# GS_01_Pow.net
KiCad netlist of a schematic drawn in Altium Designer
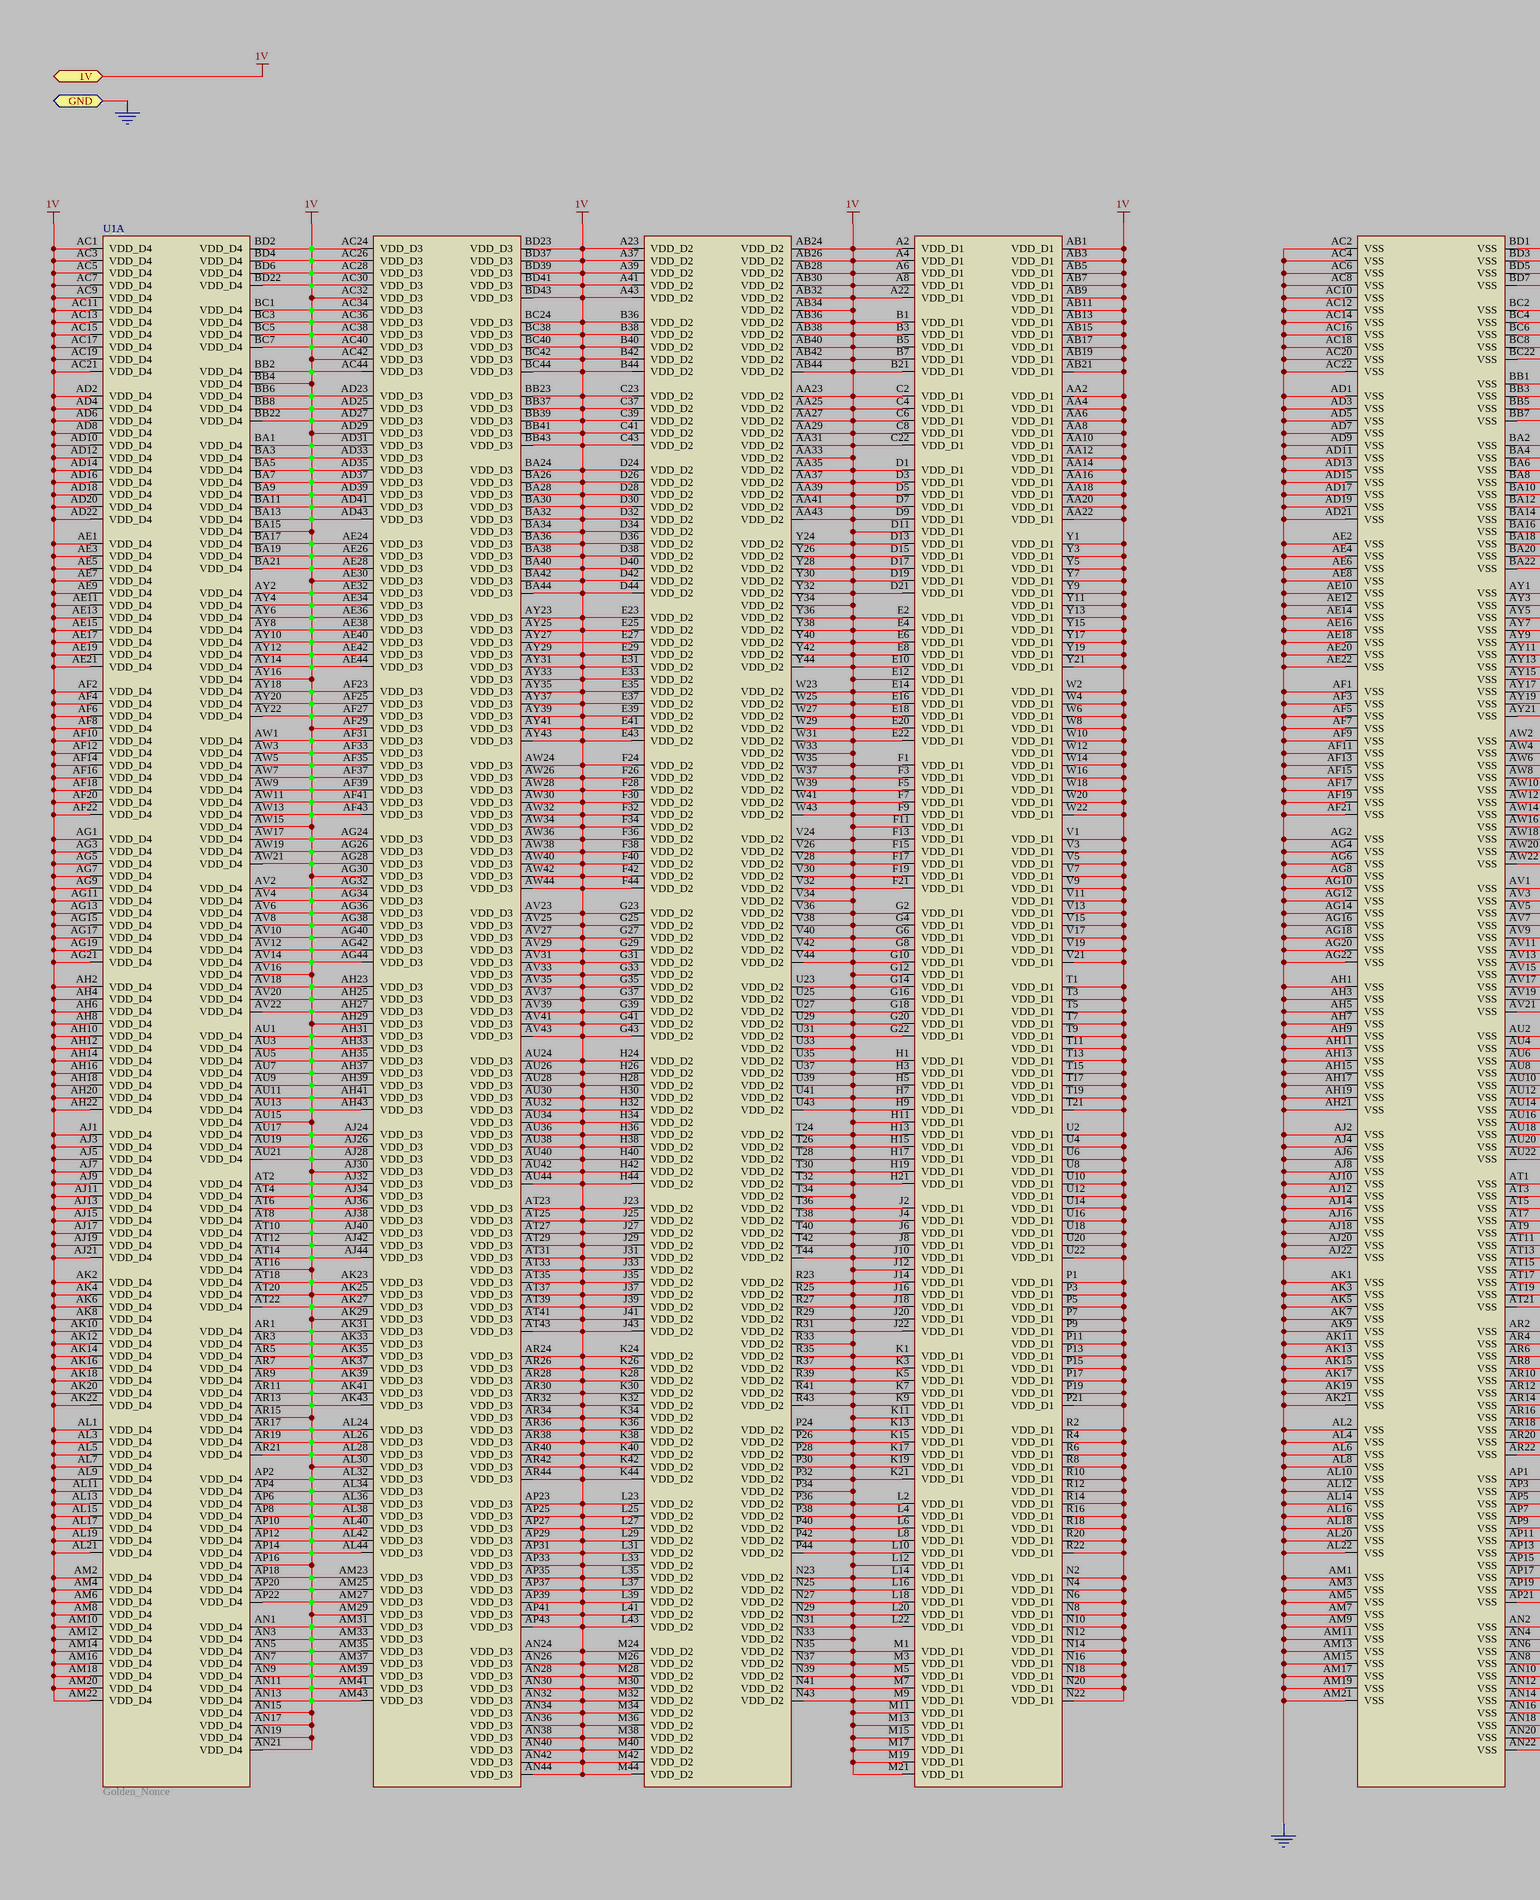
[diagram p0: GS_01_Pow.SchDoc, left]
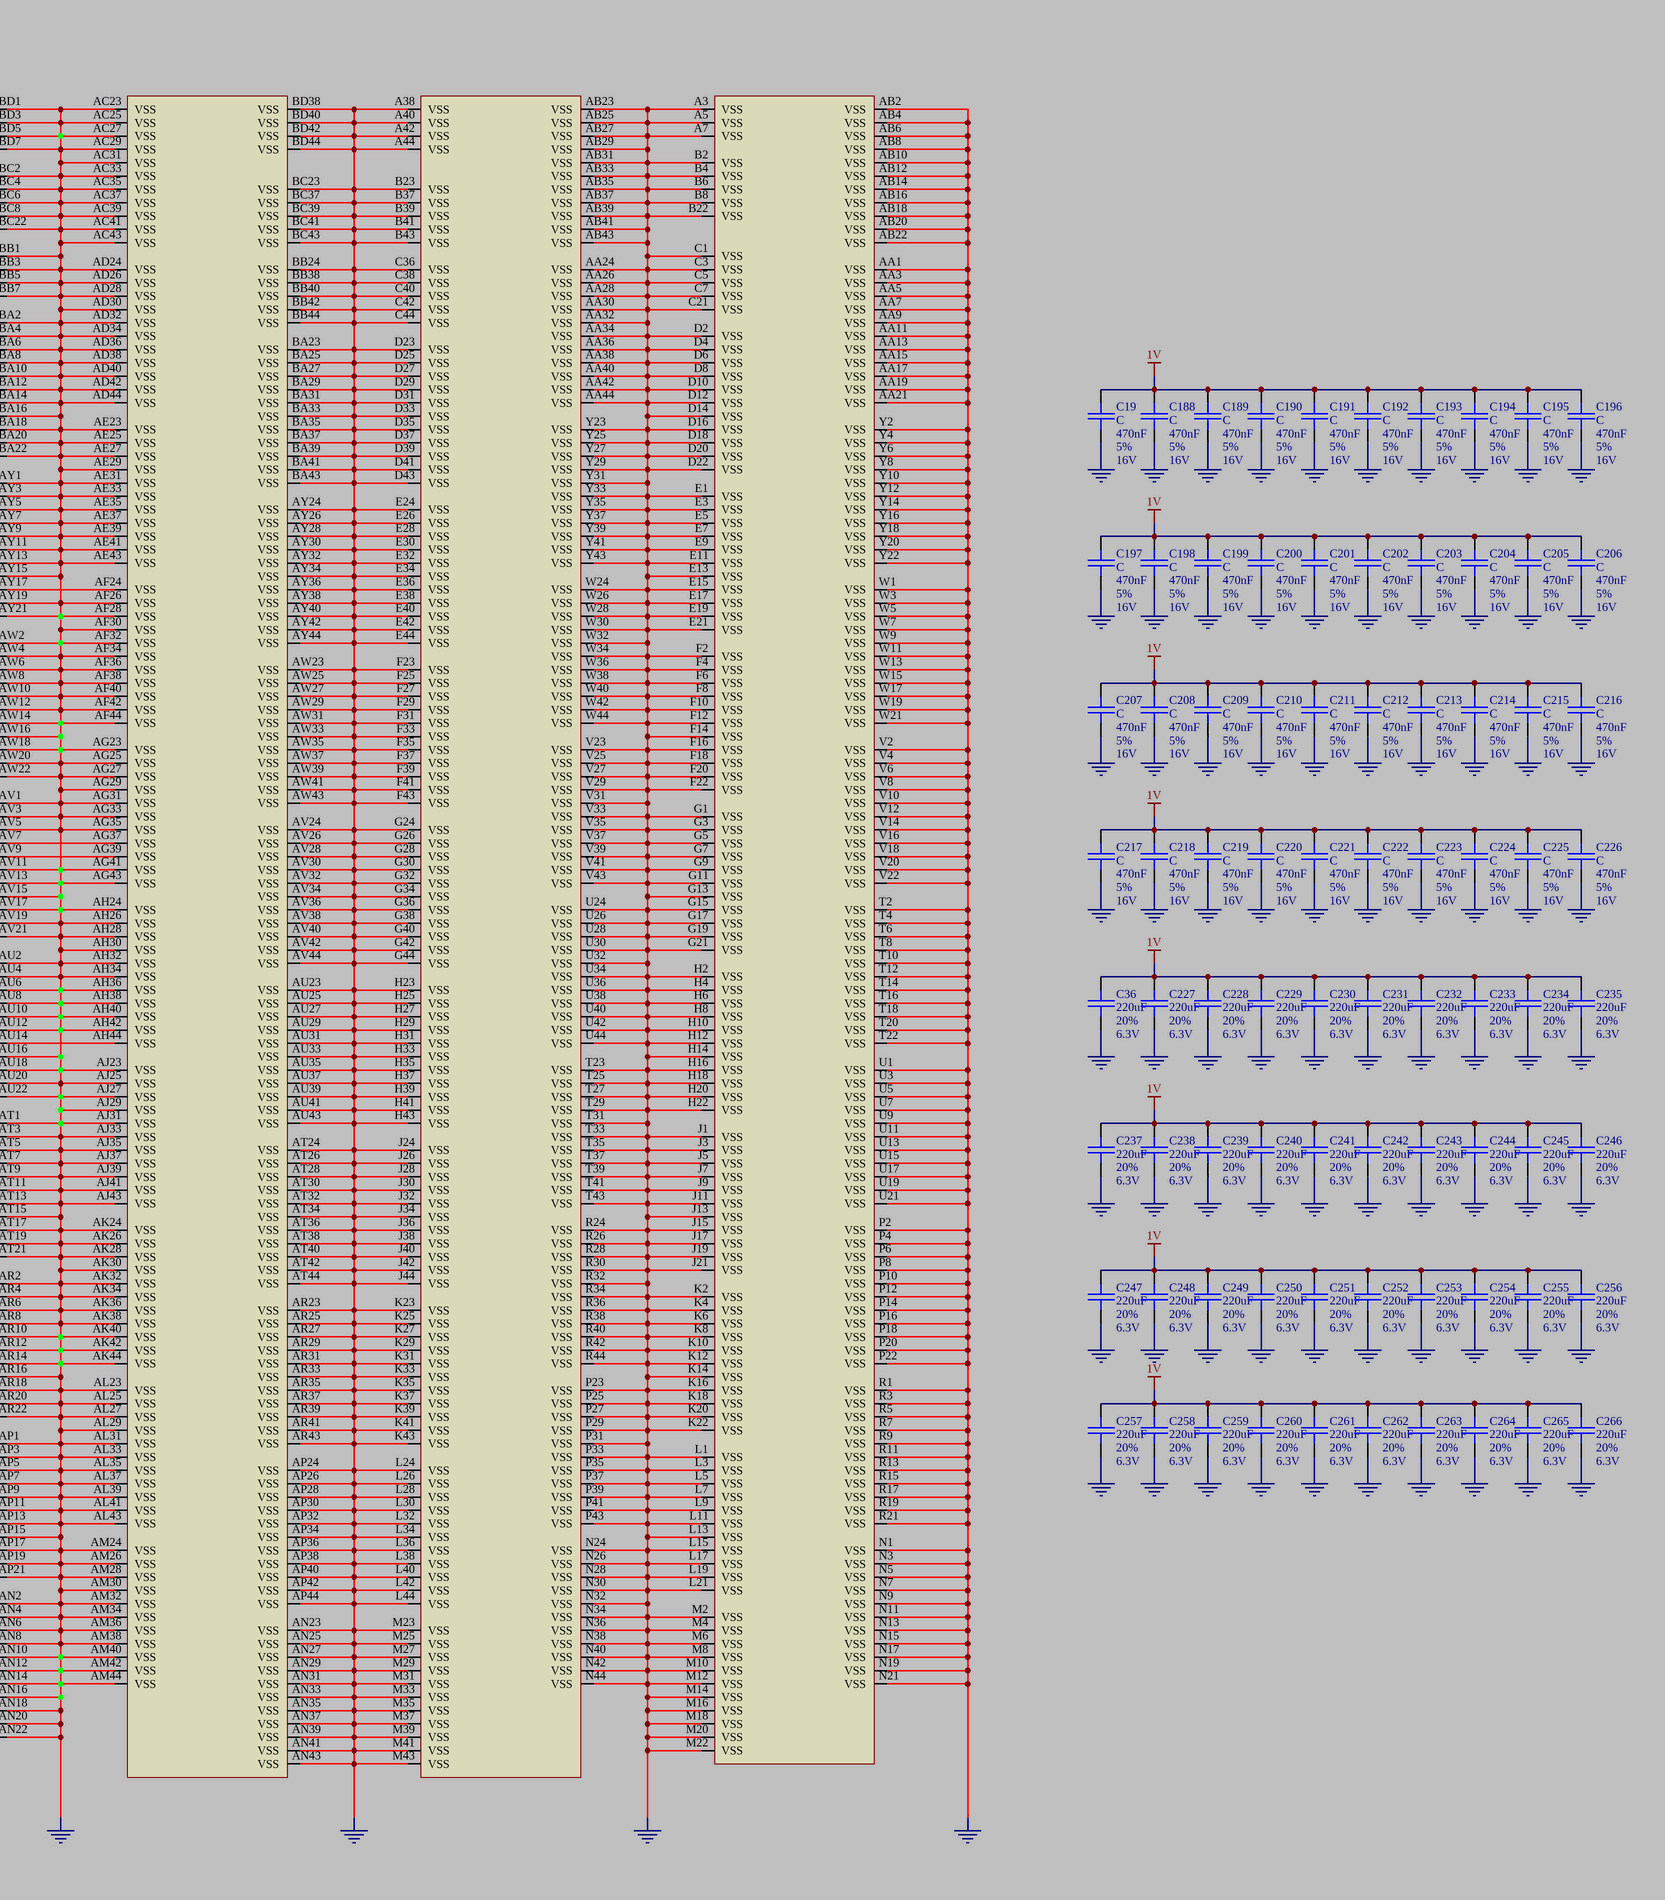
[diagram p1: GS_01_Pow.SchDoc, right]

(export (version "E")
  (design (tool "Eeschema 10.0.6"))
  (components
    (comp (ref "C19")
      (value "C")
      (footprint "SMD_0603_CAPC1608X95N")
      (fields
        (field (name "DB_PART_NUMBER") "CAP000028169")
        (field (name "DB_VALUE") "470nF")
        (field (name "DB_TOLERANCE") "5%")
        (field (name "DB_VOLTAGE") "16V")
        (field (name "DB_MANUFACTURER_PART") "KEMET    C0603C474J4RAC")
      )
      (libsource (lib "Database_Libs1") (part "C"))
    )
    (comp (ref "C36")
      (value "C")
      (footprint "SMD_1210_CAPC3225X279N")
      (fields
        (field (name "DB_PART_NUMBER") "CAP000047355")
        (field (name "DB_VALUE") "220uF")
        (field (name "DB_TOLERANCE") "20%")
        (field (name "DB_VOLTAGE") "6.3V")
        (field (name "DB_MANUFACTURER_PART") "SAMSUNG    CL32A227MQVNNNE")
        (field (name "DB_APPROVED_BY") "VSN")
      )
      (libsource (lib "Database_Libs1") (part "C"))
    )
    (comp (ref "C188")
      (value "C")
      (footprint "SMD_0603_CAPC1608X95N")
      (fields
        (field (name "DB_PART_NUMBER") "CAP000028169")
        (field (name "DB_VALUE") "470nF")
        (field (name "DB_TOLERANCE") "5%")
        (field (name "DB_VOLTAGE") "16V")
        (field (name "DB_MANUFACTURER_PART") "KEMET    C0603C474J4RAC")
      )
      (libsource (lib "Database_Libs1") (part "C"))
    )
    (comp (ref "C189")
      (value "C")
      (footprint "SMD_0603_CAPC1608X95N")
      (fields
        (field (name "DB_PART_NUMBER") "CAP000028169")
        (field (name "DB_VALUE") "470nF")
        (field (name "DB_TOLERANCE") "5%")
        (field (name "DB_VOLTAGE") "16V")
        (field (name "DB_MANUFACTURER_PART") "KEMET    C0603C474J4RAC")
      )
      (libsource (lib "Database_Libs1") (part "C"))
    )
    (comp (ref "C190")
      (value "C")
      (footprint "SMD_0603_CAPC1608X95N")
      (fields
        (field (name "DB_PART_NUMBER") "CAP000028169")
        (field (name "DB_VALUE") "470nF")
        (field (name "DB_TOLERANCE") "5%")
        (field (name "DB_VOLTAGE") "16V")
        (field (name "DB_MANUFACTURER_PART") "KEMET    C0603C474J4RAC")
      )
      (libsource (lib "Database_Libs1") (part "C"))
    )
    (comp (ref "C191")
      (value "C")
      (footprint "SMD_0603_CAPC1608X95N")
      (fields
        (field (name "DB_PART_NUMBER") "CAP000028169")
        (field (name "DB_VALUE") "470nF")
        (field (name "DB_TOLERANCE") "5%")
        (field (name "DB_VOLTAGE") "16V")
        (field (name "DB_MANUFACTURER_PART") "KEMET    C0603C474J4RAC")
      )
      (libsource (lib "Database_Libs1") (part "C"))
    )
    (comp (ref "C192")
      (value "C")
      (footprint "SMD_0603_CAPC1608X95N")
      (fields
        (field (name "DB_PART_NUMBER") "CAP000028169")
        (field (name "DB_VALUE") "470nF")
        (field (name "DB_TOLERANCE") "5%")
        (field (name "DB_VOLTAGE") "16V")
        (field (name "DB_MANUFACTURER_PART") "KEMET    C0603C474J4RAC")
      )
      (libsource (lib "Database_Libs1") (part "C"))
    )
    (comp (ref "C193")
      (value "C")
      (footprint "SMD_0603_CAPC1608X95N")
      (fields
        (field (name "DB_PART_NUMBER") "CAP000028169")
        (field (name "DB_VALUE") "470nF")
        (field (name "DB_TOLERANCE") "5%")
        (field (name "DB_VOLTAGE") "16V")
        (field (name "DB_MANUFACTURER_PART") "KEMET    C0603C474J4RAC")
      )
      (libsource (lib "Database_Libs1") (part "C"))
    )
    (comp (ref "C194")
      (value "C")
      (footprint "SMD_0603_CAPC1608X95N")
      (fields
        (field (name "DB_PART_NUMBER") "CAP000028169")
        (field (name "DB_VALUE") "470nF")
        (field (name "DB_TOLERANCE") "5%")
        (field (name "DB_VOLTAGE") "16V")
        (field (name "DB_MANUFACTURER_PART") "KEMET    C0603C474J4RAC")
      )
      (libsource (lib "Database_Libs1") (part "C"))
    )
    (comp (ref "C195")
      (value "C")
      (footprint "SMD_0603_CAPC1608X95N")
      (fields
        (field (name "DB_PART_NUMBER") "CAP000028169")
        (field (name "DB_VALUE") "470nF")
        (field (name "DB_TOLERANCE") "5%")
        (field (name "DB_VOLTAGE") "16V")
        (field (name "DB_MANUFACTURER_PART") "KEMET    C0603C474J4RAC")
      )
      (libsource (lib "Database_Libs1") (part "C"))
    )
    (comp (ref "C196")
      (value "C")
      (footprint "SMD_0603_CAPC1608X95N")
      (fields
        (field (name "DB_PART_NUMBER") "CAP000028169")
        (field (name "DB_VALUE") "470nF")
        (field (name "DB_TOLERANCE") "5%")
        (field (name "DB_VOLTAGE") "16V")
        (field (name "DB_MANUFACTURER_PART") "KEMET    C0603C474J4RAC")
      )
      (libsource (lib "Database_Libs1") (part "C"))
    )
    (comp (ref "C197")
      (value "C")
      (footprint "SMD_0603_CAPC1608X95N")
      (fields
        (field (name "DB_PART_NUMBER") "CAP000028169")
        (field (name "DB_VALUE") "470nF")
        (field (name "DB_TOLERANCE") "5%")
        (field (name "DB_VOLTAGE") "16V")
        (field (name "DB_MANUFACTURER_PART") "KEMET    C0603C474J4RAC")
      )
      (libsource (lib "Database_Libs1") (part "C"))
    )
    (comp (ref "C198")
      (value "C")
      (footprint "SMD_0603_CAPC1608X95N")
      (fields
        (field (name "DB_PART_NUMBER") "CAP000028169")
        (field (name "DB_VALUE") "470nF")
        (field (name "DB_TOLERANCE") "5%")
        (field (name "DB_VOLTAGE") "16V")
        (field (name "DB_MANUFACTURER_PART") "KEMET    C0603C474J4RAC")
      )
      (libsource (lib "Database_Libs1") (part "C"))
    )
    (comp (ref "C199")
      (value "C")
      (footprint "SMD_0603_CAPC1608X95N")
      (fields
        (field (name "DB_PART_NUMBER") "CAP000028169")
        (field (name "DB_VALUE") "470nF")
        (field (name "DB_TOLERANCE") "5%")
        (field (name "DB_VOLTAGE") "16V")
        (field (name "DB_MANUFACTURER_PART") "KEMET    C0603C474J4RAC")
      )
      (libsource (lib "Database_Libs1") (part "C"))
    )
    (comp (ref "C200")
      (value "C")
      (footprint "SMD_0603_CAPC1608X95N")
      (fields
        (field (name "DB_PART_NUMBER") "CAP000028169")
        (field (name "DB_VALUE") "470nF")
        (field (name "DB_TOLERANCE") "5%")
        (field (name "DB_VOLTAGE") "16V")
        (field (name "DB_MANUFACTURER_PART") "KEMET    C0603C474J4RAC")
      )
      (libsource (lib "Database_Libs1") (part "C"))
    )
    (comp (ref "C201")
      (value "C")
      (footprint "SMD_0603_CAPC1608X95N")
      (fields
        (field (name "DB_PART_NUMBER") "CAP000028169")
        (field (name "DB_VALUE") "470nF")
        (field (name "DB_TOLERANCE") "5%")
        (field (name "DB_VOLTAGE") "16V")
        (field (name "DB_MANUFACTURER_PART") "KEMET    C0603C474J4RAC")
      )
      (libsource (lib "Database_Libs1") (part "C"))
    )
    (comp (ref "C202")
      (value "C")
      (footprint "SMD_0603_CAPC1608X95N")
      (fields
        (field (name "DB_PART_NUMBER") "CAP000028169")
        (field (name "DB_VALUE") "470nF")
        (field (name "DB_TOLERANCE") "5%")
        (field (name "DB_VOLTAGE") "16V")
        (field (name "DB_MANUFACTURER_PART") "KEMET    C0603C474J4RAC")
      )
      (libsource (lib "Database_Libs1") (part "C"))
    )
    (comp (ref "C203")
      (value "C")
      (footprint "SMD_0603_CAPC1608X95N")
      (fields
        (field (name "DB_PART_NUMBER") "CAP000028169")
        (field (name "DB_VALUE") "470nF")
        (field (name "DB_TOLERANCE") "5%")
        (field (name "DB_VOLTAGE") "16V")
        (field (name "DB_MANUFACTURER_PART") "KEMET    C0603C474J4RAC")
      )
      (libsource (lib "Database_Libs1") (part "C"))
    )
    (comp (ref "C204")
      (value "C")
      (footprint "SMD_0603_CAPC1608X95N")
      (fields
        (field (name "DB_PART_NUMBER") "CAP000028169")
        (field (name "DB_VALUE") "470nF")
        (field (name "DB_TOLERANCE") "5%")
        (field (name "DB_VOLTAGE") "16V")
        (field (name "DB_MANUFACTURER_PART") "KEMET    C0603C474J4RAC")
      )
      (libsource (lib "Database_Libs1") (part "C"))
    )
    (comp (ref "C205")
      (value "C")
      (footprint "SMD_0603_CAPC1608X95N")
      (fields
        (field (name "DB_PART_NUMBER") "CAP000028169")
        (field (name "DB_VALUE") "470nF")
        (field (name "DB_TOLERANCE") "5%")
        (field (name "DB_VOLTAGE") "16V")
        (field (name "DB_MANUFACTURER_PART") "KEMET    C0603C474J4RAC")
      )
      (libsource (lib "Database_Libs1") (part "C"))
    )
    (comp (ref "C206")
      (value "C")
      (footprint "SMD_0603_CAPC1608X95N")
      (fields
        (field (name "DB_PART_NUMBER") "CAP000028169")
        (field (name "DB_VALUE") "470nF")
        (field (name "DB_TOLERANCE") "5%")
        (field (name "DB_VOLTAGE") "16V")
        (field (name "DB_MANUFACTURER_PART") "KEMET    C0603C474J4RAC")
      )
      (libsource (lib "Database_Libs1") (part "C"))
    )
    (comp (ref "C207")
      (value "C")
      (footprint "SMD_0603_CAPC1608X95N")
      (fields
        (field (name "DB_PART_NUMBER") "CAP000028169")
        (field (name "DB_VALUE") "470nF")
        (field (name "DB_TOLERANCE") "5%")
        (field (name "DB_VOLTAGE") "16V")
        (field (name "DB_MANUFACTURER_PART") "KEMET    C0603C474J4RAC")
      )
      (libsource (lib "Database_Libs1") (part "C"))
    )
    (comp (ref "C208")
      (value "C")
      (footprint "SMD_0603_CAPC1608X95N")
      (fields
        (field (name "DB_PART_NUMBER") "CAP000028169")
        (field (name "DB_VALUE") "470nF")
        (field (name "DB_TOLERANCE") "5%")
        (field (name "DB_VOLTAGE") "16V")
        (field (name "DB_MANUFACTURER_PART") "KEMET    C0603C474J4RAC")
      )
      (libsource (lib "Database_Libs1") (part "C"))
    )
    (comp (ref "C209")
      (value "C")
      (footprint "SMD_0603_CAPC1608X95N")
      (fields
        (field (name "DB_PART_NUMBER") "CAP000028169")
        (field (name "DB_VALUE") "470nF")
        (field (name "DB_TOLERANCE") "5%")
        (field (name "DB_VOLTAGE") "16V")
        (field (name "DB_MANUFACTURER_PART") "KEMET    C0603C474J4RAC")
      )
      (libsource (lib "Database_Libs1") (part "C"))
    )
    (comp (ref "C210")
      (value "C")
      (footprint "SMD_0603_CAPC1608X95N")
      (fields
        (field (name "DB_PART_NUMBER") "CAP000028169")
        (field (name "DB_VALUE") "470nF")
        (field (name "DB_TOLERANCE") "5%")
        (field (name "DB_VOLTAGE") "16V")
        (field (name "DB_MANUFACTURER_PART") "KEMET    C0603C474J4RAC")
      )
      (libsource (lib "Database_Libs1") (part "C"))
    )
    (comp (ref "C211")
      (value "C")
      (footprint "SMD_0603_CAPC1608X95N")
      (fields
        (field (name "DB_PART_NUMBER") "CAP000028169")
        (field (name "DB_VALUE") "470nF")
        (field (name "DB_TOLERANCE") "5%")
        (field (name "DB_VOLTAGE") "16V")
        (field (name "DB_MANUFACTURER_PART") "KEMET    C0603C474J4RAC")
      )
      (libsource (lib "Database_Libs1") (part "C"))
    )
    (comp (ref "C212")
      (value "C")
      (footprint "SMD_0603_CAPC1608X95N")
      (fields
        (field (name "DB_PART_NUMBER") "CAP000028169")
        (field (name "DB_VALUE") "470nF")
        (field (name "DB_TOLERANCE") "5%")
        (field (name "DB_VOLTAGE") "16V")
        (field (name "DB_MANUFACTURER_PART") "KEMET    C0603C474J4RAC")
      )
      (libsource (lib "Database_Libs1") (part "C"))
    )
    (comp (ref "C213")
      (value "C")
      (footprint "SMD_0603_CAPC1608X95N")
      (fields
        (field (name "DB_PART_NUMBER") "CAP000028169")
        (field (name "DB_VALUE") "470nF")
        (field (name "DB_TOLERANCE") "5%")
        (field (name "DB_VOLTAGE") "16V")
        (field (name "DB_MANUFACTURER_PART") "KEMET    C0603C474J4RAC")
      )
      (libsource (lib "Database_Libs1") (part "C"))
    )
    (comp (ref "C214")
      (value "C")
      (footprint "SMD_0603_CAPC1608X95N")
      (fields
        (field (name "DB_PART_NUMBER") "CAP000028169")
        (field (name "DB_VALUE") "470nF")
        (field (name "DB_TOLERANCE") "5%")
        (field (name "DB_VOLTAGE") "16V")
        (field (name "DB_MANUFACTURER_PART") "KEMET    C0603C474J4RAC")
      )
      (libsource (lib "Database_Libs1") (part "C"))
    )
    (comp (ref "C215")
      (value "C")
      (footprint "SMD_0603_CAPC1608X95N")
      (fields
        (field (name "DB_PART_NUMBER") "CAP000028169")
        (field (name "DB_VALUE") "470nF")
        (field (name "DB_TOLERANCE") "5%")
        (field (name "DB_VOLTAGE") "16V")
        (field (name "DB_MANUFACTURER_PART") "KEMET    C0603C474J4RAC")
      )
      (libsource (lib "Database_Libs1") (part "C"))
    )
    (comp (ref "C216")
      (value "C")
      (footprint "SMD_0603_CAPC1608X95N")
      (fields
        (field (name "DB_PART_NUMBER") "CAP000028169")
        (field (name "DB_VALUE") "470nF")
        (field (name "DB_TOLERANCE") "5%")
        (field (name "DB_VOLTAGE") "16V")
        (field (name "DB_MANUFACTURER_PART") "KEMET    C0603C474J4RAC")
      )
      (libsource (lib "Database_Libs1") (part "C"))
    )
    (comp (ref "C217")
      (value "C")
      (footprint "SMD_0603_CAPC1608X95N")
      (fields
        (field (name "DB_PART_NUMBER") "CAP000028169")
        (field (name "DB_VALUE") "470nF")
        (field (name "DB_TOLERANCE") "5%")
        (field (name "DB_VOLTAGE") "16V")
        (field (name "DB_MANUFACTURER_PART") "KEMET    C0603C474J4RAC")
      )
      (libsource (lib "Database_Libs1") (part "C"))
    )
    (comp (ref "C218")
      (value "C")
      (footprint "SMD_0603_CAPC1608X95N")
      (fields
        (field (name "DB_PART_NUMBER") "CAP000028169")
        (field (name "DB_VALUE") "470nF")
        (field (name "DB_TOLERANCE") "5%")
        (field (name "DB_VOLTAGE") "16V")
        (field (name "DB_MANUFACTURER_PART") "KEMET    C0603C474J4RAC")
      )
      (libsource (lib "Database_Libs1") (part "C"))
    )
    (comp (ref "C219")
      (value "C")
      (footprint "SMD_0603_CAPC1608X95N")
      (fields
        (field (name "DB_PART_NUMBER") "CAP000028169")
        (field (name "DB_VALUE") "470nF")
        (field (name "DB_TOLERANCE") "5%")
        (field (name "DB_VOLTAGE") "16V")
        (field (name "DB_MANUFACTURER_PART") "KEMET    C0603C474J4RAC")
      )
      (libsource (lib "Database_Libs1") (part "C"))
    )
    (comp (ref "C220")
      (value "C")
      (footprint "SMD_0603_CAPC1608X95N")
      (fields
        (field (name "DB_PART_NUMBER") "CAP000028169")
        (field (name "DB_VALUE") "470nF")
        (field (name "DB_TOLERANCE") "5%")
        (field (name "DB_VOLTAGE") "16V")
        (field (name "DB_MANUFACTURER_PART") "KEMET    C0603C474J4RAC")
      )
      (libsource (lib "Database_Libs1") (part "C"))
    )
    (comp (ref "C221")
      (value "C")
      (footprint "SMD_0603_CAPC1608X95N")
      (fields
        (field (name "DB_PART_NUMBER") "CAP000028169")
        (field (name "DB_VALUE") "470nF")
        (field (name "DB_TOLERANCE") "5%")
        (field (name "DB_VOLTAGE") "16V")
        (field (name "DB_MANUFACTURER_PART") "KEMET    C0603C474J4RAC")
      )
      (libsource (lib "Database_Libs1") (part "C"))
    )
    (comp (ref "C222")
      (value "C")
      (footprint "SMD_0603_CAPC1608X95N")
      (fields
        (field (name "DB_PART_NUMBER") "CAP000028169")
        (field (name "DB_VALUE") "470nF")
        (field (name "DB_TOLERANCE") "5%")
        (field (name "DB_VOLTAGE") "16V")
        (field (name "DB_MANUFACTURER_PART") "KEMET    C0603C474J4RAC")
      )
      (libsource (lib "Database_Libs1") (part "C"))
    )
    (comp (ref "C223")
      (value "C")
      (footprint "SMD_0603_CAPC1608X95N")
      (fields
        (field (name "DB_PART_NUMBER") "CAP000028169")
        (field (name "DB_VALUE") "470nF")
        (field (name "DB_TOLERANCE") "5%")
        (field (name "DB_VOLTAGE") "16V")
        (field (name "DB_MANUFACTURER_PART") "KEMET    C0603C474J4RAC")
      )
      (libsource (lib "Database_Libs1") (part "C"))
    )
    (comp (ref "C224")
      (value "C")
      (footprint "SMD_0603_CAPC1608X95N")
      (fields
        (field (name "DB_PART_NUMBER") "CAP000028169")
        (field (name "DB_VALUE") "470nF")
        (field (name "DB_TOLERANCE") "5%")
        (field (name "DB_VOLTAGE") "16V")
        (field (name "DB_MANUFACTURER_PART") "KEMET    C0603C474J4RAC")
      )
      (libsource (lib "Database_Libs1") (part "C"))
    )
    (comp (ref "C225")
      (value "C")
      (footprint "SMD_0603_CAPC1608X95N")
      (fields
        (field (name "DB_PART_NUMBER") "CAP000028169")
        (field (name "DB_VALUE") "470nF")
        (field (name "DB_TOLERANCE") "5%")
        (field (name "DB_VOLTAGE") "16V")
        (field (name "DB_MANUFACTURER_PART") "KEMET    C0603C474J4RAC")
      )
      (libsource (lib "Database_Libs1") (part "C"))
    )
    (comp (ref "C226")
      (value "C")
      (footprint "SMD_0603_CAPC1608X95N")
      (fields
        (field (name "DB_PART_NUMBER") "CAP000028169")
        (field (name "DB_VALUE") "470nF")
        (field (name "DB_TOLERANCE") "5%")
        (field (name "DB_VOLTAGE") "16V")
        (field (name "DB_MANUFACTURER_PART") "KEMET    C0603C474J4RAC")
      )
      (libsource (lib "Database_Libs1") (part "C"))
    )
    (comp (ref "C227")
      (value "C")
      (footprint "SMD_1210_CAPC3225X279N")
      (fields
        (field (name "DB_PART_NUMBER") "CAP000047355")
        (field (name "DB_VALUE") "220uF")
        (field (name "DB_TOLERANCE") "20%")
        (field (name "DB_VOLTAGE") "6.3V")
        (field (name "DB_MANUFACTURER_PART") "SAMSUNG    CL32A227MQVNNNE")
        (field (name "DB_APPROVED_BY") "VSN")
      )
      (libsource (lib "Database_Libs1") (part "C"))
    )
    (comp (ref "C228")
      (value "C")
      (footprint "SMD_1210_CAPC3225X279N")
      (fields
        (field (name "DB_PART_NUMBER") "CAP000047355")
        (field (name "DB_VALUE") "220uF")
        (field (name "DB_TOLERANCE") "20%")
        (field (name "DB_VOLTAGE") "6.3V")
        (field (name "DB_MANUFACTURER_PART") "SAMSUNG    CL32A227MQVNNNE")
        (field (name "DB_APPROVED_BY") "VSN")
      )
      (libsource (lib "Database_Libs1") (part "C"))
    )
    (comp (ref "C229")
      (value "C")
      (footprint "SMD_1210_CAPC3225X279N")
      (fields
        (field (name "DB_PART_NUMBER") "CAP000047355")
        (field (name "DB_VALUE") "220uF")
        (field (name "DB_TOLERANCE") "20%")
        (field (name "DB_VOLTAGE") "6.3V")
        (field (name "DB_MANUFACTURER_PART") "SAMSUNG    CL32A227MQVNNNE")
        (field (name "DB_APPROVED_BY") "VSN")
      )
      (libsource (lib "Database_Libs1") (part "C"))
    )
    (comp (ref "C230")
      (value "C")
      (footprint "SMD_1210_CAPC3225X279N")
      (fields
        (field (name "DB_PART_NUMBER") "CAP000047355")
        (field (name "DB_VALUE") "220uF")
        (field (name "DB_TOLERANCE") "20%")
        (field (name "DB_VOLTAGE") "6.3V")
        (field (name "DB_MANUFACTURER_PART") "SAMSUNG    CL32A227MQVNNNE")
        (field (name "DB_APPROVED_BY") "VSN")
      )
      (libsource (lib "Database_Libs1") (part "C"))
    )
    (comp (ref "C231")
      (value "C")
      (footprint "SMD_1210_CAPC3225X279N")
      (fields
        (field (name "DB_PART_NUMBER") "CAP000047355")
        (field (name "DB_VALUE") "220uF")
        (field (name "DB_TOLERANCE") "20%")
        (field (name "DB_VOLTAGE") "6.3V")
        (field (name "DB_MANUFACTURER_PART") "SAMSUNG    CL32A227MQVNNNE")
        (field (name "DB_APPROVED_BY") "VSN")
      )
      (libsource (lib "Database_Libs1") (part "C"))
    )
    (comp (ref "C232")
      (value "C")
      (footprint "SMD_1210_CAPC3225X279N")
      (fields
        (field (name "DB_PART_NUMBER") "CAP000047355")
        (field (name "DB_VALUE") "220uF")
        (field (name "DB_TOLERANCE") "20%")
        (field (name "DB_VOLTAGE") "6.3V")
        (field (name "DB_MANUFACTURER_PART") "SAMSUNG    CL32A227MQVNNNE")
        (field (name "DB_APPROVED_BY") "VSN")
      )
      (libsource (lib "Database_Libs1") (part "C"))
    )
    (comp (ref "C233")
      (value "C")
      (footprint "SMD_1210_CAPC3225X279N")
      (fields
        (field (name "DB_PART_NUMBER") "CAP000047355")
        (field (name "DB_VALUE") "220uF")
        (field (name "DB_TOLERANCE") "20%")
        (field (name "DB_VOLTAGE") "6.3V")
        (field (name "DB_MANUFACTURER_PART") "SAMSUNG    CL32A227MQVNNNE")
        (field (name "DB_APPROVED_BY") "VSN")
      )
      (libsource (lib "Database_Libs1") (part "C"))
    )
    (comp (ref "C234")
      (value "C")
      (footprint "SMD_1210_CAPC3225X279N")
      (fields
        (field (name "DB_PART_NUMBER") "CAP000047355")
        (field (name "DB_VALUE") "220uF")
        (field (name "DB_TOLERANCE") "20%")
        (field (name "DB_VOLTAGE") "6.3V")
        (field (name "DB_MANUFACTURER_PART") "SAMSUNG    CL32A227MQVNNNE")
        (field (name "DB_APPROVED_BY") "VSN")
      )
      (libsource (lib "Database_Libs1") (part "C"))
    )
    (comp (ref "C235")
      (value "C")
      (footprint "SMD_1210_CAPC3225X279N")
      (fields
        (field (name "DB_PART_NUMBER") "CAP000047355")
        (field (name "DB_VALUE") "220uF")
        (field (name "DB_TOLERANCE") "20%")
        (field (name "DB_VOLTAGE") "6.3V")
        (field (name "DB_MANUFACTURER_PART") "SAMSUNG    CL32A227MQVNNNE")
        (field (name "DB_APPROVED_BY") "VSN")
      )
      (libsource (lib "Database_Libs1") (part "C"))
    )
    (comp (ref "C237")
      (value "C")
      (footprint "SMD_1210_CAPC3225X279N")
      (fields
        (field (name "DB_PART_NUMBER") "CAP000047355")
        (field (name "DB_VALUE") "220uF")
        (field (name "DB_TOLERANCE") "20%")
        (field (name "DB_VOLTAGE") "6.3V")
        (field (name "DB_MANUFACTURER_PART") "SAMSUNG    CL32A227MQVNNNE")
        (field (name "DB_APPROVED_BY") "VSN")
      )
      (libsource (lib "Database_Libs1") (part "C"))
    )
    (comp (ref "C238")
      (value "C")
      (footprint "SMD_1210_CAPC3225X279N")
      (fields
        (field (name "DB_PART_NUMBER") "CAP000047355")
        (field (name "DB_VALUE") "220uF")
        (field (name "DB_TOLERANCE") "20%")
        (field (name "DB_VOLTAGE") "6.3V")
        (field (name "DB_MANUFACTURER_PART") "SAMSUNG    CL32A227MQVNNNE")
        (field (name "DB_APPROVED_BY") "VSN")
      )
      (libsource (lib "Database_Libs1") (part "C"))
    )
    (comp (ref "C239")
      (value "C")
      (footprint "SMD_1210_CAPC3225X279N")
      (fields
        (field (name "DB_PART_NUMBER") "CAP000047355")
        (field (name "DB_VALUE") "220uF")
        (field (name "DB_TOLERANCE") "20%")
        (field (name "DB_VOLTAGE") "6.3V")
        (field (name "DB_MANUFACTURER_PART") "SAMSUNG    CL32A227MQVNNNE")
        (field (name "DB_APPROVED_BY") "VSN")
      )
      (libsource (lib "Database_Libs1") (part "C"))
    )
    (comp (ref "C240")
      (value "C")
      (footprint "SMD_1210_CAPC3225X279N")
      (fields
        (field (name "DB_PART_NUMBER") "CAP000047355")
        (field (name "DB_VALUE") "220uF")
        (field (name "DB_TOLERANCE") "20%")
        (field (name "DB_VOLTAGE") "6.3V")
        (field (name "DB_MANUFACTURER_PART") "SAMSUNG    CL32A227MQVNNNE")
        (field (name "DB_APPROVED_BY") "VSN")
      )
      (libsource (lib "Database_Libs1") (part "C"))
    )
    (comp (ref "C241")
      (value "C")
      (footprint "SMD_1210_CAPC3225X279N")
      (fields
        (field (name "DB_PART_NUMBER") "CAP000047355")
        (field (name "DB_VALUE") "220uF")
        (field (name "DB_TOLERANCE") "20%")
        (field (name "DB_VOLTAGE") "6.3V")
        (field (name "DB_MANUFACTURER_PART") "SAMSUNG    CL32A227MQVNNNE")
        (field (name "DB_APPROVED_BY") "VSN")
      )
      (libsource (lib "Database_Libs1") (part "C"))
    )
    (comp (ref "C242")
      (value "C")
      (footprint "SMD_1210_CAPC3225X279N")
      (fields
        (field (name "DB_PART_NUMBER") "CAP000047355")
        (field (name "DB_VALUE") "220uF")
        (field (name "DB_TOLERANCE") "20%")
        (field (name "DB_VOLTAGE") "6.3V")
        (field (name "DB_MANUFACTURER_PART") "SAMSUNG    CL32A227MQVNNNE")
        (field (name "DB_APPROVED_BY") "VSN")
      )
      (libsource (lib "Database_Libs1") (part "C"))
    )
    (comp (ref "C243")
      (value "C")
      (footprint "SMD_1210_CAPC3225X279N")
      (fields
        (field (name "DB_PART_NUMBER") "CAP000047355")
        (field (name "DB_VALUE") "220uF")
        (field (name "DB_TOLERANCE") "20%")
        (field (name "DB_VOLTAGE") "6.3V")
        (field (name "DB_MANUFACTURER_PART") "SAMSUNG    CL32A227MQVNNNE")
        (field (name "DB_APPROVED_BY") "VSN")
      )
      (libsource (lib "Database_Libs1") (part "C"))
    )
    (comp (ref "C244")
      (value "C")
      (footprint "SMD_1210_CAPC3225X279N")
      (fields
        (field (name "DB_PART_NUMBER") "CAP000047355")
        (field (name "DB_VALUE") "220uF")
        (field (name "DB_TOLERANCE") "20%")
        (field (name "DB_VOLTAGE") "6.3V")
        (field (name "DB_MANUFACTURER_PART") "SAMSUNG    CL32A227MQVNNNE")
        (field (name "DB_APPROVED_BY") "VSN")
      )
      (libsource (lib "Database_Libs1") (part "C"))
    )
    (comp (ref "C245")
      (value "C")
      (footprint "SMD_1210_CAPC3225X279N")
      (fields
        (field (name "DB_PART_NUMBER") "CAP000047355")
        (field (name "DB_VALUE") "220uF")
        (field (name "DB_TOLERANCE") "20%")
        (field (name "DB_VOLTAGE") "6.3V")
        (field (name "DB_MANUFACTURER_PART") "SAMSUNG    CL32A227MQVNNNE")
        (field (name "DB_APPROVED_BY") "VSN")
      )
      (libsource (lib "Database_Libs1") (part "C"))
    )
    (comp (ref "C246")
      (value "C")
      (footprint "SMD_1210_CAPC3225X279N")
      (fields
        (field (name "DB_PART_NUMBER") "CAP000047355")
        (field (name "DB_VALUE") "220uF")
        (field (name "DB_TOLERANCE") "20%")
        (field (name "DB_VOLTAGE") "6.3V")
        (field (name "DB_MANUFACTURER_PART") "SAMSUNG    CL32A227MQVNNNE")
        (field (name "DB_APPROVED_BY") "VSN")
      )
      (libsource (lib "Database_Libs1") (part "C"))
    )
    (comp (ref "C247")
      (value "C")
      (footprint "SMD_1210_CAPC3225X279N")
      (fields
        (field (name "DB_PART_NUMBER") "CAP000047355")
        (field (name "DB_VALUE") "220uF")
        (field (name "DB_TOLERANCE") "20%")
        (field (name "DB_VOLTAGE") "6.3V")
        (field (name "DB_MANUFACTURER_PART") "SAMSUNG    CL32A227MQVNNNE")
        (field (name "DB_APPROVED_BY") "VSN")
      )
      (libsource (lib "Database_Libs1") (part "C"))
    )
    (comp (ref "C248")
      (value "C")
      (footprint "SMD_1210_CAPC3225X279N")
      (fields
        (field (name "DB_PART_NUMBER") "CAP000047355")
        (field (name "DB_VALUE") "220uF")
        (field (name "DB_TOLERANCE") "20%")
        (field (name "DB_VOLTAGE") "6.3V")
        (field (name "DB_MANUFACTURER_PART") "SAMSUNG    CL32A227MQVNNNE")
        (field (name "DB_APPROVED_BY") "VSN")
      )
      (libsource (lib "Database_Libs1") (part "C"))
    )
    (comp (ref "C249")
      (value "C")
      (footprint "SMD_1210_CAPC3225X279N")
      (fields
        (field (name "DB_PART_NUMBER") "CAP000047355")
        (field (name "DB_VALUE") "220uF")
        (field (name "DB_TOLERANCE") "20%")
        (field (name "DB_VOLTAGE") "6.3V")
        (field (name "DB_MANUFACTURER_PART") "SAMSUNG    CL32A227MQVNNNE")
        (field (name "DB_APPROVED_BY") "VSN")
      )
      (libsource (lib "Database_Libs1") (part "C"))
    )
    (comp (ref "C250")
      (value "C")
      (footprint "SMD_1210_CAPC3225X279N")
      (fields
        (field (name "DB_PART_NUMBER") "CAP000047355")
        (field (name "DB_VALUE") "220uF")
        (field (name "DB_TOLERANCE") "20%")
        (field (name "DB_VOLTAGE") "6.3V")
        (field (name "DB_MANUFACTURER_PART") "SAMSUNG    CL32A227MQVNNNE")
        (field (name "DB_APPROVED_BY") "VSN")
      )
      (libsource (lib "Database_Libs1") (part "C"))
    )
    (comp (ref "C251")
      (value "C")
      (footprint "SMD_1210_CAPC3225X279N")
      (fields
        (field (name "DB_PART_NUMBER") "CAP000047355")
        (field (name "DB_VALUE") "220uF")
        (field (name "DB_TOLERANCE") "20%")
        (field (name "DB_VOLTAGE") "6.3V")
        (field (name "DB_MANUFACTURER_PART") "SAMSUNG    CL32A227MQVNNNE")
        (field (name "DB_APPROVED_BY") "VSN")
      )
      (libsource (lib "Database_Libs1") (part "C"))
    )
    (comp (ref "C252")
      (value "C")
      (footprint "SMD_1210_CAPC3225X279N")
      (fields
        (field (name "DB_PART_NUMBER") "CAP000047355")
        (field (name "DB_VALUE") "220uF")
        (field (name "DB_TOLERANCE") "20%")
        (field (name "DB_VOLTAGE") "6.3V")
        (field (name "DB_MANUFACTURER_PART") "SAMSUNG    CL32A227MQVNNNE")
        (field (name "DB_APPROVED_BY") "VSN")
      )
      (libsource (lib "Database_Libs1") (part "C"))
    )
    (comp (ref "C253")
      (value "C")
      (footprint "SMD_1210_CAPC3225X279N")
      (fields
        (field (name "DB_PART_NUMBER") "CAP000047355")
        (field (name "DB_VALUE") "220uF")
        (field (name "DB_TOLERANCE") "20%")
        (field (name "DB_VOLTAGE") "6.3V")
        (field (name "DB_MANUFACTURER_PART") "SAMSUNG    CL32A227MQVNNNE")
        (field (name "DB_APPROVED_BY") "VSN")
      )
      (libsource (lib "Database_Libs1") (part "C"))
    )
    (comp (ref "C254")
      (value "C")
      (footprint "SMD_1210_CAPC3225X279N")
      (fields
        (field (name "DB_PART_NUMBER") "CAP000047355")
        (field (name "DB_VALUE") "220uF")
        (field (name "DB_TOLERANCE") "20%")
        (field (name "DB_VOLTAGE") "6.3V")
        (field (name "DB_MANUFACTURER_PART") "SAMSUNG    CL32A227MQVNNNE")
        (field (name "DB_APPROVED_BY") "VSN")
      )
      (libsource (lib "Database_Libs1") (part "C"))
    )
    (comp (ref "C255")
      (value "C")
      (footprint "SMD_1210_CAPC3225X279N")
      (fields
        (field (name "DB_PART_NUMBER") "CAP000047355")
        (field (name "DB_VALUE") "220uF")
        (field (name "DB_TOLERANCE") "20%")
        (field (name "DB_VOLTAGE") "6.3V")
        (field (name "DB_MANUFACTURER_PART") "SAMSUNG    CL32A227MQVNNNE")
        (field (name "DB_APPROVED_BY") "VSN")
      )
      (libsource (lib "Database_Libs1") (part "C"))
    )
    (comp (ref "C256")
      (value "C")
      (footprint "SMD_1210_CAPC3225X279N")
      (fields
        (field (name "DB_PART_NUMBER") "CAP000047355")
        (field (name "DB_VALUE") "220uF")
        (field (name "DB_TOLERANCE") "20%")
        (field (name "DB_VOLTAGE") "6.3V")
        (field (name "DB_MANUFACTURER_PART") "SAMSUNG    CL32A227MQVNNNE")
        (field (name "DB_APPROVED_BY") "VSN")
      )
      (libsource (lib "Database_Libs1") (part "C"))
    )
    (comp (ref "C257")
      (value "C")
      (footprint "SMD_1210_CAPC3225X279N")
      (fields
        (field (name "DB_PART_NUMBER") "CAP000047355")
        (field (name "DB_VALUE") "220uF")
        (field (name "DB_TOLERANCE") "20%")
        (field (name "DB_VOLTAGE") "6.3V")
        (field (name "DB_MANUFACTURER_PART") "SAMSUNG    CL32A227MQVNNNE")
        (field (name "DB_APPROVED_BY") "VSN")
      )
      (libsource (lib "Database_Libs1") (part "C"))
    )
    (comp (ref "C258")
      (value "C")
      (footprint "SMD_1210_CAPC3225X279N")
      (fields
        (field (name "DB_PART_NUMBER") "CAP000047355")
        (field (name "DB_VALUE") "220uF")
        (field (name "DB_TOLERANCE") "20%")
        (field (name "DB_VOLTAGE") "6.3V")
        (field (name "DB_MANUFACTURER_PART") "SAMSUNG    CL32A227MQVNNNE")
        (field (name "DB_APPROVED_BY") "VSN")
      )
      (libsource (lib "Database_Libs1") (part "C"))
    )
    (comp (ref "C259")
      (value "C")
      (footprint "SMD_1210_CAPC3225X279N")
      (fields
        (field (name "DB_PART_NUMBER") "CAP000047355")
        (field (name "DB_VALUE") "220uF")
        (field (name "DB_TOLERANCE") "20%")
        (field (name "DB_VOLTAGE") "6.3V")
        (field (name "DB_MANUFACTURER_PART") "SAMSUNG    CL32A227MQVNNNE")
        (field (name "DB_APPROVED_BY") "VSN")
      )
      (libsource (lib "Database_Libs1") (part "C"))
    )
    (comp (ref "C260")
      (value "C")
      (footprint "SMD_1210_CAPC3225X279N")
      (fields
        (field (name "DB_PART_NUMBER") "CAP000047355")
        (field (name "DB_VALUE") "220uF")
        (field (name "DB_TOLERANCE") "20%")
        (field (name "DB_VOLTAGE") "6.3V")
        (field (name "DB_MANUFACTURER_PART") "SAMSUNG    CL32A227MQVNNNE")
        (field (name "DB_APPROVED_BY") "VSN")
      )
      (libsource (lib "Database_Libs1") (part "C"))
    )
    (comp (ref "C261")
      (value "C")
      (footprint "SMD_1210_CAPC3225X279N")
      (fields
        (field (name "DB_PART_NUMBER") "CAP000047355")
        (field (name "DB_VALUE") "220uF")
        (field (name "DB_TOLERANCE") "20%")
        (field (name "DB_VOLTAGE") "6.3V")
        (field (name "DB_MANUFACTURER_PART") "SAMSUNG    CL32A227MQVNNNE")
        (field (name "DB_APPROVED_BY") "VSN")
      )
      (libsource (lib "Database_Libs1") (part "C"))
    )
    (comp (ref "C262")
      (value "C")
      (footprint "SMD_1210_CAPC3225X279N")
      (fields
        (field (name "DB_PART_NUMBER") "CAP000047355")
        (field (name "DB_VALUE") "220uF")
        (field (name "DB_TOLERANCE") "20%")
        (field (name "DB_VOLTAGE") "6.3V")
        (field (name "DB_MANUFACTURER_PART") "SAMSUNG    CL32A227MQVNNNE")
        (field (name "DB_APPROVED_BY") "VSN")
      )
      (libsource (lib "Database_Libs1") (part "C"))
    )
    (comp (ref "C263")
      (value "C")
      (footprint "SMD_1210_CAPC3225X279N")
      (fields
        (field (name "DB_PART_NUMBER") "CAP000047355")
        (field (name "DB_VALUE") "220uF")
        (field (name "DB_TOLERANCE") "20%")
        (field (name "DB_VOLTAGE") "6.3V")
        (field (name "DB_MANUFACTURER_PART") "SAMSUNG    CL32A227MQVNNNE")
        (field (name "DB_APPROVED_BY") "VSN")
      )
      (libsource (lib "Database_Libs1") (part "C"))
    )
    (comp (ref "C264")
      (value "C")
      (footprint "SMD_1210_CAPC3225X279N")
      (fields
        (field (name "DB_PART_NUMBER") "CAP000047355")
        (field (name "DB_VALUE") "220uF")
        (field (name "DB_TOLERANCE") "20%")
        (field (name "DB_VOLTAGE") "6.3V")
        (field (name "DB_MANUFACTURER_PART") "SAMSUNG    CL32A227MQVNNNE")
        (field (name "DB_APPROVED_BY") "VSN")
      )
      (libsource (lib "Database_Libs1") (part "C"))
    )
    (comp (ref "C265")
      (value "C")
      (footprint "SMD_1210_CAPC3225X279N")
      (fields
        (field (name "DB_PART_NUMBER") "CAP000047355")
        (field (name "DB_VALUE") "220uF")
        (field (name "DB_TOLERANCE") "20%")
        (field (name "DB_VOLTAGE") "6.3V")
        (field (name "DB_MANUFACTURER_PART") "SAMSUNG    CL32A227MQVNNNE")
        (field (name "DB_APPROVED_BY") "VSN")
      )
      (libsource (lib "Database_Libs1") (part "C"))
    )
    (comp (ref "C266")
      (value "C")
      (footprint "SMD_1210_CAPC3225X279N")
      (fields
        (field (name "DB_PART_NUMBER") "CAP000047355")
        (field (name "DB_VALUE") "220uF")
        (field (name "DB_TOLERANCE") "20%")
        (field (name "DB_VOLTAGE") "6.3V")
        (field (name "DB_MANUFACTURER_PART") "SAMSUNG    CL32A227MQVNNNE")
        (field (name "DB_APPROVED_BY") "VSN")
      )
      (libsource (lib "Database_Libs1") (part "C"))
    )
    (comp (ref "U1") (value "Golden_Nonce") (libsource (lib "Schlib1") (part "Golden_Nonce")))
  )
  (nets
    (net (code "1") (name "1V") (class "Default")
      (node (ref "C188") (pin "2") (pinfunction "2_2") (pintype "passive"))
      (node (ref "C189") (pin "2") (pinfunction "2_2") (pintype "passive"))
      (node (ref "C19") (pin "2") (pinfunction "2_2") (pintype "passive"))
      (node (ref "C190") (pin "2") (pinfunction "2_2") (pintype "passive"))
      (node (ref "C191") (pin "2") (pinfunction "2_2") (pintype "passive"))
      (node (ref "C192") (pin "2") (pinfunction "2_2") (pintype "passive"))
      (node (ref "C193") (pin "2") (pinfunction "2_2") (pintype "passive"))
      (node (ref "C194") (pin "2") (pinfunction "2_2") (pintype "passive"))
      (node (ref "C195") (pin "2") (pinfunction "2_2") (pintype "passive"))
      (node (ref "C196") (pin "2") (pinfunction "2_2") (pintype "passive"))
      (node (ref "C197") (pin "2") (pinfunction "2_2") (pintype "passive"))
      (node (ref "C198") (pin "2") (pinfunction "2_2") (pintype "passive"))
      (node (ref "C199") (pin "2") (pinfunction "2_2") (pintype "passive"))
      (node (ref "C200") (pin "2") (pinfunction "2_2") (pintype "passive"))
      (node (ref "C201") (pin "2") (pinfunction "2_2") (pintype "passive"))
      (node (ref "C202") (pin "2") (pinfunction "2_2") (pintype "passive"))
      (node (ref "C203") (pin "2") (pinfunction "2_2") (pintype "passive"))
      (node (ref "C204") (pin "2") (pinfunction "2_2") (pintype "passive"))
      (node (ref "C205") (pin "2") (pinfunction "2_2") (pintype "passive"))
      (node (ref "C206") (pin "2") (pinfunction "2_2") (pintype "passive"))
      (node (ref "C207") (pin "2") (pinfunction "2_2") (pintype "passive"))
      (node (ref "C208") (pin "2") (pinfunction "2_2") (pintype "passive"))
      (node (ref "C209") (pin "2") (pinfunction "2_2") (pintype "passive"))
      (node (ref "C210") (pin "2") (pinfunction "2_2") (pintype "passive"))
      (node (ref "C211") (pin "2") (pinfunction "2_2") (pintype "passive"))
      (node (ref "C212") (pin "2") (pinfunction "2_2") (pintype "passive"))
      (node (ref "C213") (pin "2") (pinfunction "2_2") (pintype "passive"))
      (node (ref "C214") (pin "2") (pinfunction "2_2") (pintype "passive"))
      (node (ref "C215") (pin "2") (pinfunction "2_2") (pintype "passive"))
      (node (ref "C216") (pin "2") (pinfunction "2_2") (pintype "passive"))
      (node (ref "C217") (pin "2") (pinfunction "2_2") (pintype "passive"))
      (node (ref "C218") (pin "2") (pinfunction "2_2") (pintype "passive"))
      (node (ref "C219") (pin "2") (pinfunction "2_2") (pintype "passive"))
      (node (ref "C220") (pin "2") (pinfunction "2_2") (pintype "passive"))
      (node (ref "C221") (pin "2") (pinfunction "2_2") (pintype "passive"))
      (node (ref "C222") (pin "2") (pinfunction "2_2") (pintype "passive"))
      (node (ref "C223") (pin "2") (pinfunction "2_2") (pintype "passive"))
      (node (ref "C224") (pin "2") (pinfunction "2_2") (pintype "passive"))
      (node (ref "C225") (pin "2") (pinfunction "2_2") (pintype "passive"))
      (node (ref "C226") (pin "2") (pinfunction "2_2") (pintype "passive"))
      (node (ref "C227") (pin "2") (pinfunction "2_2") (pintype "passive"))
      (node (ref "C228") (pin "2") (pinfunction "2_2") (pintype "passive"))
      (node (ref "C229") (pin "2") (pinfunction "2_2") (pintype "passive"))
      (node (ref "C230") (pin "2") (pinfunction "2_2") (pintype "passive"))
      (node (ref "C231") (pin "2") (pinfunction "2_2") (pintype "passive"))
      (node (ref "C232") (pin "2") (pinfunction "2_2") (pintype "passive"))
      (node (ref "C233") (pin "2") (pinfunction "2_2") (pintype "passive"))
      (node (ref "C234") (pin "2") (pinfunction "2_2") (pintype "passive"))
      (node (ref "C235") (pin "2") (pinfunction "2_2") (pintype "passive"))
      (node (ref "C237") (pin "2") (pinfunction "2_2") (pintype "passive"))
      (node (ref "C238") (pin "2") (pinfunction "2_2") (pintype "passive"))
      (node (ref "C239") (pin "2") (pinfunction "2_2") (pintype "passive"))
      (node (ref "C240") (pin "2") (pinfunction "2_2") (pintype "passive"))
      (node (ref "C241") (pin "2") (pinfunction "2_2") (pintype "passive"))
      (node (ref "C242") (pin "2") (pinfunction "2_2") (pintype "passive"))
      (node (ref "C243") (pin "2") (pinfunction "2_2") (pintype "passive"))
      (node (ref "C244") (pin "2") (pinfunction "2_2") (pintype "passive"))
      (node (ref "C245") (pin "2") (pinfunction "2_2") (pintype "passive"))
      (node (ref "C246") (pin "2") (pinfunction "2_2") (pintype "passive"))
      (node (ref "C247") (pin "2") (pinfunction "2_2") (pintype "passive"))
      (node (ref "C248") (pin "2") (pinfunction "2_2") (pintype "passive"))
      (node (ref "C249") (pin "2") (pinfunction "2_2") (pintype "passive"))
      (node (ref "C250") (pin "2") (pinfunction "2_2") (pintype "passive"))
      (node (ref "C251") (pin "2") (pinfunction "2_2") (pintype "passive"))
      (node (ref "C252") (pin "2") (pinfunction "2_2") (pintype "passive"))
      (node (ref "C253") (pin "2") (pinfunction "2_2") (pintype "passive"))
      (node (ref "C254") (pin "2") (pinfunction "2_2") (pintype "passive"))
      (node (ref "C255") (pin "2") (pinfunction "2_2") (pintype "passive"))
      (node (ref "C256") (pin "2") (pinfunction "2_2") (pintype "passive"))
      (node (ref "C257") (pin "2") (pinfunction "2_2") (pintype "passive"))
      (node (ref "C258") (pin "2") (pinfunction "2_2") (pintype "passive"))
      (node (ref "C259") (pin "2") (pinfunction "2_2") (pintype "passive"))
      (node (ref "C260") (pin "2") (pinfunction "2_2") (pintype "passive"))
      (node (ref "C261") (pin "2") (pinfunction "2_2") (pintype "passive"))
      (node (ref "C262") (pin "2") (pinfunction "2_2") (pintype "passive"))
      (node (ref "C263") (pin "2") (pinfunction "2_2") (pintype "passive"))
      (node (ref "C264") (pin "2") (pinfunction "2_2") (pintype "passive"))
      (node (ref "C265") (pin "2") (pinfunction "2_2") (pintype "passive"))
      (node (ref "C266") (pin "2") (pinfunction "2_2") (pintype "passive"))
      (node (ref "C36") (pin "2") (pinfunction "2_2") (pintype "passive"))
      (node (ref "U1") (pin "A2") (pinfunction "VDD_D1_A2") (pintype "passive"))
      (node (ref "U1") (pin "A22") (pinfunction "VDD_D1_A22") (pintype "passive"))
      (node (ref "U1") (pin "A23") (pinfunction "VDD_D2_A23") (pintype "passive"))
      (node (ref "U1") (pin "A37") (pinfunction "VDD_D2_A37") (pintype "passive"))
      (node (ref "U1") (pin "A39") (pinfunction "VDD_D2_A39") (pintype "passive"))
      (node (ref "U1") (pin "A4") (pinfunction "VDD_D1_A4") (pintype "passive"))
      (node (ref "U1") (pin "A41") (pinfunction "VDD_D2_A41") (pintype "passive"))
      (node (ref "U1") (pin "A43") (pinfunction "VDD_D2_A43") (pintype "passive"))
      (node (ref "U1") (pin "A6") (pinfunction "VDD_D1_A6") (pintype "passive"))
      (node (ref "U1") (pin "A8") (pinfunction "VDD_D1_A8") (pintype "passive"))
      (node (ref "U1") (pin "AA10") (pinfunction "VDD_D1_AA10") (pintype "passive"))
      (node (ref "U1") (pin "AA12") (pinfunction "VDD_D1_AA12") (pintype "passive"))
      (node (ref "U1") (pin "AA14") (pinfunction "VDD_D1_AA14") (pintype "passive"))
      (node (ref "U1") (pin "AA16") (pinfunction "VDD_D1_AA16") (pintype "passive"))
      (node (ref "U1") (pin "AA18") (pinfunction "VDD_D1_AA18") (pintype "passive"))
      (node (ref "U1") (pin "AA2") (pinfunction "VDD_D1_AA2") (pintype "passive"))
      (node (ref "U1") (pin "AA20") (pinfunction "VDD_D1_AA20") (pintype "passive"))
      (node (ref "U1") (pin "AA22") (pinfunction "VDD_D1_AA22") (pintype "passive"))
      (node (ref "U1") (pin "AA23") (pinfunction "VDD_D2_AA23") (pintype "passive"))
      (node (ref "U1") (pin "AA25") (pinfunction "VDD_D2_AA25") (pintype "passive"))
      (node (ref "U1") (pin "AA27") (pinfunction "VDD_D2_AA27") (pintype "passive"))
      (node (ref "U1") (pin "AA29") (pinfunction "VDD_D2_AA29") (pintype "passive"))
      (node (ref "U1") (pin "AA31") (pinfunction "VDD_D2_AA31") (pintype "passive"))
      (node (ref "U1") (pin "AA33") (pinfunction "VDD_D2_AA33") (pintype "passive"))
      (node (ref "U1") (pin "AA35") (pinfunction "VDD_D2_AA35") (pintype "passive"))
      (node (ref "U1") (pin "AA37") (pinfunction "VDD_D2_AA37") (pintype "passive"))
      (node (ref "U1") (pin "AA39") (pinfunction "VDD_D2_AA39") (pintype "passive"))
      (node (ref "U1") (pin "AA4") (pinfunction "VDD_D1_AA4") (pintype "passive"))
      (node (ref "U1") (pin "AA41") (pinfunction "VDD_D2_AA41") (pintype "passive"))
      (node (ref "U1") (pin "AA43") (pinfunction "VDD_D2_AA43") (pintype "passive"))
      (node (ref "U1") (pin "AA6") (pinfunction "VDD_D1_AA6") (pintype "passive"))
      (node (ref "U1") (pin "AA8") (pinfunction "VDD_D1_AA8") (pintype "passive"))
      (node (ref "U1") (pin "AB1") (pinfunction "VDD_D1_AB1") (pintype "passive"))
      (node (ref "U1") (pin "AB11") (pinfunction "VDD_D1_AB11") (pintype "passive"))
      (node (ref "U1") (pin "AB13") (pinfunction "VDD_D1_AB13") (pintype "passive"))
      (node (ref "U1") (pin "AB15") (pinfunction "VDD_D1_AB15") (pintype "passive"))
      (node (ref "U1") (pin "AB17") (pinfunction "VDD_D1_AB17") (pintype "passive"))
      (node (ref "U1") (pin "AB19") (pinfunction "VDD_D1_AB19") (pintype "passive"))
      (node (ref "U1") (pin "AB21") (pinfunction "VDD_D1_AB21") (pintype "passive"))
      (node (ref "U1") (pin "AB24") (pinfunction "VDD_D2_AB24") (pintype "passive"))
      (node (ref "U1") (pin "AB26") (pinfunction "VDD_D2_AB26") (pintype "passive"))
      (node (ref "U1") (pin "AB28") (pinfunction "VDD_D2_AB28") (pintype "passive"))
      (node (ref "U1") (pin "AB3") (pinfunction "VDD_D1_AB3") (pintype "passive"))
      (node (ref "U1") (pin "AB30") (pinfunction "VDD_D2_AB30") (pintype "passive"))
      (node (ref "U1") (pin "AB32") (pinfunction "VDD_D2_AB32") (pintype "passive"))
      (node (ref "U1") (pin "AB34") (pinfunction "VDD_D2_AB34") (pintype "passive"))
      (node (ref "U1") (pin "AB36") (pinfunction "VDD_D2_AB36") (pintype "passive"))
      (node (ref "U1") (pin "AB38") (pinfunction "VDD_D2_AB38") (pintype "passive"))
      (node (ref "U1") (pin "AB40") (pinfunction "VDD_D2_AB40") (pintype "passive"))
      (node (ref "U1") (pin "AB42") (pinfunction "VDD_D2_AB42") (pintype "passive"))
      (node (ref "U1") (pin "AB44") (pinfunction "VDD_D2_AB44") (pintype "passive"))
      (node (ref "U1") (pin "AB5") (pinfunction "VDD_D1_AB5") (pintype "passive"))
      (node (ref "U1") (pin "AB7") (pinfunction "VDD_D1_AB7") (pintype "passive"))
      (node (ref "U1") (pin "AB9") (pinfunction "VDD_D1_AB9") (pintype "passive"))
      (node (ref "U1") (pin "AC1") (pinfunction "VDD_D4_AC1") (pintype "passive"))
      (node (ref "U1") (pin "AC11") (pinfunction "VDD_D4_AC11") (pintype "passive"))
      (node (ref "U1") (pin "AC13") (pinfunction "VDD_D4_AC13") (pintype "passive"))
      (node (ref "U1") (pin "AC15") (pinfunction "VDD_D4_AC15") (pintype "passive"))
      (node (ref "U1") (pin "AC17") (pinfunction "VDD_D4_AC17") (pintype "passive"))
      (node (ref "U1") (pin "AC19") (pinfunction "VDD_D4_AC19") (pintype "passive"))
      (node (ref "U1") (pin "AC21") (pinfunction "VDD_D4_AC21") (pintype "passive"))
      (node (ref "U1") (pin "AC24") (pinfunction "VDD_D3_AC24") (pintype "passive"))
      (node (ref "U1") (pin "AC26") (pinfunction "VDD_D3_AC26") (pintype "passive"))
      (node (ref "U1") (pin "AC28") (pinfunction "VDD_D3_AC28") (pintype "passive"))
      (node (ref "U1") (pin "AC3") (pinfunction "VDD_D4_AC3") (pintype "passive"))
      (node (ref "U1") (pin "AC30") (pinfunction "VDD_D3_AC30") (pintype "passive"))
      (node (ref "U1") (pin "AC32") (pinfunction "VDD_D3_AC32") (pintype "passive"))
      (node (ref "U1") (pin "AC34") (pinfunction "VDD_D3_AC34") (pintype "passive"))
      (node (ref "U1") (pin "AC36") (pinfunction "VDD_D3_AC36") (pintype "passive"))
      (node (ref "U1") (pin "AC38") (pinfunction "VDD_D3_AC38") (pintype "passive"))
      (node (ref "U1") (pin "AC40") (pinfunction "VDD_D3_AC40") (pintype "passive"))
      (node (ref "U1") (pin "AC42") (pinfunction "VDD_D3_AC42") (pintype "passive"))
      (node (ref "U1") (pin "AC44") (pinfunction "VDD_D3_AC44") (pintype "passive"))
      (node (ref "U1") (pin "AC5") (pinfunction "VDD_D4_AC5") (pintype "passive"))
      (node (ref "U1") (pin "AC7") (pinfunction "VDD_D4_AC7") (pintype "passive"))
      (node (ref "U1") (pin "AC9") (pinfunction "VDD_D4_AC9") (pintype "passive"))
      (node (ref "U1") (pin "AD10") (pinfunction "VDD_D4_AD10") (pintype "passive"))
      (node (ref "U1") (pin "AD12") (pinfunction "VDD_D4_AD12") (pintype "passive"))
      (node (ref "U1") (pin "AD14") (pinfunction "VDD_D4_AD14") (pintype "passive"))
      (node (ref "U1") (pin "AD16") (pinfunction "VDD_D4_AD16") (pintype "passive"))
      (node (ref "U1") (pin "AD18") (pinfunction "VDD_D4_AD18") (pintype "passive"))
      (node (ref "U1") (pin "AD2") (pinfunction "VDD_D4_AD2") (pintype "passive"))
      (node (ref "U1") (pin "AD20") (pinfunction "VDD_D4_AD20") (pintype "passive"))
      (node (ref "U1") (pin "AD22") (pinfunction "VDD_D4_AD22") (pintype "passive"))
      (node (ref "U1") (pin "AD23") (pinfunction "VDD_D3_AD23") (pintype "passive"))
      (node (ref "U1") (pin "AD25") (pinfunction "VDD_D3_AD25") (pintype "passive"))
      (node (ref "U1") (pin "AD27") (pinfunction "VDD_D3_AD27") (pintype "passive"))
      (node (ref "U1") (pin "AD29") (pinfunction "VDD_D3_AD29") (pintype "passive"))
      (node (ref "U1") (pin "AD31") (pinfunction "VDD_D3_AD31") (pintype "passive"))
      (node (ref "U1") (pin "AD33") (pinfunction "VDD_D3_AD33") (pintype "passive"))
      (node (ref "U1") (pin "AD35") (pinfunction "VDD_D3_AD35") (pintype "passive"))
      (node (ref "U1") (pin "AD37") (pinfunction "VDD_D3_AD37") (pintype "passive"))
      (node (ref "U1") (pin "AD39") (pinfunction "VDD_D3_AD39") (pintype "passive"))
      (node (ref "U1") (pin "AD4") (pinfunction "VDD_D4_AD4") (pintype "passive"))
      (node (ref "U1") (pin "AD41") (pinfunction "VDD_D3_AD41") (pintype "passive"))
      (node (ref "U1") (pin "AD43") (pinfunction "VDD_D3_AD43") (pintype "passive"))
      (node (ref "U1") (pin "AD6") (pinfunction "VDD_D4_AD6") (pintype "passive"))
      (node (ref "U1") (pin "AD8") (pinfunction "VDD_D4_AD8") (pintype "passive"))
      (node (ref "U1") (pin "AE1") (pinfunction "VDD_D4_AE1") (pintype "passive"))
      (node (ref "U1") (pin "AE11") (pinfunction "VDD_D4_AE11") (pintype "passive"))
      (node (ref "U1") (pin "AE13") (pinfunction "VDD_D4_AE13") (pintype "passive"))
      (node (ref "U1") (pin "AE15") (pinfunction "VDD_D4_AE15") (pintype "passive"))
      (node (ref "U1") (pin "AE17") (pinfunction "VDD_D4_AE17") (pintype "passive"))
      (node (ref "U1") (pin "AE19") (pinfunction "VDD_D4_AE19") (pintype "passive"))
      (node (ref "U1") (pin "AE21") (pinfunction "VDD_D4_AE21") (pintype "passive"))
      (node (ref "U1") (pin "AE24") (pinfunction "VDD_D3_AE24") (pintype "passive"))
      (node (ref "U1") (pin "AE26") (pinfunction "VDD_D3_AE26") (pintype "passive"))
      (node (ref "U1") (pin "AE28") (pinfunction "VDD_D3_AE28") (pintype "passive"))
      (node (ref "U1") (pin "AE3") (pinfunction "VDD_D4_AE3") (pintype "passive"))
      (node (ref "U1") (pin "AE30") (pinfunction "VDD_D3_AE30") (pintype "passive"))
      (node (ref "U1") (pin "AE32") (pinfunction "VDD_D3_AE32") (pintype "passive"))
      (node (ref "U1") (pin "AE34") (pinfunction "VDD_D3_AE34") (pintype "passive"))
      (node (ref "U1") (pin "AE36") (pinfunction "VDD_D3_AE36") (pintype "passive"))
      (node (ref "U1") (pin "AE38") (pinfunction "VDD_D3_AE38") (pintype "passive"))
      (node (ref "U1") (pin "AE40") (pinfunction "VDD_D3_AE40") (pintype "passive"))
      (node (ref "U1") (pin "AE42") (pinfunction "VDD_D3_AE42") (pintype "passive"))
      (node (ref "U1") (pin "AE44") (pinfunction "VDD_D3_AE44") (pintype "passive"))
      (node (ref "U1") (pin "AE5") (pinfunction "VDD_D4_AE5") (pintype "passive"))
      (node (ref "U1") (pin "AE7") (pinfunction "VDD_D4_AE7") (pintype "passive"))
      (node (ref "U1") (pin "AE9") (pinfunction "VDD_D4_AE9") (pintype "passive"))
      (node (ref "U1") (pin "AF10") (pinfunction "VDD_D4_AF10") (pintype "passive"))
      (node (ref "U1") (pin "AF12") (pinfunction "VDD_D4_AF12") (pintype "passive"))
      (node (ref "U1") (pin "AF14") (pinfunction "VDD_D4_AF14") (pintype "passive"))
      (node (ref "U1") (pin "AF16") (pinfunction "VDD_D4_AF16") (pintype "passive"))
      (node (ref "U1") (pin "AF18") (pinfunction "VDD_D4_AF18") (pintype "passive"))
      (node (ref "U1") (pin "AF2") (pinfunction "VDD_D4_AF2") (pintype "passive"))
      (node (ref "U1") (pin "AF20") (pinfunction "VDD_D4_AF20") (pintype "passive"))
      (node (ref "U1") (pin "AF22") (pinfunction "VDD_D4_AF22") (pintype "passive"))
      (node (ref "U1") (pin "AF23") (pinfunction "VDD_D3_AF23") (pintype "passive"))
      (node (ref "U1") (pin "AF25") (pinfunction "VDD_D3_AF25") (pintype "passive"))
      (node (ref "U1") (pin "AF27") (pinfunction "VDD_D3_AF27") (pintype "passive"))
      (node (ref "U1") (pin "AF29") (pinfunction "VDD_D3_AF29") (pintype "passive"))
      (node (ref "U1") (pin "AF31") (pinfunction "VDD_D3_AF31") (pintype "passive"))
      (node (ref "U1") (pin "AF33") (pinfunction "VDD_D3_AF33") (pintype "passive"))
      (node (ref "U1") (pin "AF35") (pinfunction "VDD_D3_AF35") (pintype "passive"))
      (node (ref "U1") (pin "AF37") (pinfunction "VDD_D3_AF37") (pintype "passive"))
      (node (ref "U1") (pin "AF39") (pinfunction "VDD_D3_AF39") (pintype "passive"))
      (node (ref "U1") (pin "AF4") (pinfunction "VDD_D4_AF4") (pintype "passive"))
      (node (ref "U1") (pin "AF41") (pinfunction "VDD_D3_AF41") (pintype "passive"))
      (node (ref "U1") (pin "AF43") (pinfunction "VDD_D3_AF43") (pintype "passive"))
      (node (ref "U1") (pin "AF6") (pinfunction "VDD_D4_AF6") (pintype "passive"))
      (node (ref "U1") (pin "AF8") (pinfunction "VDD_D4_AF8") (pintype "passive"))
      (node (ref "U1") (pin "AG1") (pinfunction "VDD_D4_AG1") (pintype "passive"))
      (node (ref "U1") (pin "AG11") (pinfunction "VDD_D4_AG11") (pintype "passive"))
      (node (ref "U1") (pin "AG13") (pinfunction "VDD_D4_AG13") (pintype "passive"))
      (node (ref "U1") (pin "AG15") (pinfunction "VDD_D4_AG15") (pintype "passive"))
      (node (ref "U1") (pin "AG17") (pinfunction "VDD_D4_AG17") (pintype "passive"))
      (node (ref "U1") (pin "AG19") (pinfunction "VDD_D4_AG19") (pintype "passive"))
      (node (ref "U1") (pin "AG21") (pinfunction "VDD_D4_AG21") (pintype "passive"))
      (node (ref "U1") (pin "AG24") (pinfunction "VDD_D3_AG24") (pintype "passive"))
      (node (ref "U1") (pin "AG26") (pinfunction "VDD_D3_AG26") (pintype "passive"))
      (node (ref "U1") (pin "AG28") (pinfunction "VDD_D3_AG28") (pintype "passive"))
      (node (ref "U1") (pin "AG3") (pinfunction "VDD_D4_AG3") (pintype "passive"))
      (node (ref "U1") (pin "AG30") (pinfunction "VDD_D3_AG30") (pintype "passive"))
      (node (ref "U1") (pin "AG32") (pinfunction "VDD_D3_AG32") (pintype "passive"))
      (node (ref "U1") (pin "AG34") (pinfunction "VDD_D3_AG34") (pintype "passive"))
      (node (ref "U1") (pin "AG36") (pinfunction "VDD_D3_AG36") (pintype "passive"))
      (node (ref "U1") (pin "AG38") (pinfunction "VDD_D3_AG38") (pintype "passive"))
      (node (ref "U1") (pin "AG40") (pinfunction "VDD_D3_AG40") (pintype "passive"))
      (node (ref "U1") (pin "AG42") (pinfunction "VDD_D3_AG42") (pintype "passive"))
      (node (ref "U1") (pin "AG44") (pinfunction "VDD_D3_AG44") (pintype "passive"))
      (node (ref "U1") (pin "AG5") (pinfunction "VDD_D4_AG5") (pintype "passive"))
      (node (ref "U1") (pin "AG7") (pinfunction "VDD_D4_AG7") (pintype "passive"))
      (node (ref "U1") (pin "AG9") (pinfunction "VDD_D4_AG9") (pintype "passive"))
      (node (ref "U1") (pin "AH10") (pinfunction "VDD_D4_AH10") (pintype "passive"))
      (node (ref "U1") (pin "AH12") (pinfunction "VDD_D4_AH12") (pintype "passive"))
      (node (ref "U1") (pin "AH14") (pinfunction "VDD_D4_AH14") (pintype "passive"))
      (node (ref "U1") (pin "AH16") (pinfunction "VDD_D4_AH16") (pintype "passive"))
      (node (ref "U1") (pin "AH18") (pinfunction "VDD_D4_AH18") (pintype "passive"))
      (node (ref "U1") (pin "AH2") (pinfunction "VDD_D4_AH2") (pintype "passive"))
      (node (ref "U1") (pin "AH20") (pinfunction "VDD_D4_AH20") (pintype "passive"))
      (node (ref "U1") (pin "AH22") (pinfunction "VDD_D4_AH22") (pintype "passive"))
      (node (ref "U1") (pin "AH23") (pinfunction "VDD_D3_AH23") (pintype "passive"))
      (node (ref "U1") (pin "AH25") (pinfunction "VDD_D3_AH25") (pintype "passive"))
      (node (ref "U1") (pin "AH27") (pinfunction "VDD_D3_AH27") (pintype "passive"))
      (node (ref "U1") (pin "AH29") (pinfunction "VDD_D3_AH29") (pintype "passive"))
      (node (ref "U1") (pin "AH31") (pinfunction "VDD_D3_AH31") (pintype "passive"))
      (node (ref "U1") (pin "AH33") (pinfunction "VDD_D3_AH33") (pintype "passive"))
      (node (ref "U1") (pin "AH35") (pinfunction "VDD_D3_AH35") (pintype "passive"))
      (node (ref "U1") (pin "AH37") (pinfunction "VDD_D3_AH37") (pintype "passive"))
      (node (ref "U1") (pin "AH39") (pinfunction "VDD_D3_AH39") (pintype "passive"))
      (node (ref "U1") (pin "AH4") (pinfunction "VDD_D4_AH4") (pintype "passive"))
      (node (ref "U1") (pin "AH41") (pinfunction "VDD_D3_AH41") (pintype "passive"))
      (node (ref "U1") (pin "AH43") (pinfunction "VDD_D3_AH43") (pintype "passive"))
      (node (ref "U1") (pin "AH6") (pinfunction "VDD_D4_AH6") (pintype "passive"))
      (node (ref "U1") (pin "AH8") (pinfunction "VDD_D4_AH8") (pintype "passive"))
      (node (ref "U1") (pin "AJ1") (pinfunction "VDD_D4_AJ1") (pintype "passive"))
      (node (ref "U1") (pin "AJ11") (pinfunction "VDD_D4_AJ11") (pintype "passive"))
      (node (ref "U1") (pin "AJ13") (pinfunction "VDD_D4_AJ13") (pintype "passive"))
      (node (ref "U1") (pin "AJ15") (pinfunction "VDD_D4_AJ15") (pintype "passive"))
      (node (ref "U1") (pin "AJ17") (pinfunction "VDD_D4_AJ17") (pintype "passive"))
      (node (ref "U1") (pin "AJ19") (pinfunction "VDD_D4_AJ19") (pintype "passive"))
      (node (ref "U1") (pin "AJ21") (pinfunction "VDD_D4_AJ21") (pintype "passive"))
      (node (ref "U1") (pin "AJ24") (pinfunction "VDD_D3_AJ24") (pintype "passive"))
      (node (ref "U1") (pin "AJ26") (pinfunction "VDD_D3_AJ26") (pintype "passive"))
      (node (ref "U1") (pin "AJ28") (pinfunction "VDD_D3_AJ28") (pintype "passive"))
      (node (ref "U1") (pin "AJ3") (pinfunction "VDD_D4_AJ3") (pintype "passive"))
      (node (ref "U1") (pin "AJ30") (pinfunction "VDD_D3_AJ30") (pintype "passive"))
      (node (ref "U1") (pin "AJ32") (pinfunction "VDD_D3_AJ32") (pintype "passive"))
      (node (ref "U1") (pin "AJ34") (pinfunction "VDD_D3_AJ34") (pintype "passive"))
      (node (ref "U1") (pin "AJ36") (pinfunction "VDD_D3_AJ36") (pintype "passive"))
      (node (ref "U1") (pin "AJ38") (pinfunction "VDD_D3_AJ38") (pintype "passive"))
      (node (ref "U1") (pin "AJ40") (pinfunction "VDD_D3_AJ40") (pintype "passive"))
      (node (ref "U1") (pin "AJ42") (pinfunction "VDD_D3_AJ42") (pintype "passive"))
      (node (ref "U1") (pin "AJ44") (pinfunction "VDD_D3_AJ44") (pintype "passive"))
      (node (ref "U1") (pin "AJ5") (pinfunction "VDD_D4_AJ5") (pintype "passive"))
      (node (ref "U1") (pin "AJ7") (pinfunction "VDD_D4_AJ7") (pintype "passive"))
      (node (ref "U1") (pin "AJ9") (pinfunction "VDD_D4_AJ9") (pintype "passive"))
      (node (ref "U1") (pin "AK10") (pinfunction "VDD_D4_AK10") (pintype "passive"))
      (node (ref "U1") (pin "AK12") (pinfunction "VDD_D4_AK12") (pintype "passive"))
      (node (ref "U1") (pin "AK14") (pinfunction "VDD_D4_AK14") (pintype "passive"))
      (node (ref "U1") (pin "AK16") (pinfunction "VDD_D4_AK16") (pintype "passive"))
      (node (ref "U1") (pin "AK18") (pinfunction "VDD_D4_AK18") (pintype "passive"))
      (node (ref "U1") (pin "AK2") (pinfunction "VDD_D4_AK2") (pintype "passive"))
      (node (ref "U1") (pin "AK20") (pinfunction "VDD_D4_AK20") (pintype "passive"))
      (node (ref "U1") (pin "AK22") (pinfunction "VDD_D4_AK22") (pintype "passive"))
      (node (ref "U1") (pin "AK23") (pinfunction "VDD_D3_AK23") (pintype "passive"))
      (node (ref "U1") (pin "AK25") (pinfunction "VDD_D3_AK25") (pintype "passive"))
      (node (ref "U1") (pin "AK27") (pinfunction "VDD_D3_AK27") (pintype "passive"))
      (node (ref "U1") (pin "AK29") (pinfunction "VDD_D3_AK29") (pintype "passive"))
      (node (ref "U1") (pin "AK31") (pinfunction "VDD_D3_AK31") (pintype "passive"))
      (node (ref "U1") (pin "AK33") (pinfunction "VDD_D3_AK33") (pintype "passive"))
      (node (ref "U1") (pin "AK35") (pinfunction "VDD_D3_AK35") (pintype "passive"))
      (node (ref "U1") (pin "AK37") (pinfunction "VDD_D3_AK37") (pintype "passive"))
      (node (ref "U1") (pin "AK39") (pinfunction "VDD_D3_AK39") (pintype "passive"))
      (node (ref "U1") (pin "AK4") (pinfunction "VDD_D4_AK4") (pintype "passive"))
      (node (ref "U1") (pin "AK41") (pinfunction "VDD_D3_AK41") (pintype "passive"))
      (node (ref "U1") (pin "AK43") (pinfunction "VDD_D3_AK43") (pintype "passive"))
      (node (ref "U1") (pin "AK6") (pinfunction "VDD_D4_AK6") (pintype "passive"))
      (node (ref "U1") (pin "AK8") (pinfunction "VDD_D4_AK8") (pintype "passive"))
      (node (ref "U1") (pin "AL1") (pinfunction "VDD_D4_AL1") (pintype "passive"))
      (node (ref "U1") (pin "AL11") (pinfunction "VDD_D4_AL11") (pintype "passive"))
      (node (ref "U1") (pin "AL13") (pinfunction "VDD_D4_AL13") (pintype "passive"))
      (node (ref "U1") (pin "AL15") (pinfunction "VDD_D4_AL15") (pintype "passive"))
      (node (ref "U1") (pin "AL17") (pinfunction "VDD_D4_AL17") (pintype "passive"))
      (node (ref "U1") (pin "AL19") (pinfunction "VDD_D4_AL19") (pintype "passive"))
      (node (ref "U1") (pin "AL21") (pinfunction "VDD_D4_AL21") (pintype "passive"))
      (node (ref "U1") (pin "AL24") (pinfunction "VDD_D3_AL24") (pintype "passive"))
      (node (ref "U1") (pin "AL26") (pinfunction "VDD_D3_AL26") (pintype "passive"))
      (node (ref "U1") (pin "AL28") (pinfunction "VDD_D3_AL28") (pintype "passive"))
      (node (ref "U1") (pin "AL3") (pinfunction "VDD_D4_AL3") (pintype "passive"))
      (node (ref "U1") (pin "AL30") (pinfunction "VDD_D3_AL30") (pintype "passive"))
      (node (ref "U1") (pin "AL32") (pinfunction "VDD_D3_AL32") (pintype "passive"))
      (node (ref "U1") (pin "AL34") (pinfunction "VDD_D3_AL34") (pintype "passive"))
      (node (ref "U1") (pin "AL36") (pinfunction "VDD_D3_AL36") (pintype "passive"))
      (node (ref "U1") (pin "AL38") (pinfunction "VDD_D3_AL38") (pintype "passive"))
      (node (ref "U1") (pin "AL40") (pinfunction "VDD_D3_AL40") (pintype "passive"))
      (node (ref "U1") (pin "AL42") (pinfunction "VDD_D3_AL42") (pintype "passive"))
      (node (ref "U1") (pin "AL44") (pinfunction "VDD_D3_AL44") (pintype "passive"))
      (node (ref "U1") (pin "AL5") (pinfunction "VDD_D4_AL5") (pintype "passive"))
      (node (ref "U1") (pin "AL7") (pinfunction "VDD_D4_AL7") (pintype "passive"))
      (node (ref "U1") (pin "AL9") (pinfunction "VDD_D4_AL9") (pintype "passive"))
      (node (ref "U1") (pin "AM10") (pinfunction "VDD_D4_AM10") (pintype "passive"))
      (node (ref "U1") (pin "AM12") (pinfunction "VDD_D4_AM12") (pintype "passive"))
      (node (ref "U1") (pin "AM14") (pinfunction "VDD_D4_AM14") (pintype "passive"))
      (node (ref "U1") (pin "AM16") (pinfunction "VDD_D4_AM16") (pintype "passive"))
      (node (ref "U1") (pin "AM18") (pinfunction "VDD_D4_AM18") (pintype "passive"))
      (node (ref "U1") (pin "AM2") (pinfunction "VDD_D4_AM2") (pintype "passive"))
      (node (ref "U1") (pin "AM20") (pinfunction "VDD_D4_AM20") (pintype "passive"))
      (node (ref "U1") (pin "AM22") (pinfunction "VDD_D4_AM22") (pintype "passive"))
      (node (ref "U1") (pin "AM23") (pinfunction "VDD_D3_AM23") (pintype "passive"))
      (node (ref "U1") (pin "AM25") (pinfunction "VDD_D3_AM25") (pintype "passive"))
      (node (ref "U1") (pin "AM27") (pinfunction "VDD_D3_AM27") (pintype "passive"))
      (node (ref "U1") (pin "AM29") (pinfunction "VDD_D3_AM29") (pintype "passive"))
      (node (ref "U1") (pin "AM31") (pinfunction "VDD_D3_AM31") (pintype "passive"))
      (node (ref "U1") (pin "AM33") (pinfunction "VDD_D3_AM33") (pintype "passive"))
      (node (ref "U1") (pin "AM35") (pinfunction "VDD_D3_AM35") (pintype "passive"))
      (node (ref "U1") (pin "AM37") (pinfunction "VDD_D3_AM37") (pintype "passive"))
      (node (ref "U1") (pin "AM39") (pinfunction "VDD_D3_AM39") (pintype "passive"))
      (node (ref "U1") (pin "AM4") (pinfunction "VDD_D4_AM4") (pintype "passive"))
      (node (ref "U1") (pin "AM41") (pinfunction "VDD_D3_AM41") (pintype "passive"))
      (node (ref "U1") (pin "AM43") (pinfunction "VDD_D3_AM43") (pintype "passive"))
      (node (ref "U1") (pin "AM6") (pinfunction "VDD_D4_AM6") (pintype "passive"))
      (node (ref "U1") (pin "AM8") (pinfunction "VDD_D4_AM8") (pintype "passive"))
      (node (ref "U1") (pin "AN1") (pinfunction "VDD_D4_AN1") (pintype "passive"))
      (node (ref "U1") (pin "AN11") (pinfunction "VDD_D4_AN11") (pintype "passive"))
      (node (ref "U1") (pin "AN13") (pinfunction "VDD_D4_AN13") (pintype "passive"))
      (node (ref "U1") (pin "AN15") (pinfunction "VDD_D4_AN15") (pintype "passive"))
      (node (ref "U1") (pin "AN17") (pinfunction "VDD_D4_AN17") (pintype "passive"))
      (node (ref "U1") (pin "AN19") (pinfunction "VDD_D4_AN19") (pintype "passive"))
      (node (ref "U1") (pin "AN21") (pinfunction "VDD_D4_AN21") (pintype "passive"))
      (node (ref "U1") (pin "AN24") (pinfunction "VDD_D3_AN24") (pintype "passive"))
      (node (ref "U1") (pin "AN26") (pinfunction "VDD_D3_AN26") (pintype "passive"))
      (node (ref "U1") (pin "AN28") (pinfunction "VDD_D3_AN28") (pintype "passive"))
      (node (ref "U1") (pin "AN3") (pinfunction "VDD_D4_AN3") (pintype "passive"))
      (node (ref "U1") (pin "AN30") (pinfunction "VDD_D3_AN30") (pintype "passive"))
      (node (ref "U1") (pin "AN32") (pinfunction "VDD_D3_AN32") (pintype "passive"))
      (node (ref "U1") (pin "AN34") (pinfunction "VDD_D3_AN34") (pintype "passive"))
      (node (ref "U1") (pin "AN36") (pinfunction "VDD_D3_AN36") (pintype "passive"))
      (node (ref "U1") (pin "AN38") (pinfunction "VDD_D3_AN38") (pintype "passive"))
      (node (ref "U1") (pin "AN40") (pinfunction "VDD_D3_AN40") (pintype "passive"))
      (node (ref "U1") (pin "AN42") (pinfunction "VDD_D3_AN42") (pintype "passive"))
      (node (ref "U1") (pin "AN44") (pinfunction "VDD_D3_AN44") (pintype "passive"))
      (node (ref "U1") (pin "AN5") (pinfunction "VDD_D4_AN5") (pintype "passive"))
      (node (ref "U1") (pin "AN7") (pinfunction "VDD_D4_AN7") (pintype "passive"))
      (node (ref "U1") (pin "AN9") (pinfunction "VDD_D4_AN9") (pintype "passive"))
      (node (ref "U1") (pin "AP10") (pinfunction "VDD_D4_AP10") (pintype "passive"))
      (node (ref "U1") (pin "AP12") (pinfunction "VDD_D4_AP12") (pintype "passive"))
      (node (ref "U1") (pin "AP14") (pinfunction "VDD_D4_AP14") (pintype "passive"))
      (node (ref "U1") (pin "AP16") (pinfunction "VDD_D4_AP16") (pintype "passive"))
      (node (ref "U1") (pin "AP18") (pinfunction "VDD_D4_AP18") (pintype "passive"))
      (node (ref "U1") (pin "AP2") (pinfunction "VDD_D4_AP2") (pintype "passive"))
      (node (ref "U1") (pin "AP20") (pinfunction "VDD_D4_AP20") (pintype "passive"))
      (node (ref "U1") (pin "AP22") (pinfunction "VDD_D4_AP22") (pintype "passive"))
      (node (ref "U1") (pin "AP23") (pinfunction "VDD_D3_AP23") (pintype "passive"))
      (node (ref "U1") (pin "AP25") (pinfunction "VDD_D3_AP25") (pintype "passive"))
      (node (ref "U1") (pin "AP27") (pinfunction "VDD_D3_AP27") (pintype "passive"))
      (node (ref "U1") (pin "AP29") (pinfunction "VDD_D3_AP29") (pintype "passive"))
      (node (ref "U1") (pin "AP31") (pinfunction "VDD_D3_AP31") (pintype "passive"))
      (node (ref "U1") (pin "AP33") (pinfunction "VDD_D3_AP33") (pintype "passive"))
      (node (ref "U1") (pin "AP35") (pinfunction "VDD_D3_AP35") (pintype "passive"))
      (node (ref "U1") (pin "AP37") (pinfunction "VDD_D3_AP37") (pintype "passive"))
      (node (ref "U1") (pin "AP39") (pinfunction "VDD_D3_AP39") (pintype "passive"))
      (node (ref "U1") (pin "AP4") (pinfunction "VDD_D4_AP4") (pintype "passive"))
      (node (ref "U1") (pin "AP41") (pinfunction "VDD_D3_AP41") (pintype "passive"))
      (node (ref "U1") (pin "AP43") (pinfunction "VDD_D3_AP43") (pintype "passive"))
      (node (ref "U1") (pin "AP6") (pinfunction "VDD_D4_AP6") (pintype "passive"))
      (node (ref "U1") (pin "AP8") (pinfunction "VDD_D4_AP8") (pintype "passive"))
      (node (ref "U1") (pin "AR1") (pinfunction "VDD_D4_AR1") (pintype "passive"))
      (node (ref "U1") (pin "AR11") (pinfunction "VDD_D4_AR11") (pintype "passive"))
      (node (ref "U1") (pin "AR13") (pinfunction "VDD_D4_AR13") (pintype "passive"))
      (node (ref "U1") (pin "AR15") (pinfunction "VDD_D4_AR15") (pintype "passive"))
      (node (ref "U1") (pin "AR17") (pinfunction "VDD_D4_AR17") (pintype "passive"))
      (node (ref "U1") (pin "AR19") (pinfunction "VDD_D4_AR19") (pintype "passive"))
      (node (ref "U1") (pin "AR21") (pinfunction "VDD_D4_AR21") (pintype "passive"))
      (node (ref "U1") (pin "AR24") (pinfunction "VDD_D3_AR24") (pintype "passive"))
      (node (ref "U1") (pin "AR26") (pinfunction "VDD_D3_AR26") (pintype "passive"))
      (node (ref "U1") (pin "AR28") (pinfunction "VDD_D3_AR28") (pintype "passive"))
      (node (ref "U1") (pin "AR3") (pinfunction "VDD_D4_AR3") (pintype "passive"))
      (node (ref "U1") (pin "AR30") (pinfunction "VDD_D3_AR30") (pintype "passive"))
      (node (ref "U1") (pin "AR32") (pinfunction "VDD_D3_AR32") (pintype "passive"))
      (node (ref "U1") (pin "AR34") (pinfunction "VDD_D3_AR34") (pintype "passive"))
      (node (ref "U1") (pin "AR36") (pinfunction "VDD_D3_AR36") (pintype "passive"))
      (node (ref "U1") (pin "AR38") (pinfunction "VDD_D3_AR38") (pintype "passive"))
      (node (ref "U1") (pin "AR40") (pinfunction "VDD_D3_AR40") (pintype "passive"))
      (node (ref "U1") (pin "AR42") (pinfunction "VDD_D3_AR42") (pintype "passive"))
      (node (ref "U1") (pin "AR44") (pinfunction "VDD_D3_AR44") (pintype "passive"))
      (node (ref "U1") (pin "AR5") (pinfunction "VDD_D4_AR5") (pintype "passive"))
      (node (ref "U1") (pin "AR7") (pinfunction "VDD_D4_AR7") (pintype "passive"))
      (node (ref "U1") (pin "AR9") (pinfunction "VDD_D4_AR9") (pintype "passive"))
      (node (ref "U1") (pin "AT10") (pinfunction "VDD_D4_AT10") (pintype "passive"))
      (node (ref "U1") (pin "AT12") (pinfunction "VDD_D4_AT12") (pintype "passive"))
      (node (ref "U1") (pin "AT14") (pinfunction "VDD_D4_AT14") (pintype "passive"))
      (node (ref "U1") (pin "AT16") (pinfunction "VDD_D4_AT16") (pintype "passive"))
      (node (ref "U1") (pin "AT18") (pinfunction "VDD_D4_AT18") (pintype "passive"))
      (node (ref "U1") (pin "AT2") (pinfunction "VDD_D4_AT2") (pintype "passive"))
      (node (ref "U1") (pin "AT20") (pinfunction "VDD_D4_AT20") (pintype "passive"))
      (node (ref "U1") (pin "AT22") (pinfunction "VDD_D4_AT22") (pintype "passive"))
      (node (ref "U1") (pin "AT23") (pinfunction "VDD_D3_AT23") (pintype "passive"))
      (node (ref "U1") (pin "AT25") (pinfunction "VDD_D3_AT25") (pintype "passive"))
      (node (ref "U1") (pin "AT27") (pinfunction "VDD_D3_AT27") (pintype "passive"))
      (node (ref "U1") (pin "AT29") (pinfunction "VDD_D3_AT29") (pintype "passive"))
      (node (ref "U1") (pin "AT31") (pinfunction "VDD_D3_AT31") (pintype "passive"))
      (node (ref "U1") (pin "AT33") (pinfunction "VDD_D3_AT33") (pintype "passive"))
      (node (ref "U1") (pin "AT35") (pinfunction "VDD_D3_AT35") (pintype "passive"))
      (node (ref "U1") (pin "AT37") (pinfunction "VDD_D3_AT37") (pintype "passive"))
      (node (ref "U1") (pin "AT39") (pinfunction "VDD_D3_AT39") (pintype "passive"))
      (node (ref "U1") (pin "AT4") (pinfunction "VDD_D4_AT4") (pintype "passive"))
      (node (ref "U1") (pin "AT41") (pinfunction "VDD_D3_AT41") (pintype "passive"))
      (node (ref "U1") (pin "AT43") (pinfunction "VDD_D3_AT43") (pintype "passive"))
      (node (ref "U1") (pin "AT6") (pinfunction "VDD_D4_AT6") (pintype "passive"))
      (node (ref "U1") (pin "AT8") (pinfunction "VDD_D4_AT8") (pintype "passive"))
      (node (ref "U1") (pin "AU1") (pinfunction "VDD_D4_AU1") (pintype "passive"))
      (node (ref "U1") (pin "AU11") (pinfunction "VDD_D4_AU11") (pintype "passive"))
      (node (ref "U1") (pin "AU13") (pinfunction "VDD_D4_AU13") (pintype "passive"))
      (node (ref "U1") (pin "AU15") (pinfunction "VDD_D4_AU15") (pintype "passive"))
      (node (ref "U1") (pin "AU17") (pinfunction "VDD_D4_AU17") (pintype "passive"))
      (node (ref "U1") (pin "AU19") (pinfunction "VDD_D4_AU19") (pintype "passive"))
      (node (ref "U1") (pin "AU21") (pinfunction "VDD_D4_AU21") (pintype "passive"))
      (node (ref "U1") (pin "AU24") (pinfunction "VDD_D3_AU24") (pintype "passive"))
      (node (ref "U1") (pin "AU26") (pinfunction "VDD_D3_AU26") (pintype "passive"))
      (node (ref "U1") (pin "AU28") (pinfunction "VDD_D3_AU28") (pintype "passive"))
      (node (ref "U1") (pin "AU3") (pinfunction "VDD_D4_AU3") (pintype "passive"))
      (node (ref "U1") (pin "AU30") (pinfunction "VDD_D3_AU30") (pintype "passive"))
      (node (ref "U1") (pin "AU32") (pinfunction "VDD_D3_AU32") (pintype "passive"))
      (node (ref "U1") (pin "AU34") (pinfunction "VDD_D3_AU34") (pintype "passive"))
      (node (ref "U1") (pin "AU36") (pinfunction "VDD_D3_AU36") (pintype "passive"))
      (node (ref "U1") (pin "AU38") (pinfunction "VDD_D3_AU38") (pintype "passive"))
      (node (ref "U1") (pin "AU40") (pinfunction "VDD_D3_AU40") (pintype "passive"))
      (node (ref "U1") (pin "AU42") (pinfunction "VDD_D3_AU42") (pintype "passive"))
      (node (ref "U1") (pin "AU44") (pinfunction "VDD_D3_AU44") (pintype "passive"))
      (node (ref "U1") (pin "AU5") (pinfunction "VDD_D4_AU5") (pintype "passive"))
      (node (ref "U1") (pin "AU7") (pinfunction "VDD_D4_AU7") (pintype "passive"))
      (node (ref "U1") (pin "AU9") (pinfunction "VDD_D4_AU9") (pintype "passive"))
      (node (ref "U1") (pin "AV10") (pinfunction "VDD_D4_AV10") (pintype "passive"))
      (node (ref "U1") (pin "AV12") (pinfunction "VDD_D4_AV12") (pintype "passive"))
      (node (ref "U1") (pin "AV14") (pinfunction "VDD_D4_AV14") (pintype "passive"))
      (node (ref "U1") (pin "AV16") (pinfunction "VDD_D4_AV16") (pintype "passive"))
      (node (ref "U1") (pin "AV18") (pinfunction "VDD_D4_AV18") (pintype "passive"))
      (node (ref "U1") (pin "AV2") (pinfunction "VDD_D4_AV2") (pintype "passive"))
      (node (ref "U1") (pin "AV20") (pinfunction "VDD_D4_AV20") (pintype "passive"))
      (node (ref "U1") (pin "AV22") (pinfunction "VDD_D4_AV22") (pintype "passive"))
      (node (ref "U1") (pin "AV23") (pinfunction "VDD_D3_AV23") (pintype "passive"))
      (node (ref "U1") (pin "AV25") (pinfunction "VDD_D3_AV25") (pintype "passive"))
      (node (ref "U1") (pin "AV27") (pinfunction "VDD_D3_AV27") (pintype "passive"))
      (node (ref "U1") (pin "AV29") (pinfunction "VDD_D3_AV29") (pintype "passive"))
      (node (ref "U1") (pin "AV31") (pinfunction "VDD_D3_AV31") (pintype "passive"))
      (node (ref "U1") (pin "AV33") (pinfunction "VDD_D3_AV33") (pintype "passive"))
      (node (ref "U1") (pin "AV35") (pinfunction "VDD_D3_AV35") (pintype "passive"))
      (node (ref "U1") (pin "AV37") (pinfunction "VDD_D3_AV37") (pintype "passive"))
      (node (ref "U1") (pin "AV39") (pinfunction "VDD_D3_AV39") (pintype "passive"))
      (node (ref "U1") (pin "AV4") (pinfunction "VDD_D4_AV4") (pintype "passive"))
      (node (ref "U1") (pin "AV41") (pinfunction "VDD_D3_AV41") (pintype "passive"))
      (node (ref "U1") (pin "AV43") (pinfunction "VDD_D3_AV43") (pintype "passive"))
      (node (ref "U1") (pin "AV6") (pinfunction "VDD_D4_AV6") (pintype "passive"))
      (node (ref "U1") (pin "AV8") (pinfunction "VDD_D4_AV8") (pintype "passive"))
      (node (ref "U1") (pin "AW1") (pinfunction "VDD_D4_AW1") (pintype "passive"))
      (node (ref "U1") (pin "AW11") (pinfunction "VDD_D4_AW11") (pintype "passive"))
      (node (ref "U1") (pin "AW13") (pinfunction "VDD_D4_AW13") (pintype "passive"))
      (node (ref "U1") (pin "AW15") (pinfunction "VDD_D4_AW15") (pintype "passive"))
      (node (ref "U1") (pin "AW17") (pinfunction "VDD_D4_AW17") (pintype "passive"))
      (node (ref "U1") (pin "AW19") (pinfunction "VDD_D4_AW19") (pintype "passive"))
      (node (ref "U1") (pin "AW21") (pinfunction "VDD_D4_AW21") (pintype "passive"))
      (node (ref "U1") (pin "AW24") (pinfunction "VDD_D3_AW24") (pintype "passive"))
      (node (ref "U1") (pin "AW26") (pinfunction "VDD_D3_AW26") (pintype "passive"))
      (node (ref "U1") (pin "AW28") (pinfunction "VDD_D3_AW28") (pintype "passive"))
      (node (ref "U1") (pin "AW3") (pinfunction "VDD_D4_AW3") (pintype "passive"))
      (node (ref "U1") (pin "AW30") (pinfunction "VDD_D3_AW30") (pintype "passive"))
      (node (ref "U1") (pin "AW32") (pinfunction "VDD_D3_AW32") (pintype "passive"))
      (node (ref "U1") (pin "AW34") (pinfunction "VDD_D3_AW34") (pintype "passive"))
      (node (ref "U1") (pin "AW36") (pinfunction "VDD_D3_AW36") (pintype "passive"))
      (node (ref "U1") (pin "AW38") (pinfunction "VDD_D3_AW38") (pintype "passive"))
      (node (ref "U1") (pin "AW40") (pinfunction "VDD_D3_AW40") (pintype "passive"))
      (node (ref "U1") (pin "AW42") (pinfunction "VDD_D3_AW42") (pintype "passive"))
      (node (ref "U1") (pin "AW44") (pinfunction "VDD_D3_AW44") (pintype "passive"))
      (node (ref "U1") (pin "AW5") (pinfunction "VDD_D4_AW5") (pintype "passive"))
      (node (ref "U1") (pin "AW7") (pinfunction "VDD_D4_AW7") (pintype "passive"))
      (node (ref "U1") (pin "AW9") (pinfunction "VDD_D4_AW9") (pintype "passive"))
      (node (ref "U1") (pin "AY10") (pinfunction "VDD_D4_AY10") (pintype "passive"))
      (node (ref "U1") (pin "AY12") (pinfunction "VDD_D4_AY12") (pintype "passive"))
      (node (ref "U1") (pin "AY14") (pinfunction "VDD_D4_AY14") (pintype "passive"))
      (node (ref "U1") (pin "AY16") (pinfunction "VDD_D4_AY16") (pintype "passive"))
      (node (ref "U1") (pin "AY18") (pinfunction "VDD_D4_AY18") (pintype "passive"))
      (node (ref "U1") (pin "AY2") (pinfunction "VDD_D4_AY2") (pintype "passive"))
      (node (ref "U1") (pin "AY20") (pinfunction "VDD_D4_AY20") (pintype "passive"))
      (node (ref "U1") (pin "AY22") (pinfunction "VDD_D4_AY22") (pintype "passive"))
      (node (ref "U1") (pin "AY23") (pinfunction "VDD_D3_AY23") (pintype "passive"))
      (node (ref "U1") (pin "AY25") (pinfunction "VDD_D3_AY25") (pintype "passive"))
      (node (ref "U1") (pin "AY29") (pinfunction "VDD_D3_AY29") (pintype "passive"))
      (node (ref "U1") (pin "AY31") (pinfunction "VDD_D3_AY31") (pintype "passive"))
      (node (ref "U1") (pin "AY33") (pinfunction "VDD_D3_AY33") (pintype "passive"))
      (node (ref "U1") (pin "AY35") (pinfunction "VDD_D3_AY35") (pintype "passive"))
      (node (ref "U1") (pin "AY37") (pinfunction "VDD_D3_AY37") (pintype "passive"))
      (node (ref "U1") (pin "AY39") (pinfunction "VDD_D3_AY39") (pintype "passive"))
      (node (ref "U1") (pin "AY4") (pinfunction "VDD_D4_AY4") (pintype "passive"))
      (node (ref "U1") (pin "AY41") (pinfunction "VDD_D3_AY41") (pintype "passive"))
      (node (ref "U1") (pin "AY43") (pinfunction "VDD_D3_AY43") (pintype "passive"))
      (node (ref "U1") (pin "AY6") (pinfunction "VDD_D4_AY6") (pintype "passive"))
      (node (ref "U1") (pin "AY8") (pinfunction "VDD_D4_AY8") (pintype "passive"))
      (node (ref "U1") (pin "B1") (pinfunction "VDD_D1_B1") (pintype "passive"))
      (node (ref "U1") (pin "B21") (pinfunction "VDD_D1_B21") (pintype "passive"))
      (node (ref "U1") (pin "B3") (pinfunction "VDD_D1_B3") (pintype "passive"))
      (node (ref "U1") (pin "B36") (pinfunction "VDD_D2_B36") (pintype "passive"))
      (node (ref "U1") (pin "B38") (pinfunction "VDD_D2_B38") (pintype "passive"))
      (node (ref "U1") (pin "B40") (pinfunction "VDD_D2_B40") (pintype "passive"))
      (node (ref "U1") (pin "B42") (pinfunction "VDD_D2_B42") (pintype "passive"))
      (node (ref "U1") (pin "B44") (pinfunction "VDD_D2_B44") (pintype "passive"))
      (node (ref "U1") (pin "B5") (pinfunction "VDD_D1_B5") (pintype "passive"))
      (node (ref "U1") (pin "B7") (pinfunction "VDD_D1_B7") (pintype "passive"))
      (node (ref "U1") (pin "BA1") (pinfunction "VDD_D4_BA1") (pintype "passive"))
      (node (ref "U1") (pin "BA11") (pinfunction "VDD_D4_BA11") (pintype "passive"))
      (node (ref "U1") (pin "BA13") (pinfunction "VDD_D4_BA13") (pintype "passive"))
      (node (ref "U1") (pin "BA15") (pinfunction "VDD_D4_BA15") (pintype "passive"))
      (node (ref "U1") (pin "BA17") (pinfunction "VDD_D4_BA17") (pintype "passive"))
      (node (ref "U1") (pin "BA19") (pinfunction "VDD_D4_BA19") (pintype "passive"))
      (node (ref "U1") (pin "BA21") (pinfunction "VDD_D4_BA21") (pintype "passive"))
      (node (ref "U1") (pin "BA24") (pinfunction "VDD_D3_BA24") (pintype "passive"))
      (node (ref "U1") (pin "BA26") (pinfunction "VDD_D3_BA26") (pintype "passive"))
      (node (ref "U1") (pin "BA28") (pinfunction "VDD_D3_BA28") (pintype "passive"))
      (node (ref "U1") (pin "BA3") (pinfunction "VDD_D4_BA3") (pintype "passive"))
      (node (ref "U1") (pin "BA30") (pinfunction "VDD_D3_BA30") (pintype "passive"))
      (node (ref "U1") (pin "BA32") (pinfunction "VDD_D3_BA32") (pintype "passive"))
      (node (ref "U1") (pin "BA34") (pinfunction "VDD_D3_BA34") (pintype "passive"))
      (node (ref "U1") (pin "BA36") (pinfunction "VDD_D3_BA36") (pintype "passive"))
      (node (ref "U1") (pin "BA38") (pinfunction "VDD_D3_BA38") (pintype "passive"))
      (node (ref "U1") (pin "BA40") (pinfunction "VDD_D3_BA40") (pintype "passive"))
      (node (ref "U1") (pin "BA42") (pinfunction "VDD_D3_BA42") (pintype "passive"))
      (node (ref "U1") (pin "BA44") (pinfunction "VDD_D3_BA44") (pintype "passive"))
      (node (ref "U1") (pin "BA5") (pinfunction "VDD_D4_BA5") (pintype "passive"))
      (node (ref "U1") (pin "BA7") (pinfunction "VDD_D4_BA7") (pintype "passive"))
      (node (ref "U1") (pin "BA9") (pinfunction "VDD_D4_BA9") (pintype "passive"))
      (node (ref "U1") (pin "BB2") (pinfunction "VDD_D4_BB2") (pintype "passive"))
      (node (ref "U1") (pin "BB22") (pinfunction "VDD_D4_BB22") (pintype "passive"))
      (node (ref "U1") (pin "BB23") (pinfunction "VDD_D3_BB23") (pintype "passive"))
      (node (ref "U1") (pin "BB37") (pinfunction "VDD_D3_BB37") (pintype "passive"))
      (node (ref "U1") (pin "BB39") (pinfunction "VDD_D3_BB39") (pintype "passive"))
      (node (ref "U1") (pin "BB4") (pinfunction "VDD_D4_BB4") (pintype "passive"))
      (node (ref "U1") (pin "BB41") (pinfunction "VDD_D3_BB41") (pintype "passive"))
      (node (ref "U1") (pin "BB43") (pinfunction "VDD_D3_BB43") (pintype "passive"))
      (node (ref "U1") (pin "BB6") (pinfunction "VDD_D4_BB6") (pintype "passive"))
      (node (ref "U1") (pin "BB8") (pinfunction "VDD_D4_BB8") (pintype "passive"))
      (node (ref "U1") (pin "BC1") (pinfunction "VDD_D4_BC1") (pintype "passive"))
      (node (ref "U1") (pin "BC24") (pinfunction "VDD_D3_BC24") (pintype "passive"))
      (node (ref "U1") (pin "BC3") (pinfunction "VDD_D4_BC3") (pintype "passive"))
      (node (ref "U1") (pin "BC38") (pinfunction "VDD_D3_BC38") (pintype "passive"))
      (node (ref "U1") (pin "BC40") (pinfunction "VDD_D3_BC40") (pintype "passive"))
      (node (ref "U1") (pin "BC42") (pinfunction "VDD_D3_BC42") (pintype "passive"))
      (node (ref "U1") (pin "BC44") (pinfunction "VDD_D3_BC44") (pintype "passive"))
      (node (ref "U1") (pin "BC5") (pinfunction "VDD_D4_BC5") (pintype "passive"))
      (node (ref "U1") (pin "BC7") (pinfunction "VDD_D4_BC7") (pintype "passive"))
      (node (ref "U1") (pin "BD2") (pinfunction "VDD_D4_BD2") (pintype "passive"))
      (node (ref "U1") (pin "BD22") (pinfunction "VDD_D4_BD22") (pintype "passive"))
      (node (ref "U1") (pin "BD23") (pinfunction "VDD_D3_BD23") (pintype "passive"))
      (node (ref "U1") (pin "BD37") (pinfunction "VDD_D3_BD37") (pintype "passive"))
      (node (ref "U1") (pin "BD39") (pinfunction "VDD_D3_BD39") (pintype "passive"))
      (node (ref "U1") (pin "BD4") (pinfunction "VDD_D4_BD4") (pintype "passive"))
      (node (ref "U1") (pin "BD41") (pinfunction "VDD_D3_BD41") (pintype "passive"))
      (node (ref "U1") (pin "BD43") (pinfunction "VDD_D3_BD43") (pintype "passive"))
      (node (ref "U1") (pin "BD6") (pinfunction "VDD_D4_BD6") (pintype "passive"))
      (node (ref "U1") (pin "C2") (pinfunction "VDD_D1_C2") (pintype "passive"))
      (node (ref "U1") (pin "C22") (pinfunction "VDD_D1_C22") (pintype "passive"))
      (node (ref "U1") (pin "C23") (pinfunction "VDD_D2_C23") (pintype "passive"))
      (node (ref "U1") (pin "C37") (pinfunction "VDD_D2_C37") (pintype "passive"))
      (node (ref "U1") (pin "C39") (pinfunction "VDD_D2_C39") (pintype "passive"))
      (node (ref "U1") (pin "C4") (pinfunction "VDD_D1_C4") (pintype "passive"))
      (node (ref "U1") (pin "C41") (pinfunction "VDD_D2_C41") (pintype "passive"))
      (node (ref "U1") (pin "C43") (pinfunction "VDD_D2_C43") (pintype "passive"))
      (node (ref "U1") (pin "C6") (pinfunction "VDD_D1_C6") (pintype "passive"))
      (node (ref "U1") (pin "C8") (pinfunction "VDD_D1_C8") (pintype "passive"))
      (node (ref "U1") (pin "D1") (pinfunction "VDD_D1_D1") (pintype "passive"))
      (node (ref "U1") (pin "D11") (pinfunction "VDD_D1_D11") (pintype "passive"))
      (node (ref "U1") (pin "D13") (pinfunction "VDD_D1_D13") (pintype "passive"))
      (node (ref "U1") (pin "D15") (pinfunction "VDD_D1_D15") (pintype "passive"))
      (node (ref "U1") (pin "D17") (pinfunction "VDD_D1_D17") (pintype "passive"))
      (node (ref "U1") (pin "D19") (pinfunction "VDD_D1_D19") (pintype "passive"))
      (node (ref "U1") (pin "D21") (pinfunction "VDD_D1_D21") (pintype "passive"))
      (node (ref "U1") (pin "D24") (pinfunction "VDD_D2_D24") (pintype "passive"))
      (node (ref "U1") (pin "D26") (pinfunction "VDD_D2_D26") (pintype "passive"))
      (node (ref "U1") (pin "D28") (pinfunction "VDD_D2_D28") (pintype "passive"))
      (node (ref "U1") (pin "D3") (pinfunction "VDD_D1_D3") (pintype "passive"))
      (node (ref "U1") (pin "D30") (pinfunction "VDD_D2_D30") (pintype "passive"))
      (node (ref "U1") (pin "D32") (pinfunction "VDD_D2_D32") (pintype "passive"))
      (node (ref "U1") (pin "D34") (pinfunction "VDD_D2_D34") (pintype "passive"))
      (node (ref "U1") (pin "D36") (pinfunction "VDD_D2_D36") (pintype "passive"))
      (node (ref "U1") (pin "D38") (pinfunction "VDD_D2_D38") (pintype "passive"))
      (node (ref "U1") (pin "D40") (pinfunction "VDD_D2_D40") (pintype "passive"))
      (node (ref "U1") (pin "D42") (pinfunction "VDD_D2_D42") (pintype "passive"))
      (node (ref "U1") (pin "D44") (pinfunction "VDD_D2_D44") (pintype "passive"))
      (node (ref "U1") (pin "D5") (pinfunction "VDD_D1_D5") (pintype "passive"))
      (node (ref "U1") (pin "D7") (pinfunction "VDD_D1_D7") (pintype "passive"))
      (node (ref "U1") (pin "D9") (pinfunction "VDD_D1_D9") (pintype "passive"))
      (node (ref "U1") (pin "E10") (pinfunction "VDD_D1_E10") (pintype "passive"))
      (node (ref "U1") (pin "E12") (pinfunction "VDD_D1_E12") (pintype "passive"))
      (node (ref "U1") (pin "E14") (pinfunction "VDD_D1_E14") (pintype "passive"))
      (node (ref "U1") (pin "E16") (pinfunction "VDD_D1_E16") (pintype "passive"))
      (node (ref "U1") (pin "E18") (pinfunction "VDD_D1_E18") (pintype "passive"))
      (node (ref "U1") (pin "E2") (pinfunction "VDD_D1_E2") (pintype "passive"))
      (node (ref "U1") (pin "E20") (pinfunction "VDD_D1_E20") (pintype "passive"))
      (node (ref "U1") (pin "E22") (pinfunction "VDD_D1_E22") (pintype "passive"))
      (node (ref "U1") (pin "E23") (pinfunction "VDD_D2_E23") (pintype "passive"))
      (node (ref "U1") (pin "E25") (pinfunction "VDD_D2_E25") (pintype "passive"))
      (node (ref "U1") (pin "E29") (pinfunction "VDD_D2_E29") (pintype "passive"))
      (node (ref "U1") (pin "E31") (pinfunction "VDD_D2_E31") (pintype "passive"))
      (node (ref "U1") (pin "E33") (pinfunction "VDD_D2_E33") (pintype "passive"))
      (node (ref "U1") (pin "E35") (pinfunction "VDD_D2_E35") (pintype "passive"))
      (node (ref "U1") (pin "E37") (pinfunction "VDD_D2_E37") (pintype "passive"))
      (node (ref "U1") (pin "E39") (pinfunction "VDD_D2_E39") (pintype "passive"))
      (node (ref "U1") (pin "E4") (pinfunction "VDD_D1_E4") (pintype "passive"))
      (node (ref "U1") (pin "E41") (pinfunction "VDD_D2_E41") (pintype "passive"))
      (node (ref "U1") (pin "E43") (pinfunction "VDD_D2_E43") (pintype "passive"))
      (node (ref "U1") (pin "E6") (pinfunction "VDD_D1_E6") (pintype "passive"))
      (node (ref "U1") (pin "E8") (pinfunction "VDD_D1_E8") (pintype "passive"))
      (node (ref "U1") (pin "F1") (pinfunction "VDD_D1_F1") (pintype "passive"))
      (node (ref "U1") (pin "F11") (pinfunction "VDD_D1_F11") (pintype "passive"))
      (node (ref "U1") (pin "F13") (pinfunction "VDD_D1_F13") (pintype "passive"))
      (node (ref "U1") (pin "F15") (pinfunction "VDD_D1_F15") (pintype "passive"))
      (node (ref "U1") (pin "F17") (pinfunction "VDD_D1_F17") (pintype "passive"))
      (node (ref "U1") (pin "F19") (pinfunction "VDD_D1_F19") (pintype "passive"))
      (node (ref "U1") (pin "F21") (pinfunction "VDD_D1_F21") (pintype "passive"))
      (node (ref "U1") (pin "F24") (pinfunction "VDD_D2_F24") (pintype "passive"))
      (node (ref "U1") (pin "F26") (pinfunction "VDD_D2_F26") (pintype "passive"))
      (node (ref "U1") (pin "F28") (pinfunction "VDD_D2_F28") (pintype "passive"))
      (node (ref "U1") (pin "F3") (pinfunction "VDD_D1_F3") (pintype "passive"))
      (node (ref "U1") (pin "F30") (pinfunction "VDD_D2_F30") (pintype "passive"))
      (node (ref "U1") (pin "F32") (pinfunction "VDD_D2_F32") (pintype "passive"))
      (node (ref "U1") (pin "F34") (pinfunction "VDD_D2_F34") (pintype "passive"))
      (node (ref "U1") (pin "F36") (pinfunction "VDD_D2_F36") (pintype "passive"))
      (node (ref "U1") (pin "F38") (pinfunction "VDD_D2_F38") (pintype "passive"))
      (node (ref "U1") (pin "F40") (pinfunction "VDD_D2_F40") (pintype "passive"))
      (node (ref "U1") (pin "F42") (pinfunction "VDD_D2_F42") (pintype "passive"))
      (node (ref "U1") (pin "F44") (pinfunction "VDD_D2_F44") (pintype "passive"))
      (node (ref "U1") (pin "F5") (pinfunction "VDD_D1_F5") (pintype "passive"))
      (node (ref "U1") (pin "F7") (pinfunction "VDD_D1_F7") (pintype "passive"))
      (node (ref "U1") (pin "F9") (pinfunction "VDD_D1_F9") (pintype "passive"))
      (node (ref "U1") (pin "G10") (pinfunction "VDD_D1_G10") (pintype "passive"))
      (node (ref "U1") (pin "G12") (pinfunction "VDD_D1_G12") (pintype "passive"))
      (node (ref "U1") (pin "G14") (pinfunction "VDD_D1_G14") (pintype "passive"))
      (node (ref "U1") (pin "G16") (pinfunction "VDD_D1_G16") (pintype "passive"))
      (node (ref "U1") (pin "G18") (pinfunction "VDD_D1_G18") (pintype "passive"))
      (node (ref "U1") (pin "G2") (pinfunction "VDD_D1_G2") (pintype "passive"))
      (node (ref "U1") (pin "G20") (pinfunction "VDD_D1_G20") (pintype "passive"))
      (node (ref "U1") (pin "G22") (pinfunction "VDD_D1_G22") (pintype "passive"))
      (node (ref "U1") (pin "G23") (pinfunction "VDD_D2_G23") (pintype "passive"))
      (node (ref "U1") (pin "G25") (pinfunction "VDD_D2_G25") (pintype "passive"))
      (node (ref "U1") (pin "G27") (pinfunction "VDD_D2_G27") (pintype "passive"))
      (node (ref "U1") (pin "G29") (pinfunction "VDD_D2_G29") (pintype "passive"))
      (node (ref "U1") (pin "G31") (pinfunction "VDD_D2_G31") (pintype "passive"))
      (node (ref "U1") (pin "G33") (pinfunction "VDD_D2_G33") (pintype "passive"))
      (node (ref "U1") (pin "G35") (pinfunction "VDD_D2_G35") (pintype "passive"))
      (node (ref "U1") (pin "G37") (pinfunction "VDD_D2_G37") (pintype "passive"))
      (node (ref "U1") (pin "G39") (pinfunction "VDD_D2_G39") (pintype "passive"))
      (node (ref "U1") (pin "G4") (pinfunction "VDD_D1_G4") (pintype "passive"))
      (node (ref "U1") (pin "G41") (pinfunction "VDD_D2_G41") (pintype "passive"))
      (node (ref "U1") (pin "G43") (pinfunction "VDD_D2_G43") (pintype "passive"))
      (node (ref "U1") (pin "G6") (pinfunction "VDD_D1_G6") (pintype "passive"))
      (node (ref "U1") (pin "G8") (pinfunction "VDD_D1_G8") (pintype "passive"))
      (node (ref "U1") (pin "H1") (pinfunction "VDD_D1_H1") (pintype "passive"))
      (node (ref "U1") (pin "H11") (pinfunction "VDD_D1_H11") (pintype "passive"))
      (node (ref "U1") (pin "H13") (pinfunction "VDD_D1_H13") (pintype "passive"))
      (node (ref "U1") (pin "H15") (pinfunction "VDD_D1_H15") (pintype "passive"))
      (node (ref "U1") (pin "H17") (pinfunction "VDD_D1_H17") (pintype "passive"))
      (node (ref "U1") (pin "H19") (pinfunction "VDD_D1_H19") (pintype "passive"))
      (node (ref "U1") (pin "H21") (pinfunction "VDD_D1_H21") (pintype "passive"))
      (node (ref "U1") (pin "H24") (pinfunction "VDD_D2_H24") (pintype "passive"))
      (node (ref "U1") (pin "H26") (pinfunction "VDD_D2_H26") (pintype "passive"))
      (node (ref "U1") (pin "H28") (pinfunction "VDD_D2_H28") (pintype "passive"))
      (node (ref "U1") (pin "H3") (pinfunction "VDD_D1_H3") (pintype "passive"))
      (node (ref "U1") (pin "H30") (pinfunction "VDD_D2_H30") (pintype "passive"))
      (node (ref "U1") (pin "H32") (pinfunction "VDD_D2_H32") (pintype "passive"))
      (node (ref "U1") (pin "H34") (pinfunction "VDD_D2_H34") (pintype "passive"))
      (node (ref "U1") (pin "H36") (pinfunction "VDD_D2_H36") (pintype "passive"))
      (node (ref "U1") (pin "H38") (pinfunction "VDD_D2_H38") (pintype "passive"))
      (node (ref "U1") (pin "H40") (pinfunction "VDD_D2_H40") (pintype "passive"))
      (node (ref "U1") (pin "H42") (pinfunction "VDD_D2_H42") (pintype "passive"))
      (node (ref "U1") (pin "H44") (pinfunction "VDD_D2_H44") (pintype "passive"))
      (node (ref "U1") (pin "H5") (pinfunction "VDD_D1_H5") (pintype "passive"))
      (node (ref "U1") (pin "H7") (pinfunction "VDD_D1_H7") (pintype "passive"))
      (node (ref "U1") (pin "H9") (pinfunction "VDD_D1_H9") (pintype "passive"))
      (node (ref "U1") (pin "J10") (pinfunction "VDD_D1_J10") (pintype "passive"))
      (node (ref "U1") (pin "J12") (pinfunction "VDD_D1_J12") (pintype "passive"))
      (node (ref "U1") (pin "J14") (pinfunction "VDD_D1_J14") (pintype "passive"))
      (node (ref "U1") (pin "J16") (pinfunction "VDD_D1_J16") (pintype "passive"))
      (node (ref "U1") (pin "J18") (pinfunction "VDD_D1_J18") (pintype "passive"))
      (node (ref "U1") (pin "J2") (pinfunction "VDD_D1_J2") (pintype "passive"))
      (node (ref "U1") (pin "J20") (pinfunction "VDD_D1_J20") (pintype "passive"))
      (node (ref "U1") (pin "J22") (pinfunction "VDD_D1_J22") (pintype "passive"))
      (node (ref "U1") (pin "J23") (pinfunction "VDD_D2_J23") (pintype "passive"))
      (node (ref "U1") (pin "J25") (pinfunction "VDD_D2_J25") (pintype "passive"))
      (node (ref "U1") (pin "J27") (pinfunction "VDD_D2_J27") (pintype "passive"))
      (node (ref "U1") (pin "J29") (pinfunction "VDD_D2_J29") (pintype "passive"))
      (node (ref "U1") (pin "J31") (pinfunction "VDD_D2_J31") (pintype "passive"))
      (node (ref "U1") (pin "J33") (pinfunction "VDD_D2_J33") (pintype "passive"))
      (node (ref "U1") (pin "J35") (pinfunction "VDD_D2_J35") (pintype "passive"))
      (node (ref "U1") (pin "J37") (pinfunction "VDD_D2_J37") (pintype "passive"))
      (node (ref "U1") (pin "J39") (pinfunction "VDD_D2_J39") (pintype "passive"))
      (node (ref "U1") (pin "J4") (pinfunction "VDD_D1_J4") (pintype "passive"))
      (node (ref "U1") (pin "J41") (pinfunction "VDD_D2_J41") (pintype "passive"))
      (node (ref "U1") (pin "J43") (pinfunction "VDD_D2_J43") (pintype "passive"))
      (node (ref "U1") (pin "J6") (pinfunction "VDD_D1_J6") (pintype "passive"))
      (node (ref "U1") (pin "J8") (pinfunction "VDD_D1_J8") (pintype "passive"))
      (node (ref "U1") (pin "K1") (pinfunction "VDD_D1_K1") (pintype "passive"))
      (node (ref "U1") (pin "K11") (pinfunction "VDD_D1_K11") (pintype "passive"))
      (node (ref "U1") (pin "K13") (pinfunction "VDD_D1_K13") (pintype "passive"))
      (node (ref "U1") (pin "K15") (pinfunction "VDD_D1_K15") (pintype "passive"))
      (node (ref "U1") (pin "K17") (pinfunction "VDD_D1_K17") (pintype "passive"))
      (node (ref "U1") (pin "K19") (pinfunction "VDD_D1_K19") (pintype "passive"))
      (node (ref "U1") (pin "K21") (pinfunction "VDD_D1_K21") (pintype "passive"))
      (node (ref "U1") (pin "K24") (pinfunction "VDD_D2_K24") (pintype "passive"))
      (node (ref "U1") (pin "K26") (pinfunction "VDD_D2_K26") (pintype "passive"))
      (node (ref "U1") (pin "K28") (pinfunction "VDD_D2_K28") (pintype "passive"))
      (node (ref "U1") (pin "K3") (pinfunction "VDD_D1_K3") (pintype "passive"))
      (node (ref "U1") (pin "K30") (pinfunction "VDD_D2_K30") (pintype "passive"))
      (node (ref "U1") (pin "K32") (pinfunction "VDD_D2_K32") (pintype "passive"))
      (node (ref "U1") (pin "K34") (pinfunction "VDD_D2_K34") (pintype "passive"))
      (node (ref "U1") (pin "K36") (pinfunction "VDD_D2_K36") (pintype "passive"))
      (node (ref "U1") (pin "K38") (pinfunction "VDD_D2_K38") (pintype "passive"))
      (node (ref "U1") (pin "K40") (pinfunction "VDD_D2_K40") (pintype "passive"))
      (node (ref "U1") (pin "K42") (pinfunction "VDD_D2_K42") (pintype "passive"))
      (node (ref "U1") (pin "K44") (pinfunction "VDD_D2_K44") (pintype "passive"))
      (node (ref "U1") (pin "K5") (pinfunction "VDD_D1_K5") (pintype "passive"))
      (node (ref "U1") (pin "K7") (pinfunction "VDD_D1_K7") (pintype "passive"))
      (node (ref "U1") (pin "K9") (pinfunction "VDD_D1_K9") (pintype "passive"))
      (node (ref "U1") (pin "L10") (pinfunction "VDD_D1_L10") (pintype "passive"))
      (node (ref "U1") (pin "L12") (pinfunction "VDD_D1_L12") (pintype "passive"))
      (node (ref "U1") (pin "L14") (pinfunction "VDD_D1_L14") (pintype "passive"))
      (node (ref "U1") (pin "L16") (pinfunction "VDD_D1_L16") (pintype "passive"))
      (node (ref "U1") (pin "L18") (pinfunction "VDD_D1_L18") (pintype "passive"))
      (node (ref "U1") (pin "L2") (pinfunction "VDD_D1_L2") (pintype "passive"))
      (node (ref "U1") (pin "L20") (pinfunction "VDD_D1_L20") (pintype "passive"))
      (node (ref "U1") (pin "L22") (pinfunction "VDD_D1_L22") (pintype "passive"))
      (node (ref "U1") (pin "L23") (pinfunction "VDD_D2_L23") (pintype "passive"))
      (node (ref "U1") (pin "L25") (pinfunction "VDD_D2_L25") (pintype "passive"))
      (node (ref "U1") (pin "L27") (pinfunction "VDD_D2_L27") (pintype "passive"))
      (node (ref "U1") (pin "L29") (pinfunction "VDD_D2_L29") (pintype "passive"))
      (node (ref "U1") (pin "L31") (pinfunction "VDD_D2_L31") (pintype "passive"))
      (node (ref "U1") (pin "L33") (pinfunction "VDD_D2_L33") (pintype "passive"))
      (node (ref "U1") (pin "L35") (pinfunction "VDD_D2_L35") (pintype "passive"))
      (node (ref "U1") (pin "L37") (pinfunction "VDD_D2_L37") (pintype "passive"))
      (node (ref "U1") (pin "L39") (pinfunction "VDD_D2_L39") (pintype "passive"))
      (node (ref "U1") (pin "L4") (pinfunction "VDD_D1_L4") (pintype "passive"))
      (node (ref "U1") (pin "L41") (pinfunction "VDD_D2_L41") (pintype "passive"))
      (node (ref "U1") (pin "L43") (pinfunction "VDD_D2_L43") (pintype "passive"))
      (node (ref "U1") (pin "L6") (pinfunction "VDD_D1_L6") (pintype "passive"))
      (node (ref "U1") (pin "L8") (pinfunction "VDD_D1_L8") (pintype "passive"))
      (node (ref "U1") (pin "M1") (pinfunction "VDD_D1_M1") (pintype "passive"))
      (node (ref "U1") (pin "M11") (pinfunction "VDD_D1_M11") (pintype "passive"))
      (node (ref "U1") (pin "M13") (pinfunction "VDD_D1_M13") (pintype "passive"))
      (node (ref "U1") (pin "M15") (pinfunction "VDD_D1_M15") (pintype "passive"))
      (node (ref "U1") (pin "M17") (pinfunction "VDD_D1_M17") (pintype "passive"))
      (node (ref "U1") (pin "M19") (pinfunction "VDD_D1_M19") (pintype "passive"))
      (node (ref "U1") (pin "M21") (pinfunction "VDD_D1_M21") (pintype "passive"))
      (node (ref "U1") (pin "M24") (pinfunction "VDD_D2_M24") (pintype "passive"))
      (node (ref "U1") (pin "M26") (pinfunction "VDD_D2_M26") (pintype "passive"))
      (node (ref "U1") (pin "M28") (pinfunction "VDD_D2_M28") (pintype "passive"))
      (node (ref "U1") (pin "M3") (pinfunction "VDD_D1_M3") (pintype "passive"))
      (node (ref "U1") (pin "M30") (pinfunction "VDD_D2_M30") (pintype "passive"))
      (node (ref "U1") (pin "M32") (pinfunction "VDD_D2_M32") (pintype "passive"))
      (node (ref "U1") (pin "M34") (pinfunction "VDD_D2_M34") (pintype "passive"))
      (node (ref "U1") (pin "M36") (pinfunction "VDD_D2_M36") (pintype "passive"))
      (node (ref "U1") (pin "M38") (pinfunction "VDD_D2_M38") (pintype "passive"))
      (node (ref "U1") (pin "M40") (pinfunction "VDD_D2_M40") (pintype "passive"))
      (node (ref "U1") (pin "M42") (pinfunction "VDD_D2_M42") (pintype "passive"))
      (node (ref "U1") (pin "M44") (pinfunction "VDD_D2_M44") (pintype "passive"))
      (node (ref "U1") (pin "M5") (pinfunction "VDD_D1_M5") (pintype "passive"))
      (node (ref "U1") (pin "M7") (pinfunction "VDD_D1_M7") (pintype "passive"))
      (node (ref "U1") (pin "M9") (pinfunction "VDD_D1_M9") (pintype "passive"))
      (node (ref "U1") (pin "N10") (pinfunction "VDD_D1_N10") (pintype "passive"))
      (node (ref "U1") (pin "N12") (pinfunction "VDD_D1_N12") (pintype "passive"))
      (node (ref "U1") (pin "N14") (pinfunction "VDD_D1_N14") (pintype "passive"))
      (node (ref "U1") (pin "N16") (pinfunction "VDD_D1_N16") (pintype "passive"))
      (node (ref "U1") (pin "N18") (pinfunction "VDD_D1_N18") (pintype "passive"))
      (node (ref "U1") (pin "N2") (pinfunction "VDD_D1_N2") (pintype "passive"))
      (node (ref "U1") (pin "N20") (pinfunction "VDD_D1_N20") (pintype "passive"))
      (node (ref "U1") (pin "N22") (pinfunction "VDD_D1_N22") (pintype "passive"))
      (node (ref "U1") (pin "N23") (pinfunction "VDD_D2_N23") (pintype "passive"))
      (node (ref "U1") (pin "N25") (pinfunction "VDD_D2_N25") (pintype "passive"))
      (node (ref "U1") (pin "N27") (pinfunction "VDD_D2_N27") (pintype "passive"))
      (node (ref "U1") (pin "N29") (pinfunction "VDD_D2_N29") (pintype "passive"))
      (node (ref "U1") (pin "N31") (pinfunction "VDD_D2_N31") (pintype "passive"))
      (node (ref "U1") (pin "N33") (pinfunction "VDD_D2_N33") (pintype "passive"))
      (node (ref "U1") (pin "N35") (pinfunction "VDD_D2_N35") (pintype "passive"))
      (node (ref "U1") (pin "N37") (pinfunction "VDD_D2_N37") (pintype "passive"))
      (node (ref "U1") (pin "N39") (pinfunction "VDD_D2_N39") (pintype "passive"))
      (node (ref "U1") (pin "N4") (pinfunction "VDD_D1_N4") (pintype "passive"))
      (node (ref "U1") (pin "N41") (pinfunction "VDD_D2_N41") (pintype "passive"))
      (node (ref "U1") (pin "N43") (pinfunction "VDD_D2_N43") (pintype "passive"))
      (node (ref "U1") (pin "N6") (pinfunction "VDD_D1_N6") (pintype "passive"))
      (node (ref "U1") (pin "N8") (pinfunction "VDD_D1_N8") (pintype "passive"))
      (node (ref "U1") (pin "P1") (pinfunction "VDD_D1_P1") (pintype "passive"))
      (node (ref "U1") (pin "P11") (pinfunction "VDD_D1_P11") (pintype "passive"))
      (node (ref "U1") (pin "P13") (pinfunction "VDD_D1_P13") (pintype "passive"))
      (node (ref "U1") (pin "P15") (pinfunction "VDD_D1_P15") (pintype "passive"))
      (node (ref "U1") (pin "P17") (pinfunction "VDD_D1_P17") (pintype "passive"))
      (node (ref "U1") (pin "P19") (pinfunction "VDD_D1_P19") (pintype "passive"))
      (node (ref "U1") (pin "P21") (pinfunction "VDD_D1_P21") (pintype "passive"))
      (node (ref "U1") (pin "P24") (pinfunction "VDD_D2_P24") (pintype "passive"))
      (node (ref "U1") (pin "P26") (pinfunction "VDD_D2_P26") (pintype "passive"))
      (node (ref "U1") (pin "P28") (pinfunction "VDD_D2_P28") (pintype "passive"))
      (node (ref "U1") (pin "P3") (pinfunction "VDD_D1_P3") (pintype "passive"))
      (node (ref "U1") (pin "P30") (pinfunction "VDD_D2_P30") (pintype "passive"))
      (node (ref "U1") (pin "P32") (pinfunction "VDD_D2_P32") (pintype "passive"))
      (node (ref "U1") (pin "P34") (pinfunction "VDD_D2_P34") (pintype "passive"))
      (node (ref "U1") (pin "P36") (pinfunction "VDD_D2_P36") (pintype "passive"))
      (node (ref "U1") (pin "P38") (pinfunction "VDD_D2_P38") (pintype "passive"))
      (node (ref "U1") (pin "P40") (pinfunction "VDD_D2_P40") (pintype "passive"))
      (node (ref "U1") (pin "P42") (pinfunction "VDD_D2_P42") (pintype "passive"))
      (node (ref "U1") (pin "P44") (pinfunction "VDD_D2_P44") (pintype "passive"))
      (node (ref "U1") (pin "P5") (pinfunction "VDD_D1_P5") (pintype "passive"))
      (node (ref "U1") (pin "P7") (pinfunction "VDD_D1_P7") (pintype "passive"))
      (node (ref "U1") (pin "P9") (pinfunction "VDD_D1_P9") (pintype "passive"))
      (node (ref "U1") (pin "R10") (pinfunction "VDD_D1_R10") (pintype "passive"))
      (node (ref "U1") (pin "R12") (pinfunction "VDD_D1_R12") (pintype "passive"))
      (node (ref "U1") (pin "R14") (pinfunction "VDD_D1_R14") (pintype "passive"))
      (node (ref "U1") (pin "R16") (pinfunction "VDD_D1_R16") (pintype "passive"))
      (node (ref "U1") (pin "R18") (pinfunction "VDD_D1_R18") (pintype "passive"))
      (node (ref "U1") (pin "R2") (pinfunction "VDD_D1_R2") (pintype "passive"))
      (node (ref "U1") (pin "R20") (pinfunction "VDD_D1_R20") (pintype "passive"))
      (node (ref "U1") (pin "R22") (pinfunction "VDD_D1_R22") (pintype "passive"))
      (node (ref "U1") (pin "R23") (pinfunction "VDD_D2_R23") (pintype "passive"))
      (node (ref "U1") (pin "R25") (pinfunction "VDD_D2_R25") (pintype "passive"))
      (node (ref "U1") (pin "R27") (pinfunction "VDD_D2_R27") (pintype "passive"))
      (node (ref "U1") (pin "R29") (pinfunction "VDD_D2_R29") (pintype "passive"))
      (node (ref "U1") (pin "R31") (pinfunction "VDD_D2_R31") (pintype "passive"))
      (node (ref "U1") (pin "R33") (pinfunction "VDD_D2_R33") (pintype "passive"))
      (node (ref "U1") (pin "R35") (pinfunction "VDD_D2_R35") (pintype "passive"))
      (node (ref "U1") (pin "R37") (pinfunction "VDD_D2_R37") (pintype "passive"))
      (node (ref "U1") (pin "R39") (pinfunction "VDD_D2_R39") (pintype "passive"))
      (node (ref "U1") (pin "R4") (pinfunction "VDD_D1_R4") (pintype "passive"))
      (node (ref "U1") (pin "R41") (pinfunction "VDD_D2_R41") (pintype "passive"))
      (node (ref "U1") (pin "R43") (pinfunction "VDD_D2_R43") (pintype "passive"))
      (node (ref "U1") (pin "R6") (pinfunction "VDD_D1_R6") (pintype "passive"))
      (node (ref "U1") (pin "R8") (pinfunction "VDD_D1_R8") (pintype "passive"))
      (node (ref "U1") (pin "T1") (pinfunction "VDD_D1_T1") (pintype "passive"))
      (node (ref "U1") (pin "T11") (pinfunction "VDD_D1_T11") (pintype "passive"))
      (node (ref "U1") (pin "T13") (pinfunction "VDD_D1_T13") (pintype "passive"))
      (node (ref "U1") (pin "T15") (pinfunction "VDD_D1_T15") (pintype "passive"))
      (node (ref "U1") (pin "T17") (pinfunction "VDD_D1_T17") (pintype "passive"))
      (node (ref "U1") (pin "T19") (pinfunction "VDD_D1_T19") (pintype "passive"))
      (node (ref "U1") (pin "T21") (pinfunction "VDD_D1_T21") (pintype "passive"))
      (node (ref "U1") (pin "T24") (pinfunction "VDD_D2_T24") (pintype "passive"))
      (node (ref "U1") (pin "T26") (pinfunction "VDD_D2_T26") (pintype "passive"))
      (node (ref "U1") (pin "T28") (pinfunction "VDD_D2_T28") (pintype "passive"))
      (node (ref "U1") (pin "T3") (pinfunction "VDD_D1_T3") (pintype "passive"))
      (node (ref "U1") (pin "T30") (pinfunction "VDD_D2_T30") (pintype "passive"))
      (node (ref "U1") (pin "T32") (pinfunction "VDD_D2_T32") (pintype "passive"))
      (node (ref "U1") (pin "T34") (pinfunction "VDD_D2_T34") (pintype "passive"))
      (node (ref "U1") (pin "T36") (pinfunction "VDD_D2_T36") (pintype "passive"))
      (node (ref "U1") (pin "T38") (pinfunction "VDD_D2_T38") (pintype "passive"))
      (node (ref "U1") (pin "T40") (pinfunction "VDD_D2_T40") (pintype "passive"))
      (node (ref "U1") (pin "T42") (pinfunction "VDD_D2_T42") (pintype "passive"))
      (node (ref "U1") (pin "T44") (pinfunction "VDD_D2_T44") (pintype "passive"))
      (node (ref "U1") (pin "T5") (pinfunction "VDD_D1_T5") (pintype "passive"))
      (node (ref "U1") (pin "T7") (pinfunction "VDD_D1_T7") (pintype "passive"))
      (node (ref "U1") (pin "T9") (pinfunction "VDD_D1_T9") (pintype "passive"))
      (node (ref "U1") (pin "U10") (pinfunction "VDD_D1_U10") (pintype "passive"))
      (node (ref "U1") (pin "U12") (pinfunction "VDD_D1_U12") (pintype "passive"))
      (node (ref "U1") (pin "U14") (pinfunction "VDD_D1_U14") (pintype "passive"))
      (node (ref "U1") (pin "U16") (pinfunction "VDD_D1_U16") (pintype "passive"))
      (node (ref "U1") (pin "U18") (pinfunction "VDD_D1_U18") (pintype "passive"))
      (node (ref "U1") (pin "U2") (pinfunction "VDD_D1_U2") (pintype "passive"))
      (node (ref "U1") (pin "U20") (pinfunction "VDD_D1_U20") (pintype "passive"))
      (node (ref "U1") (pin "U22") (pinfunction "VDD_D1_U22") (pintype "passive"))
      (node (ref "U1") (pin "U23") (pinfunction "VDD_D2_U23") (pintype "passive"))
      (node (ref "U1") (pin "U25") (pinfunction "VDD_D2_U25") (pintype "passive"))
      (node (ref "U1") (pin "U27") (pinfunction "VDD_D2_U27") (pintype "passive"))
      (node (ref "U1") (pin "U29") (pinfunction "VDD_D2_U29") (pintype "passive"))
      (node (ref "U1") (pin "U31") (pinfunction "VDD_D2_U31") (pintype "passive"))
      (node (ref "U1") (pin "U33") (pinfunction "VDD_D2_U33") (pintype "passive"))
      (node (ref "U1") (pin "U35") (pinfunction "VDD_D2_U35") (pintype "passive"))
      (node (ref "U1") (pin "U37") (pinfunction "VDD_D2_U37") (pintype "passive"))
      (node (ref "U1") (pin "U39") (pinfunction "VDD_D2_U39") (pintype "passive"))
      (node (ref "U1") (pin "U4") (pinfunction "VDD_D1_U4") (pintype "passive"))
      (node (ref "U1") (pin "U41") (pinfunction "VDD_D2_U41") (pintype "passive"))
      (node (ref "U1") (pin "U43") (pinfunction "VDD_D2_U43") (pintype "passive"))
      (node (ref "U1") (pin "U6") (pinfunction "VDD_D1_U6") (pintype "passive"))
      (node (ref "U1") (pin "U8") (pinfunction "VDD_D1_U8") (pintype "passive"))
      (node (ref "U1") (pin "V1") (pinfunction "VDD_D1_V1") (pintype "passive"))
      (node (ref "U1") (pin "V11") (pinfunction "VDD_D1_V11") (pintype "passive"))
      (node (ref "U1") (pin "V13") (pinfunction "VDD_D1_V13") (pintype "passive"))
      (node (ref "U1") (pin "V15") (pinfunction "VDD_D1_V15") (pintype "passive"))
      (node (ref "U1") (pin "V17") (pinfunction "VDD_D1_V17") (pintype "passive"))
      (node (ref "U1") (pin "V19") (pinfunction "VDD_D1_V19") (pintype "passive"))
      (node (ref "U1") (pin "V21") (pinfunction "VDD_D1_V21") (pintype "passive"))
      (node (ref "U1") (pin "V24") (pinfunction "VDD_D2_V24") (pintype "passive"))
      (node (ref "U1") (pin "V26") (pinfunction "VDD_D2_V26") (pintype "passive"))
      (node (ref "U1") (pin "V28") (pinfunction "VDD_D2_V28") (pintype "passive"))
      (node (ref "U1") (pin "V3") (pinfunction "VDD_D1_V3") (pintype "passive"))
      (node (ref "U1") (pin "V30") (pinfunction "VDD_D2_V30") (pintype "passive"))
      (node (ref "U1") (pin "V32") (pinfunction "VDD_D2_V32") (pintype "passive"))
      (node (ref "U1") (pin "V34") (pinfunction "VDD_D2_V34") (pintype "passive"))
      (node (ref "U1") (pin "V36") (pinfunction "VDD_D2_V36") (pintype "passive"))
      (node (ref "U1") (pin "V38") (pinfunction "VDD_D2_V38") (pintype "passive"))
      (node (ref "U1") (pin "V40") (pinfunction "VDD_D2_V40") (pintype "passive"))
      (node (ref "U1") (pin "V42") (pinfunction "VDD_D2_V42") (pintype "passive"))
      (node (ref "U1") (pin "V44") (pinfunction "VDD_D2_V44") (pintype "passive"))
      (node (ref "U1") (pin "V5") (pinfunction "VDD_D1_V5") (pintype "passive"))
      (node (ref "U1") (pin "V7") (pinfunction "VDD_D1_V7") (pintype "passive"))
      (node (ref "U1") (pin "V9") (pinfunction "VDD_D1_V9") (pintype "passive"))
      (node (ref "U1") (pin "W10") (pinfunction "VDD_D1_W10") (pintype "passive"))
      (node (ref "U1") (pin "W12") (pinfunction "VDD_D1_W12") (pintype "passive"))
      (node (ref "U1") (pin "W14") (pinfunction "VDD_D1_W14") (pintype "passive"))
      (node (ref "U1") (pin "W16") (pinfunction "VDD_D1_W16") (pintype "passive"))
      (node (ref "U1") (pin "W18") (pinfunction "VDD_D1_W18") (pintype "passive"))
      (node (ref "U1") (pin "W2") (pinfunction "VDD_D1_W2") (pintype "passive"))
      (node (ref "U1") (pin "W20") (pinfunction "VDD_D1_W20") (pintype "passive"))
      (node (ref "U1") (pin "W22") (pinfunction "VDD_D1_W22") (pintype "passive"))
      (node (ref "U1") (pin "W23") (pinfunction "VDD_D2_W23") (pintype "passive"))
      (node (ref "U1") (pin "W25") (pinfunction "VDD_D2_W25") (pintype "passive"))
      (node (ref "U1") (pin "W27") (pinfunction "VDD_D2_W27") (pintype "passive"))
      (node (ref "U1") (pin "W29") (pinfunction "VDD_D2_W29") (pintype "passive"))
      (node (ref "U1") (pin "W31") (pinfunction "VDD_D2_W31") (pintype "passive"))
      (node (ref "U1") (pin "W33") (pinfunction "VDD_D2_W33") (pintype "passive"))
      (node (ref "U1") (pin "W35") (pinfunction "VDD_D2_W35") (pintype "passive"))
      (node (ref "U1") (pin "W37") (pinfunction "VDD_D2_W37") (pintype "passive"))
      (node (ref "U1") (pin "W39") (pinfunction "VDD_D2_W39") (pintype "passive"))
      (node (ref "U1") (pin "W4") (pinfunction "VDD_D1_W4") (pintype "passive"))
      (node (ref "U1") (pin "W41") (pinfunction "VDD_D2_W41") (pintype "passive"))
      (node (ref "U1") (pin "W43") (pinfunction "VDD_D2_W43") (pintype "passive"))
      (node (ref "U1") (pin "W6") (pinfunction "VDD_D1_W6") (pintype "passive"))
      (node (ref "U1") (pin "W8") (pinfunction "VDD_D1_W8") (pintype "passive"))
      (node (ref "U1") (pin "Y1") (pinfunction "VDD_D1_Y1") (pintype "passive"))
      (node (ref "U1") (pin "Y11") (pinfunction "VDD_D1_Y11") (pintype "passive"))
      (node (ref "U1") (pin "Y13") (pinfunction "VDD_D1_Y13") (pintype "passive"))
      (node (ref "U1") (pin "Y15") (pinfunction "VDD_D1_Y15") (pintype "passive"))
      (node (ref "U1") (pin "Y17") (pinfunction "VDD_D1_Y17") (pintype "passive"))
      (node (ref "U1") (pin "Y19") (pinfunction "VDD_D1_Y19") (pintype "passive"))
      (node (ref "U1") (pin "Y21") (pinfunction "VDD_D1_Y21") (pintype "passive"))
      (node (ref "U1") (pin "Y24") (pinfunction "VDD_D2_Y24") (pintype "passive"))
      (node (ref "U1") (pin "Y26") (pinfunction "VDD_D2_Y26") (pintype "passive"))
      (node (ref "U1") (pin "Y28") (pinfunction "VDD_D2_Y28") (pintype "passive"))
      (node (ref "U1") (pin "Y3") (pinfunction "VDD_D1_Y3") (pintype "passive"))
      (node (ref "U1") (pin "Y30") (pinfunction "VDD_D2_Y30") (pintype "passive"))
      (node (ref "U1") (pin "Y32") (pinfunction "VDD_D2_Y32") (pintype "passive"))
      (node (ref "U1") (pin "Y34") (pinfunction "VDD_D2_Y34") (pintype "passive"))
      (node (ref "U1") (pin "Y36") (pinfunction "VDD_D2_Y36") (pintype "passive"))
      (node (ref "U1") (pin "Y38") (pinfunction "VDD_D2_Y38") (pintype "passive"))
      (node (ref "U1") (pin "Y40") (pinfunction "VDD_D2_Y40") (pintype "passive"))
      (node (ref "U1") (pin "Y42") (pinfunction "VDD_D2_Y42") (pintype "passive"))
      (node (ref "U1") (pin "Y44") (pinfunction "VDD_D2_Y44") (pintype "passive"))
      (node (ref "U1") (pin "Y5") (pinfunction "VDD_D1_Y5") (pintype "passive"))
      (node (ref "U1") (pin "Y7") (pinfunction "VDD_D1_Y7") (pintype "passive"))
      (node (ref "U1") (pin "Y9") (pinfunction "VDD_D1_Y9") (pintype "passive"))
    )
    (net (code "2") (name "GND") (class "Default")
      (node (ref "C188") (pin "1") (pinfunction "1_1") (pintype "passive"))
      (node (ref "C189") (pin "1") (pinfunction "1_1") (pintype "passive"))
      (node (ref "C19") (pin "1") (pinfunction "1_1") (pintype "passive"))
      (node (ref "C190") (pin "1") (pinfunction "1_1") (pintype "passive"))
      (node (ref "C191") (pin "1") (pinfunction "1_1") (pintype "passive"))
      (node (ref "C192") (pin "1") (pinfunction "1_1") (pintype "passive"))
      (node (ref "C193") (pin "1") (pinfunction "1_1") (pintype "passive"))
      (node (ref "C194") (pin "1") (pinfunction "1_1") (pintype "passive"))
      (node (ref "C195") (pin "1") (pinfunction "1_1") (pintype "passive"))
      (node (ref "C196") (pin "1") (pinfunction "1_1") (pintype "passive"))
      (node (ref "C197") (pin "1") (pinfunction "1_1") (pintype "passive"))
      (node (ref "C198") (pin "1") (pinfunction "1_1") (pintype "passive"))
      (node (ref "C199") (pin "1") (pinfunction "1_1") (pintype "passive"))
      (node (ref "C200") (pin "1") (pinfunction "1_1") (pintype "passive"))
      (node (ref "C201") (pin "1") (pinfunction "1_1") (pintype "passive"))
      (node (ref "C202") (pin "1") (pinfunction "1_1") (pintype "passive"))
      (node (ref "C203") (pin "1") (pinfunction "1_1") (pintype "passive"))
      (node (ref "C204") (pin "1") (pinfunction "1_1") (pintype "passive"))
      (node (ref "C205") (pin "1") (pinfunction "1_1") (pintype "passive"))
      (node (ref "C206") (pin "1") (pinfunction "1_1") (pintype "passive"))
      (node (ref "C207") (pin "1") (pinfunction "1_1") (pintype "passive"))
      (node (ref "C208") (pin "1") (pinfunction "1_1") (pintype "passive"))
      (node (ref "C209") (pin "1") (pinfunction "1_1") (pintype "passive"))
      (node (ref "C210") (pin "1") (pinfunction "1_1") (pintype "passive"))
      (node (ref "C211") (pin "1") (pinfunction "1_1") (pintype "passive"))
      (node (ref "C212") (pin "1") (pinfunction "1_1") (pintype "passive"))
      (node (ref "C213") (pin "1") (pinfunction "1_1") (pintype "passive"))
      (node (ref "C214") (pin "1") (pinfunction "1_1") (pintype "passive"))
      (node (ref "C215") (pin "1") (pinfunction "1_1") (pintype "passive"))
      (node (ref "C216") (pin "1") (pinfunction "1_1") (pintype "passive"))
      (node (ref "C217") (pin "1") (pinfunction "1_1") (pintype "passive"))
      (node (ref "C218") (pin "1") (pinfunction "1_1") (pintype "passive"))
      (node (ref "C219") (pin "1") (pinfunction "1_1") (pintype "passive"))
      (node (ref "C220") (pin "1") (pinfunction "1_1") (pintype "passive"))
      (node (ref "C221") (pin "1") (pinfunction "1_1") (pintype "passive"))
      (node (ref "C222") (pin "1") (pinfunction "1_1") (pintype "passive"))
      (node (ref "C223") (pin "1") (pinfunction "1_1") (pintype "passive"))
      (node (ref "C224") (pin "1") (pinfunction "1_1") (pintype "passive"))
      (node (ref "C225") (pin "1") (pinfunction "1_1") (pintype "passive"))
      (node (ref "C226") (pin "1") (pinfunction "1_1") (pintype "passive"))
      (node (ref "C227") (pin "1") (pinfunction "1_1") (pintype "passive"))
      (node (ref "C228") (pin "1") (pinfunction "1_1") (pintype "passive"))
      (node (ref "C229") (pin "1") (pinfunction "1_1") (pintype "passive"))
      (node (ref "C230") (pin "1") (pinfunction "1_1") (pintype "passive"))
      (node (ref "C231") (pin "1") (pinfunction "1_1") (pintype "passive"))
      (node (ref "C232") (pin "1") (pinfunction "1_1") (pintype "passive"))
      (node (ref "C233") (pin "1") (pinfunction "1_1") (pintype "passive"))
      (node (ref "C234") (pin "1") (pinfunction "1_1") (pintype "passive"))
      (node (ref "C235") (pin "1") (pinfunction "1_1") (pintype "passive"))
      (node (ref "C237") (pin "1") (pinfunction "1_1") (pintype "passive"))
      (node (ref "C238") (pin "1") (pinfunction "1_1") (pintype "passive"))
      (node (ref "C239") (pin "1") (pinfunction "1_1") (pintype "passive"))
      (node (ref "C240") (pin "1") (pinfunction "1_1") (pintype "passive"))
      (node (ref "C241") (pin "1") (pinfunction "1_1") (pintype "passive"))
      (node (ref "C242") (pin "1") (pinfunction "1_1") (pintype "passive"))
      (node (ref "C243") (pin "1") (pinfunction "1_1") (pintype "passive"))
      (node (ref "C244") (pin "1") (pinfunction "1_1") (pintype "passive"))
      (node (ref "C245") (pin "1") (pinfunction "1_1") (pintype "passive"))
      (node (ref "C246") (pin "1") (pinfunction "1_1") (pintype "passive"))
      (node (ref "C247") (pin "1") (pinfunction "1_1") (pintype "passive"))
      (node (ref "C248") (pin "1") (pinfunction "1_1") (pintype "passive"))
      (node (ref "C249") (pin "1") (pinfunction "1_1") (pintype "passive"))
      (node (ref "C250") (pin "1") (pinfunction "1_1") (pintype "passive"))
      (node (ref "C251") (pin "1") (pinfunction "1_1") (pintype "passive"))
      (node (ref "C252") (pin "1") (pinfunction "1_1") (pintype "passive"))
      (node (ref "C253") (pin "1") (pinfunction "1_1") (pintype "passive"))
      (node (ref "C254") (pin "1") (pinfunction "1_1") (pintype "passive"))
      (node (ref "C255") (pin "1") (pinfunction "1_1") (pintype "passive"))
      (node (ref "C256") (pin "1") (pinfunction "1_1") (pintype "passive"))
      (node (ref "C257") (pin "1") (pinfunction "1_1") (pintype "passive"))
      (node (ref "C258") (pin "1") (pinfunction "1_1") (pintype "passive"))
      (node (ref "C259") (pin "1") (pinfunction "1_1") (pintype "passive"))
      (node (ref "C260") (pin "1") (pinfunction "1_1") (pintype "passive"))
      (node (ref "C261") (pin "1") (pinfunction "1_1") (pintype "passive"))
      (node (ref "C262") (pin "1") (pinfunction "1_1") (pintype "passive"))
      (node (ref "C263") (pin "1") (pinfunction "1_1") (pintype "passive"))
      (node (ref "C264") (pin "1") (pinfunction "1_1") (pintype "passive"))
      (node (ref "C265") (pin "1") (pinfunction "1_1") (pintype "passive"))
      (node (ref "C266") (pin "1") (pinfunction "1_1") (pintype "passive"))
      (node (ref "C36") (pin "1") (pinfunction "1_1") (pintype "passive"))
      (node (ref "U1") (pin "A3") (pinfunction "VSS_A3") (pintype "passive"))
      (node (ref "U1") (pin "A38") (pinfunction "VSS_A38") (pintype "passive"))
      (node (ref "U1") (pin "A40") (pinfunction "VSS_A40") (pintype "passive"))
      (node (ref "U1") (pin "A42") (pinfunction "VSS_A42") (pintype "passive"))
      (node (ref "U1") (pin "A44") (pinfunction "VSS_A44") (pintype "passive"))
      (node (ref "U1") (pin "A5") (pinfunction "VSS_A5") (pintype "passive"))
      (node (ref "U1") (pin "A7") (pinfunction "VSS_A7") (pintype "passive"))
      (node (ref "U1") (pin "AA1") (pinfunction "VSS_AA1") (pintype "passive"))
      (node (ref "U1") (pin "AA11") (pinfunction "VSS_AA11") (pintype "passive"))
      (node (ref "U1") (pin "AA13") (pinfunction "VSS_AA13") (pintype "passive"))
      (node (ref "U1") (pin "AA15") (pinfunction "VSS_AA15") (pintype "passive"))
      (node (ref "U1") (pin "AA17") (pinfunction "VSS_AA17") (pintype "passive"))
      (node (ref "U1") (pin "AA19") (pinfunction "VSS_AA19") (pintype "passive"))
      (node (ref "U1") (pin "AA21") (pinfunction "VSS_AA21") (pintype "passive"))
      (node (ref "U1") (pin "AA24") (pinfunction "VSS_AA24") (pintype "passive"))
      (node (ref "U1") (pin "AA26") (pinfunction "VSS_AA26") (pintype "passive"))
      (node (ref "U1") (pin "AA28") (pinfunction "VSS_AA28") (pintype "passive"))
      (node (ref "U1") (pin "AA3") (pinfunction "VSS_AA3") (pintype "passive"))
      (node (ref "U1") (pin "AA30") (pinfunction "VSS_AA30") (pintype "passive"))
      (node (ref "U1") (pin "AA32") (pinfunction "VSS_AA32") (pintype "passive"))
      (node (ref "U1") (pin "AA34") (pinfunction "VSS_AA34") (pintype "passive"))
      (node (ref "U1") (pin "AA36") (pinfunction "VSS_AA36") (pintype "passive"))
      (node (ref "U1") (pin "AA38") (pinfunction "VSS_AA38") (pintype "passive"))
      (node (ref "U1") (pin "AA40") (pinfunction "VSS_AA40") (pintype "passive"))
      (node (ref "U1") (pin "AA42") (pinfunction "VSS_AA42") (pintype "passive"))
      (node (ref "U1") (pin "AA44") (pinfunction "VSS_AA44") (pintype "passive"))
      (node (ref "U1") (pin "AA5") (pinfunction "VSS_AA5") (pintype "passive"))
      (node (ref "U1") (pin "AA7") (pinfunction "VSS_AA7") (pintype "passive"))
      (node (ref "U1") (pin "AA9") (pinfunction "VSS_AA9") (pintype "passive"))
      (node (ref "U1") (pin "AB10") (pinfunction "VSS_AB10") (pintype "passive"))
      (node (ref "U1") (pin "AB12") (pinfunction "VSS_AB12") (pintype "passive"))
      (node (ref "U1") (pin "AB14") (pinfunction "VSS_AB14") (pintype "passive"))
      (node (ref "U1") (pin "AB16") (pinfunction "VSS_AB16") (pintype "passive"))
      (node (ref "U1") (pin "AB18") (pinfunction "VSS_AB18") (pintype "passive"))
      (node (ref "U1") (pin "AB2") (pinfunction "VSS_AB2") (pintype "passive"))
      (node (ref "U1") (pin "AB20") (pinfunction "VSS_AB20") (pintype "passive"))
      (node (ref "U1") (pin "AB22") (pinfunction "VSS_AB22") (pintype "passive"))
      (node (ref "U1") (pin "AB23") (pinfunction "VSS_AB23") (pintype "passive"))
      (node (ref "U1") (pin "AB25") (pinfunction "VSS_AB25") (pintype "passive"))
      (node (ref "U1") (pin "AB27") (pinfunction "VSS_AB27") (pintype "passive"))
      (node (ref "U1") (pin "AB29") (pinfunction "VSS_AB29") (pintype "passive"))
      (node (ref "U1") (pin "AB31") (pinfunction "VSS_AB31") (pintype "passive"))
      (node (ref "U1") (pin "AB33") (pinfunction "VSS_AB33") (pintype "passive"))
      (node (ref "U1") (pin "AB35") (pinfunction "VSS_AB35") (pintype "passive"))
      (node (ref "U1") (pin "AB37") (pinfunction "VSS_AB37") (pintype "passive"))
      (node (ref "U1") (pin "AB39") (pinfunction "VSS_AB39") (pintype "passive"))
      (node (ref "U1") (pin "AB4") (pinfunction "VSS_AB4") (pintype "passive"))
      (node (ref "U1") (pin "AB41") (pinfunction "VSS_AB41") (pintype "passive"))
      (node (ref "U1") (pin "AB43") (pinfunction "VSS_AB43") (pintype "passive"))
      (node (ref "U1") (pin "AB6") (pinfunction "VSS_AB6") (pintype "passive"))
      (node (ref "U1") (pin "AB8") (pinfunction "VSS_AB8") (pintype "passive"))
      (node (ref "U1") (pin "AC10") (pinfunction "VSS_AC10") (pintype "passive"))
      (node (ref "U1") (pin "AC12") (pinfunction "VSS_AC12") (pintype "passive"))
      (node (ref "U1") (pin "AC14") (pinfunction "VSS_AC14") (pintype "passive"))
      (node (ref "U1") (pin "AC16") (pinfunction "VSS_AC16") (pintype "passive"))
      (node (ref "U1") (pin "AC18") (pinfunction "VSS_AC18") (pintype "passive"))
      (node (ref "U1") (pin "AC2") (pinfunction "VSS_AC2") (pintype "passive"))
      (node (ref "U1") (pin "AC20") (pinfunction "VSS_AC20") (pintype "passive"))
      (node (ref "U1") (pin "AC22") (pinfunction "VSS_AC22") (pintype "passive"))
      (node (ref "U1") (pin "AC23") (pinfunction "VSS_AC23") (pintype "passive"))
      (node (ref "U1") (pin "AC25") (pinfunction "VSS_AC25") (pintype "passive"))
      (node (ref "U1") (pin "AC27") (pinfunction "VSS_AC27") (pintype "passive"))
      (node (ref "U1") (pin "AC29") (pinfunction "VSS_AC29") (pintype "passive"))
      (node (ref "U1") (pin "AC31") (pinfunction "VSS_AC31") (pintype "passive"))
      (node (ref "U1") (pin "AC33") (pinfunction "VSS_AC33") (pintype "passive"))
      (node (ref "U1") (pin "AC35") (pinfunction "VSS_AC35") (pintype "passive"))
      (node (ref "U1") (pin "AC37") (pinfunction "VSS_AC37") (pintype "passive"))
      (node (ref "U1") (pin "AC39") (pinfunction "VSS_AC39") (pintype "passive"))
      (node (ref "U1") (pin "AC4") (pinfunction "VSS_AC4") (pintype "passive"))
      (node (ref "U1") (pin "AC41") (pinfunction "VSS_AC41") (pintype "passive"))
      (node (ref "U1") (pin "AC43") (pinfunction "VSS_AC43") (pintype "passive"))
      (node (ref "U1") (pin "AC6") (pinfunction "VSS_AC6") (pintype "passive"))
      (node (ref "U1") (pin "AC8") (pinfunction "VSS_AC8") (pintype "passive"))
      (node (ref "U1") (pin "AD1") (pinfunction "VSS_AD1") (pintype "passive"))
      (node (ref "U1") (pin "AD11") (pinfunction "VSS_AD11") (pintype "passive"))
      (node (ref "U1") (pin "AD13") (pinfunction "VSS_AD13") (pintype "passive"))
      (node (ref "U1") (pin "AD15") (pinfunction "VSS_AD15") (pintype "passive"))
      (node (ref "U1") (pin "AD17") (pinfunction "VSS_AD17") (pintype "passive"))
      (node (ref "U1") (pin "AD19") (pinfunction "VSS_AD19") (pintype "passive"))
      (node (ref "U1") (pin "AD21") (pinfunction "VSS_AD21") (pintype "passive"))
      (node (ref "U1") (pin "AD24") (pinfunction "VSS_AD24") (pintype "passive"))
      (node (ref "U1") (pin "AD26") (pinfunction "VSS_AD26") (pintype "passive"))
      (node (ref "U1") (pin "AD28") (pinfunction "VSS_AD28") (pintype "passive"))
      (node (ref "U1") (pin "AD3") (pinfunction "VSS_AD3") (pintype "passive"))
      (node (ref "U1") (pin "AD30") (pinfunction "VSS_AD30") (pintype "passive"))
      (node (ref "U1") (pin "AD32") (pinfunction "VSS_AD32") (pintype "passive"))
      (node (ref "U1") (pin "AD34") (pinfunction "VSS_AD34") (pintype "passive"))
      (node (ref "U1") (pin "AD36") (pinfunction "VSS_AD36") (pintype "passive"))
      (node (ref "U1") (pin "AD38") (pinfunction "VSS_AD38") (pintype "passive"))
      (node (ref "U1") (pin "AD40") (pinfunction "VSS_AD40") (pintype "passive"))
      (node (ref "U1") (pin "AD42") (pinfunction "VSS_AD42") (pintype "passive"))
      (node (ref "U1") (pin "AD44") (pinfunction "VSS_AD44") (pintype "passive"))
      (node (ref "U1") (pin "AD5") (pinfunction "VSS_AD5") (pintype "passive"))
      (node (ref "U1") (pin "AD7") (pinfunction "VSS_AD7") (pintype "passive"))
      (node (ref "U1") (pin "AD9") (pinfunction "VSS_AD9") (pintype "passive"))
      (node (ref "U1") (pin "AE10") (pinfunction "VSS_AE10") (pintype "passive"))
      (node (ref "U1") (pin "AE12") (pinfunction "VSS_AE12") (pintype "passive"))
      (node (ref "U1") (pin "AE14") (pinfunction "VSS_AE14") (pintype "passive"))
      (node (ref "U1") (pin "AE16") (pinfunction "VSS_AE16") (pintype "passive"))
      (node (ref "U1") (pin "AE18") (pinfunction "VSS_AE18") (pintype "passive"))
      (node (ref "U1") (pin "AE2") (pinfunction "VSS_AE2") (pintype "passive"))
      (node (ref "U1") (pin "AE20") (pinfunction "VSS_AE20") (pintype "passive"))
      (node (ref "U1") (pin "AE22") (pinfunction "VSS_AE22") (pintype "passive"))
      (node (ref "U1") (pin "AE23") (pinfunction "VSS_AE23") (pintype "passive"))
      (node (ref "U1") (pin "AE25") (pinfunction "VSS_AE25") (pintype "passive"))
      (node (ref "U1") (pin "AE27") (pinfunction "VSS_AE27") (pintype "passive"))
      (node (ref "U1") (pin "AE29") (pinfunction "VSS_AE29") (pintype "passive"))
      (node (ref "U1") (pin "AE31") (pinfunction "VSS_AE31") (pintype "passive"))
      (node (ref "U1") (pin "AE33") (pinfunction "VSS_AE33") (pintype "passive"))
      (node (ref "U1") (pin "AE35") (pinfunction "VSS_AE35") (pintype "passive"))
      (node (ref "U1") (pin "AE37") (pinfunction "VSS_AE37") (pintype "passive"))
      (node (ref "U1") (pin "AE39") (pinfunction "VSS_AE39") (pintype "passive"))
      (node (ref "U1") (pin "AE4") (pinfunction "VSS_AE4") (pintype "passive"))
      (node (ref "U1") (pin "AE41") (pinfunction "VSS_AE41") (pintype "passive"))
      (node (ref "U1") (pin "AE43") (pinfunction "VSS_AE43") (pintype "passive"))
      (node (ref "U1") (pin "AE6") (pinfunction "VSS_AE6") (pintype "passive"))
      (node (ref "U1") (pin "AE8") (pinfunction "VSS_AE8") (pintype "passive"))
      (node (ref "U1") (pin "AF1") (pinfunction "VSS_AF1") (pintype "passive"))
      (node (ref "U1") (pin "AF11") (pinfunction "VSS_AF11") (pintype "passive"))
      (node (ref "U1") (pin "AF13") (pinfunction "VSS_AF13") (pintype "passive"))
      (node (ref "U1") (pin "AF15") (pinfunction "VSS_AF15") (pintype "passive"))
      (node (ref "U1") (pin "AF17") (pinfunction "VSS_AF17") (pintype "passive"))
      (node (ref "U1") (pin "AF19") (pinfunction "VSS_AF19") (pintype "passive"))
      (node (ref "U1") (pin "AF21") (pinfunction "VSS_AF21") (pintype "passive"))
      (node (ref "U1") (pin "AF26") (pinfunction "VSS_AF26") (pintype "passive"))
      (node (ref "U1") (pin "AF28") (pinfunction "VSS_AF28") (pintype "passive"))
      (node (ref "U1") (pin "AF3") (pinfunction "VSS_AF3") (pintype "passive"))
      (node (ref "U1") (pin "AF30") (pinfunction "VSS_AF30") (pintype "passive"))
      (node (ref "U1") (pin "AF32") (pinfunction "VSS_AF32") (pintype "passive"))
      (node (ref "U1") (pin "AF34") (pinfunction "VSS_AF34") (pintype "passive"))
      (node (ref "U1") (pin "AF36") (pinfunction "VSS_AF36") (pintype "passive"))
      (node (ref "U1") (pin "AF38") (pinfunction "VSS_AF38") (pintype "passive"))
      (node (ref "U1") (pin "AF40") (pinfunction "VSS_AF40") (pintype "passive"))
      (node (ref "U1") (pin "AF42") (pinfunction "VSS_AF42") (pintype "passive"))
      (node (ref "U1") (pin "AF44") (pinfunction "VSS_AF44") (pintype "passive"))
      (node (ref "U1") (pin "AF5") (pinfunction "VSS_AF5") (pintype "passive"))
      (node (ref "U1") (pin "AF7") (pinfunction "VSS_AF7") (pintype "passive"))
      (node (ref "U1") (pin "AF9") (pinfunction "VSS_AF9") (pintype "passive"))
      (node (ref "U1") (pin "AG10") (pinfunction "VSS_AG10") (pintype "passive"))
      (node (ref "U1") (pin "AG12") (pinfunction "VSS_AG12") (pintype "passive"))
      (node (ref "U1") (pin "AG14") (pinfunction "VSS_AG14") (pintype "passive"))
      (node (ref "U1") (pin "AG16") (pinfunction "VSS_AG16") (pintype "passive"))
      (node (ref "U1") (pin "AG18") (pinfunction "VSS_AG18") (pintype "passive"))
      (node (ref "U1") (pin "AG2") (pinfunction "VSS_AG2") (pintype "passive"))
      (node (ref "U1") (pin "AG20") (pinfunction "VSS_AG20") (pintype "passive"))
      (node (ref "U1") (pin "AG22") (pinfunction "VSS_AG22") (pintype "passive"))
      (node (ref "U1") (pin "AG23") (pinfunction "VSS_AG23") (pintype "passive"))
      (node (ref "U1") (pin "AG25") (pinfunction "VSS_AG25") (pintype "passive"))
      (node (ref "U1") (pin "AG27") (pinfunction "VSS_AG27") (pintype "passive"))
      (node (ref "U1") (pin "AG29") (pinfunction "VSS_AG29") (pintype "passive"))
      (node (ref "U1") (pin "AG31") (pinfunction "VSS_AG31") (pintype "passive"))
      (node (ref "U1") (pin "AG33") (pinfunction "VSS_AG33") (pintype "passive"))
      (node (ref "U1") (pin "AG35") (pinfunction "VSS_AG35") (pintype "passive"))
      (node (ref "U1") (pin "AG4") (pinfunction "VSS_AG4") (pintype "passive"))
      (node (ref "U1") (pin "AG41") (pinfunction "VSS_AG41") (pintype "passive"))
      (node (ref "U1") (pin "AG43") (pinfunction "VSS_AG43") (pintype "passive"))
      (node (ref "U1") (pin "AG6") (pinfunction "VSS_AG6") (pintype "passive"))
      (node (ref "U1") (pin "AG8") (pinfunction "VSS_AG8") (pintype "passive"))
      (node (ref "U1") (pin "AH1") (pinfunction "VSS_AH1") (pintype "passive"))
      (node (ref "U1") (pin "AH11") (pinfunction "VSS_AH11") (pintype "passive"))
      (node (ref "U1") (pin "AH13") (pinfunction "VSS_AH13") (pintype "passive"))
      (node (ref "U1") (pin "AH15") (pinfunction "VSS_AH15") (pintype "passive"))
      (node (ref "U1") (pin "AH17") (pinfunction "VSS_AH17") (pintype "passive"))
      (node (ref "U1") (pin "AH19") (pinfunction "VSS_AH19") (pintype "passive"))
      (node (ref "U1") (pin "AH21") (pinfunction "VSS_AH21") (pintype "passive"))
      (node (ref "U1") (pin "AH24") (pinfunction "VSS_AH24") (pintype "passive"))
      (node (ref "U1") (pin "AH26") (pinfunction "VSS_AH26") (pintype "passive"))
      (node (ref "U1") (pin "AH28") (pinfunction "VSS_AH28") (pintype "passive"))
      (node (ref "U1") (pin "AH3") (pinfunction "VSS_AH3") (pintype "passive"))
      (node (ref "U1") (pin "AH30") (pinfunction "VSS_AH30") (pintype "passive"))
      (node (ref "U1") (pin "AH32") (pinfunction "VSS_AH32") (pintype "passive"))
      (node (ref "U1") (pin "AH34") (pinfunction "VSS_AH34") (pintype "passive"))
      (node (ref "U1") (pin "AH36") (pinfunction "VSS_AH36") (pintype "passive"))
      (node (ref "U1") (pin "AH38") (pinfunction "VSS_AH38") (pintype "passive"))
      (node (ref "U1") (pin "AH40") (pinfunction "VSS_AH40") (pintype "passive"))
      (node (ref "U1") (pin "AH42") (pinfunction "VSS_AH42") (pintype "passive"))
      (node (ref "U1") (pin "AH5") (pinfunction "VSS_AH5") (pintype "passive"))
      (node (ref "U1") (pin "AH7") (pinfunction "VSS_AH7") (pintype "passive"))
      (node (ref "U1") (pin "AH9") (pinfunction "VSS_AH9") (pintype "passive"))
      (node (ref "U1") (pin "AJ10") (pinfunction "VSS_AJ10") (pintype "passive"))
      (node (ref "U1") (pin "AJ12") (pinfunction "VSS_AJ12") (pintype "passive"))
      (node (ref "U1") (pin "AJ14") (pinfunction "VSS_AJ14") (pintype "passive"))
      (node (ref "U1") (pin "AJ16") (pinfunction "VSS_AJ16") (pintype "passive"))
      (node (ref "U1") (pin "AJ18") (pinfunction "VSS_AJ18") (pintype "passive"))
      (node (ref "U1") (pin "AJ2") (pinfunction "VSS_AJ2") (pintype "passive"))
      (node (ref "U1") (pin "AJ20") (pinfunction "VSS_AJ20") (pintype "passive"))
      (node (ref "U1") (pin "AJ22") (pinfunction "VSS_AJ22") (pintype "passive"))
      (node (ref "U1") (pin "AJ23") (pinfunction "VSS_AJ23") (pintype "passive"))
      (node (ref "U1") (pin "AJ25") (pinfunction "VSS_AJ25") (pintype "passive"))
      (node (ref "U1") (pin "AJ27") (pinfunction "VSS_AJ27") (pintype "passive"))
      (node (ref "U1") (pin "AJ29") (pinfunction "VSS_AJ29") (pintype "passive"))
      (node (ref "U1") (pin "AJ31") (pinfunction "VSS_AJ31") (pintype "passive"))
      (node (ref "U1") (pin "AJ33") (pinfunction "VSS_AJ33") (pintype "passive"))
      (node (ref "U1") (pin "AJ35") (pinfunction "VSS_AJ35") (pintype "passive"))
      (node (ref "U1") (pin "AJ37") (pinfunction "VSS_AJ37") (pintype "passive"))
      (node (ref "U1") (pin "AJ39") (pinfunction "VSS_AJ39") (pintype "passive"))
      (node (ref "U1") (pin "AJ4") (pinfunction "VSS_AJ4") (pintype "passive"))
      (node (ref "U1") (pin "AJ41") (pinfunction "VSS_AJ41") (pintype "passive"))
      (node (ref "U1") (pin "AJ43") (pinfunction "VSS_AJ43") (pintype "passive"))
      (node (ref "U1") (pin "AJ6") (pinfunction "VSS_AJ6") (pintype "passive"))
      (node (ref "U1") (pin "AJ8") (pinfunction "VSS_AJ8") (pintype "passive"))
      (node (ref "U1") (pin "AK1") (pinfunction "VSS_AK1") (pintype "passive"))
      (node (ref "U1") (pin "AK11") (pinfunction "VSS_AK11") (pintype "passive"))
      (node (ref "U1") (pin "AK13") (pinfunction "VSS_AK13") (pintype "passive"))
      (node (ref "U1") (pin "AK15") (pinfunction "VSS_AK15") (pintype "passive"))
      (node (ref "U1") (pin "AK17") (pinfunction "VSS_AK17") (pintype "passive"))
      (node (ref "U1") (pin "AK19") (pinfunction "VSS_AK19") (pintype "passive"))
      (node (ref "U1") (pin "AK21") (pinfunction "VSS_AK21") (pintype "passive"))
      (node (ref "U1") (pin "AK24") (pinfunction "VSS_AK24") (pintype "passive"))
      (node (ref "U1") (pin "AK26") (pinfunction "VSS_AK26") (pintype "passive"))
      (node (ref "U1") (pin "AK28") (pinfunction "VSS_AK28") (pintype "passive"))
      (node (ref "U1") (pin "AK3") (pinfunction "VSS_AK3") (pintype "passive"))
      (node (ref "U1") (pin "AK30") (pinfunction "VSS_AK30") (pintype "passive"))
      (node (ref "U1") (pin "AK32") (pinfunction "VSS_AK32") (pintype "passive"))
      (node (ref "U1") (pin "AK34") (pinfunction "VSS_AK34") (pintype "passive"))
      (node (ref "U1") (pin "AK36") (pinfunction "VSS_AK36") (pintype "passive"))
      (node (ref "U1") (pin "AK38") (pinfunction "VSS_AK38") (pintype "passive"))
      (node (ref "U1") (pin "AK40") (pinfunction "VSS_AK40") (pintype "passive"))
      (node (ref "U1") (pin "AK42") (pinfunction "VSS_AK42") (pintype "passive"))
      (node (ref "U1") (pin "AK44") (pinfunction "VSS_AK44") (pintype "passive"))
      (node (ref "U1") (pin "AK5") (pinfunction "VSS_AK5") (pintype "passive"))
      (node (ref "U1") (pin "AK7") (pinfunction "VSS_AK7") (pintype "passive"))
      (node (ref "U1") (pin "AK9") (pinfunction "VSS_AK9") (pintype "passive"))
      (node (ref "U1") (pin "AL10") (pinfunction "VSS_AL10") (pintype "passive"))
      (node (ref "U1") (pin "AL12") (pinfunction "VSS_AL12") (pintype "passive"))
      (node (ref "U1") (pin "AL14") (pinfunction "VSS_AL14") (pintype "passive"))
      (node (ref "U1") (pin "AL16") (pinfunction "VSS_AL16") (pintype "passive"))
      (node (ref "U1") (pin "AL18") (pinfunction "VSS_AL18") (pintype "passive"))
      (node (ref "U1") (pin "AL2") (pinfunction "VSS_AL2") (pintype "passive"))
      (node (ref "U1") (pin "AL20") (pinfunction "VSS_AL20") (pintype "passive"))
      (node (ref "U1") (pin "AL22") (pinfunction "VSS_AL22") (pintype "passive"))
      (node (ref "U1") (pin "AL23") (pinfunction "VSS_AL23") (pintype "passive"))
      (node (ref "U1") (pin "AL25") (pinfunction "VSS_AL25") (pintype "passive"))
      (node (ref "U1") (pin "AL27") (pinfunction "VSS_AL27") (pintype "passive"))
      (node (ref "U1") (pin "AL29") (pinfunction "VSS_AL29") (pintype "passive"))
      (node (ref "U1") (pin "AL31") (pinfunction "VSS_AL31") (pintype "passive"))
      (node (ref "U1") (pin "AL33") (pinfunction "VSS_AL33") (pintype "passive"))
      (node (ref "U1") (pin "AL35") (pinfunction "VSS_AL35") (pintype "passive"))
      (node (ref "U1") (pin "AL37") (pinfunction "VSS_AL37") (pintype "passive"))
      (node (ref "U1") (pin "AL39") (pinfunction "VSS_AL39") (pintype "passive"))
      (node (ref "U1") (pin "AL4") (pinfunction "VSS_AL4") (pintype "passive"))
      (node (ref "U1") (pin "AL41") (pinfunction "VSS_AL41") (pintype "passive"))
      (node (ref "U1") (pin "AL43") (pinfunction "VSS_AL43") (pintype "passive"))
      (node (ref "U1") (pin "AL6") (pinfunction "VSS_AL6") (pintype "passive"))
      (node (ref "U1") (pin "AL8") (pinfunction "VSS_AL8") (pintype "passive"))
      (node (ref "U1") (pin "AM1") (pinfunction "VSS_AM1") (pintype "passive"))
      (node (ref "U1") (pin "AM11") (pinfunction "VSS_AM11") (pintype "passive"))
      (node (ref "U1") (pin "AM13") (pinfunction "VSS_AM13") (pintype "passive"))
      (node (ref "U1") (pin "AM15") (pinfunction "VSS_AM15") (pintype "passive"))
      (node (ref "U1") (pin "AM17") (pinfunction "VSS_AM17") (pintype "passive"))
      (node (ref "U1") (pin "AM19") (pinfunction "VSS_AM19") (pintype "passive"))
      (node (ref "U1") (pin "AM21") (pinfunction "VSS_AM21") (pintype "passive"))
      (node (ref "U1") (pin "AM24") (pinfunction "VSS_AM24") (pintype "passive"))
      (node (ref "U1") (pin "AM26") (pinfunction "VSS_AM26") (pintype "passive"))
      (node (ref "U1") (pin "AM28") (pinfunction "VSS_AM28") (pintype "passive"))
      (node (ref "U1") (pin "AM3") (pinfunction "VSS_AM3") (pintype "passive"))
      (node (ref "U1") (pin "AM30") (pinfunction "VSS_AM30") (pintype "passive"))
      (node (ref "U1") (pin "AM32") (pinfunction "VSS_AM32") (pintype "passive"))
      (node (ref "U1") (pin "AM34") (pinfunction "VSS_AM34") (pintype "passive"))
      (node (ref "U1") (pin "AM36") (pinfunction "VSS_AM36") (pintype "passive"))
      (node (ref "U1") (pin "AM38") (pinfunction "VSS_AM38") (pintype "passive"))
      (node (ref "U1") (pin "AM40") (pinfunction "VSS_AM40") (pintype "passive"))
      (node (ref "U1") (pin "AM42") (pinfunction "VSS_AM42") (pintype "passive"))
      (node (ref "U1") (pin "AM44") (pinfunction "VSS_AM44") (pintype "passive"))
      (node (ref "U1") (pin "AM5") (pinfunction "VSS_AM5") (pintype "passive"))
      (node (ref "U1") (pin "AM7") (pinfunction "VSS_AM7") (pintype "passive"))
      (node (ref "U1") (pin "AM9") (pinfunction "VSS_AM9") (pintype "passive"))
      (node (ref "U1") (pin "AN10") (pinfunction "VSS_AN10") (pintype "passive"))
      (node (ref "U1") (pin "AN12") (pinfunction "VSS_AN12") (pintype "passive"))
      (node (ref "U1") (pin "AN14") (pinfunction "VSS_AN14") (pintype "passive"))
      (node (ref "U1") (pin "AN16") (pinfunction "VSS_AN16") (pintype "passive"))
      (node (ref "U1") (pin "AN18") (pinfunction "VSS_AN18") (pintype "passive"))
      (node (ref "U1") (pin "AN2") (pinfunction "VSS_AN2") (pintype "passive"))
      (node (ref "U1") (pin "AN20") (pinfunction "VSS_AN20") (pintype "passive"))
      (node (ref "U1") (pin "AN22") (pinfunction "VSS_AN22") (pintype "passive"))
      (node (ref "U1") (pin "AN23") (pinfunction "VSS_AN23") (pintype "passive"))
      (node (ref "U1") (pin "AN25") (pinfunction "VSS_AN25") (pintype "passive"))
      (node (ref "U1") (pin "AN27") (pinfunction "VSS_AN27") (pintype "passive"))
      (node (ref "U1") (pin "AN29") (pinfunction "VSS_AN29") (pintype "passive"))
      (node (ref "U1") (pin "AN31") (pinfunction "VSS_AN31") (pintype "passive"))
      (node (ref "U1") (pin "AN33") (pinfunction "VSS_AN33") (pintype "passive"))
      (node (ref "U1") (pin "AN35") (pinfunction "VSS_AN35") (pintype "passive"))
      (node (ref "U1") (pin "AN37") (pinfunction "VSS_AN37") (pintype "passive"))
      (node (ref "U1") (pin "AN39") (pinfunction "VSS_AN39") (pintype "passive"))
      (node (ref "U1") (pin "AN4") (pinfunction "VSS_AN4") (pintype "passive"))
      (node (ref "U1") (pin "AN41") (pinfunction "VSS_AN41") (pintype "passive"))
      (node (ref "U1") (pin "AN43") (pinfunction "VSS_AN43") (pintype "passive"))
      (node (ref "U1") (pin "AN6") (pinfunction "VSS_AN6") (pintype "passive"))
      (node (ref "U1") (pin "AN8") (pinfunction "VSS_AN8") (pintype "passive"))
      (node (ref "U1") (pin "AP1") (pinfunction "VSS_AP1") (pintype "passive"))
      (node (ref "U1") (pin "AP11") (pinfunction "VSS_AP11") (pintype "passive"))
      (node (ref "U1") (pin "AP13") (pinfunction "VSS_AP13") (pintype "passive"))
      (node (ref "U1") (pin "AP15") (pinfunction "VSS_AP15") (pintype "passive"))
      (node (ref "U1") (pin "AP17") (pinfunction "VSS_AP17") (pintype "passive"))
      (node (ref "U1") (pin "AP19") (pinfunction "VSS_AP19") (pintype "passive"))
      (node (ref "U1") (pin "AP21") (pinfunction "VSS_AP21") (pintype "passive"))
      (node (ref "U1") (pin "AP24") (pinfunction "VSS_AP24") (pintype "passive"))
      (node (ref "U1") (pin "AP26") (pinfunction "VSS_AP26") (pintype "passive"))
      (node (ref "U1") (pin "AP28") (pinfunction "VSS_AP28") (pintype "passive"))
      (node (ref "U1") (pin "AP3") (pinfunction "VSS_AP3") (pintype "passive"))
      (node (ref "U1") (pin "AP30") (pinfunction "VSS_AP30") (pintype "passive"))
      (node (ref "U1") (pin "AP32") (pinfunction "VSS_AP32") (pintype "passive"))
      (node (ref "U1") (pin "AP34") (pinfunction "VSS_AP34") (pintype "passive"))
      (node (ref "U1") (pin "AP36") (pinfunction "VSS_AP36") (pintype "passive"))
      (node (ref "U1") (pin "AP38") (pinfunction "VSS_AP38") (pintype "passive"))
      (node (ref "U1") (pin "AP40") (pinfunction "VSS_AP40") (pintype "passive"))
      (node (ref "U1") (pin "AP42") (pinfunction "VSS_AP42") (pintype "passive"))
      (node (ref "U1") (pin "AP44") (pinfunction "VSS_AP44") (pintype "passive"))
      (node (ref "U1") (pin "AP5") (pinfunction "VSS_AP5") (pintype "passive"))
      (node (ref "U1") (pin "AP7") (pinfunction "VSS_AP7") (pintype "passive"))
      (node (ref "U1") (pin "AP9") (pinfunction "VSS_AP9") (pintype "passive"))
      (node (ref "U1") (pin "AR10") (pinfunction "VSS_AR10") (pintype "passive"))
      (node (ref "U1") (pin "AR12") (pinfunction "VSS_AR12") (pintype "passive"))
      (node (ref "U1") (pin "AR14") (pinfunction "VSS_AR14") (pintype "passive"))
      (node (ref "U1") (pin "AR16") (pinfunction "VSS_AR16") (pintype "passive"))
      (node (ref "U1") (pin "AR18") (pinfunction "VSS_AR18") (pintype "passive"))
      (node (ref "U1") (pin "AR2") (pinfunction "VSS_AR2") (pintype "passive"))
      (node (ref "U1") (pin "AR20") (pinfunction "VSS_AR20") (pintype "passive"))
      (node (ref "U1") (pin "AR22") (pinfunction "VSS_AR22") (pintype "passive"))
      (node (ref "U1") (pin "AR23") (pinfunction "VSS_AR23") (pintype "passive"))
      (node (ref "U1") (pin "AR25") (pinfunction "VSS_AR25") (pintype "passive"))
      (node (ref "U1") (pin "AR27") (pinfunction "VSS_AR27") (pintype "passive"))
      (node (ref "U1") (pin "AR29") (pinfunction "VSS_AR29") (pintype "passive"))
      (node (ref "U1") (pin "AR31") (pinfunction "VSS_AR31") (pintype "passive"))
      (node (ref "U1") (pin "AR33") (pinfunction "VSS_AR33") (pintype "passive"))
      (node (ref "U1") (pin "AR35") (pinfunction "VSS_AR35") (pintype "passive"))
      (node (ref "U1") (pin "AR37") (pinfunction "VSS_AR37") (pintype "passive"))
      (node (ref "U1") (pin "AR39") (pinfunction "VSS_AR39") (pintype "passive"))
      (node (ref "U1") (pin "AR4") (pinfunction "VSS_AR4") (pintype "passive"))
      (node (ref "U1") (pin "AR41") (pinfunction "VSS_AR41") (pintype "passive"))
      (node (ref "U1") (pin "AR43") (pinfunction "VSS_AR43") (pintype "passive"))
      (node (ref "U1") (pin "AR6") (pinfunction "VSS_AR6") (pintype "passive"))
      (node (ref "U1") (pin "AR8") (pinfunction "VSS_AR8") (pintype "passive"))
      (node (ref "U1") (pin "AT1") (pinfunction "VSS_AT1") (pintype "passive"))
      (node (ref "U1") (pin "AT11") (pinfunction "VSS_AT11") (pintype "passive"))
      (node (ref "U1") (pin "AT13") (pinfunction "VSS_AT13") (pintype "passive"))
      (node (ref "U1") (pin "AT15") (pinfunction "VSS_AT15") (pintype "passive"))
      (node (ref "U1") (pin "AT17") (pinfunction "VSS_AT17") (pintype "passive"))
      (node (ref "U1") (pin "AT19") (pinfunction "VSS_AT19") (pintype "passive"))
      (node (ref "U1") (pin "AT21") (pinfunction "VSS_AT21") (pintype "passive"))
      (node (ref "U1") (pin "AT24") (pinfunction "VSS_AT24") (pintype "passive"))
      (node (ref "U1") (pin "AT26") (pinfunction "VSS_AT26") (pintype "passive"))
      (node (ref "U1") (pin "AT28") (pinfunction "VSS_AT28") (pintype "passive"))
      (node (ref "U1") (pin "AT3") (pinfunction "VSS_AT3") (pintype "passive"))
      (node (ref "U1") (pin "AT30") (pinfunction "VSS_AT30") (pintype "passive"))
      (node (ref "U1") (pin "AT32") (pinfunction "VSS_AT32") (pintype "passive"))
      (node (ref "U1") (pin "AT34") (pinfunction "VSS_AT34") (pintype "passive"))
      (node (ref "U1") (pin "AT36") (pinfunction "VSS_AT36") (pintype "passive"))
      (node (ref "U1") (pin "AT38") (pinfunction "VSS_AT38") (pintype "passive"))
      (node (ref "U1") (pin "AT40") (pinfunction "VSS_AT40") (pintype "passive"))
      (node (ref "U1") (pin "AT42") (pinfunction "VSS_AT42") (pintype "passive"))
      (node (ref "U1") (pin "AT44") (pinfunction "VSS_AT44") (pintype "passive"))
      (node (ref "U1") (pin "AT5") (pinfunction "VSS_AT5") (pintype "passive"))
      (node (ref "U1") (pin "AT7") (pinfunction "VSS_AT7") (pintype "passive"))
      (node (ref "U1") (pin "AT9") (pinfunction "VSS_AT9") (pintype "passive"))
      (node (ref "U1") (pin "AU10") (pinfunction "VSS_AU10") (pintype "passive"))
      (node (ref "U1") (pin "AU12") (pinfunction "VSS_AU12") (pintype "passive"))
      (node (ref "U1") (pin "AU16") (pinfunction "VSS_AU16") (pintype "passive"))
      (node (ref "U1") (pin "AU18") (pinfunction "VSS_AU18") (pintype "passive"))
      (node (ref "U1") (pin "AU2") (pinfunction "VSS_AU2") (pintype "passive"))
      (node (ref "U1") (pin "AU20") (pinfunction "VSS_AU20") (pintype "passive"))
      (node (ref "U1") (pin "AU22") (pinfunction "VSS_AU22") (pintype "passive"))
      (node (ref "U1") (pin "AU23") (pinfunction "VSS_AU23") (pintype "passive"))
      (node (ref "U1") (pin "AU25") (pinfunction "VSS_AU25") (pintype "passive"))
      (node (ref "U1") (pin "AU27") (pinfunction "VSS_AU27") (pintype "passive"))
      (node (ref "U1") (pin "AU29") (pinfunction "VSS_AU29") (pintype "passive"))
      (node (ref "U1") (pin "AU31") (pinfunction "VSS_AU31") (pintype "passive"))
      (node (ref "U1") (pin "AU33") (pinfunction "VSS_AU33") (pintype "passive"))
      (node (ref "U1") (pin "AU35") (pinfunction "VSS_AU35") (pintype "passive"))
      (node (ref "U1") (pin "AU37") (pinfunction "VSS_AU37") (pintype "passive"))
      (node (ref "U1") (pin "AU39") (pinfunction "VSS_AU39") (pintype "passive"))
      (node (ref "U1") (pin "AU4") (pinfunction "VSS_AU4") (pintype "passive"))
      (node (ref "U1") (pin "AU41") (pinfunction "VSS_AU41") (pintype "passive"))
      (node (ref "U1") (pin "AU43") (pinfunction "VSS_AU43") (pintype "passive"))
      (node (ref "U1") (pin "AU6") (pinfunction "VSS_AU6") (pintype "passive"))
      (node (ref "U1") (pin "AU8") (pinfunction "VSS_AU8") (pintype "passive"))
      (node (ref "U1") (pin "AV1") (pinfunction "VSS_AV1") (pintype "passive"))
      (node (ref "U1") (pin "AV11") (pinfunction "VSS_AV11") (pintype "passive"))
      (node (ref "U1") (pin "AV13") (pinfunction "VSS_AV13") (pintype "passive"))
      (node (ref "U1") (pin "AV15") (pinfunction "VSS_AV15") (pintype "passive"))
      (node (ref "U1") (pin "AV17") (pinfunction "VSS_AV17") (pintype "passive"))
      (node (ref "U1") (pin "AV19") (pinfunction "VSS_AV19") (pintype "passive"))
      (node (ref "U1") (pin "AV21") (pinfunction "VSS_AV21") (pintype "passive"))
      (node (ref "U1") (pin "AV24") (pinfunction "VSS_AV24") (pintype "passive"))
      (node (ref "U1") (pin "AV26") (pinfunction "VSS_AV26") (pintype "passive"))
      (node (ref "U1") (pin "AV28") (pinfunction "VSS_AV28") (pintype "passive"))
      (node (ref "U1") (pin "AV3") (pinfunction "VSS_AV3") (pintype "passive"))
      (node (ref "U1") (pin "AV30") (pinfunction "VSS_AV30") (pintype "passive"))
      (node (ref "U1") (pin "AV32") (pinfunction "VSS_AV32") (pintype "passive"))
      (node (ref "U1") (pin "AV34") (pinfunction "VSS_AV34") (pintype "passive"))
      (node (ref "U1") (pin "AV36") (pinfunction "VSS_AV36") (pintype "passive"))
      (node (ref "U1") (pin "AV38") (pinfunction "VSS_AV38") (pintype "passive"))
      (node (ref "U1") (pin "AV40") (pinfunction "VSS_AV40") (pintype "passive"))
      (node (ref "U1") (pin "AV42") (pinfunction "VSS_AV42") (pintype "passive"))
      (node (ref "U1") (pin "AV44") (pinfunction "VSS_AV44") (pintype "passive"))
      (node (ref "U1") (pin "AV5") (pinfunction "VSS_AV5") (pintype "passive"))
      (node (ref "U1") (pin "AW10") (pinfunction "VSS_AW10") (pintype "passive"))
      (node (ref "U1") (pin "AW12") (pinfunction "VSS_AW12") (pintype "passive"))
      (node (ref "U1") (pin "AW14") (pinfunction "VSS_AW14") (pintype "passive"))
      (node (ref "U1") (pin "AW16") (pinfunction "VSS_AW16") (pintype "passive"))
      (node (ref "U1") (pin "AW18") (pinfunction "VSS_AW18") (pintype "passive"))
      (node (ref "U1") (pin "AW2") (pinfunction "VSS_AW2") (pintype "passive"))
      (node (ref "U1") (pin "AW20") (pinfunction "VSS_AW20") (pintype "passive"))
      (node (ref "U1") (pin "AW22") (pinfunction "VSS_AW22") (pintype "passive"))
      (node (ref "U1") (pin "AW23") (pinfunction "VSS_AW23") (pintype "passive"))
      (node (ref "U1") (pin "AW25") (pinfunction "VSS_AW25") (pintype "passive"))
      (node (ref "U1") (pin "AW27") (pinfunction "VSS_AW27") (pintype "passive"))
      (node (ref "U1") (pin "AW29") (pinfunction "VSS_AW29") (pintype "passive"))
      (node (ref "U1") (pin "AW31") (pinfunction "VSS_AW31") (pintype "passive"))
      (node (ref "U1") (pin "AW33") (pinfunction "VSS_AW33") (pintype "passive"))
      (node (ref "U1") (pin "AW35") (pinfunction "VSS_AW35") (pintype "passive"))
      (node (ref "U1") (pin "AW37") (pinfunction "VSS_AW37") (pintype "passive"))
      (node (ref "U1") (pin "AW39") (pinfunction "VSS_AW39") (pintype "passive"))
      (node (ref "U1") (pin "AW4") (pinfunction "VSS_AW4") (pintype "passive"))
      (node (ref "U1") (pin "AW41") (pinfunction "VSS_AW41") (pintype "passive"))
      (node (ref "U1") (pin "AW43") (pinfunction "VSS_AW43") (pintype "passive"))
      (node (ref "U1") (pin "AW6") (pinfunction "VSS_AW6") (pintype "passive"))
      (node (ref "U1") (pin "AW8") (pinfunction "VSS_AW8") (pintype "passive"))
      (node (ref "U1") (pin "AY1") (pinfunction "VSS_AY1") (pintype "passive"))
      (node (ref "U1") (pin "AY11") (pinfunction "VSS_AY11") (pintype "passive"))
      (node (ref "U1") (pin "AY13") (pinfunction "VSS_AY13") (pintype "passive"))
      (node (ref "U1") (pin "AY15") (pinfunction "VSS_AY15") (pintype "passive"))
      (node (ref "U1") (pin "AY19") (pinfunction "VSS_AY19") (pintype "passive"))
      (node (ref "U1") (pin "AY21") (pinfunction "VSS_AY21") (pintype "passive"))
      (node (ref "U1") (pin "AY24") (pinfunction "VSS_AY24") (pintype "passive"))
      (node (ref "U1") (pin "AY26") (pinfunction "VSS_AY26") (pintype "passive"))
      (node (ref "U1") (pin "AY28") (pinfunction "VSS_AY28") (pintype "passive"))
      (node (ref "U1") (pin "AY3") (pinfunction "VSS_AY3") (pintype "passive"))
      (node (ref "U1") (pin "AY30") (pinfunction "VSS_AY30") (pintype "passive"))
      (node (ref "U1") (pin "AY32") (pinfunction "VSS_AY32") (pintype "passive"))
      (node (ref "U1") (pin "AY34") (pinfunction "VSS_AY34") (pintype "passive"))
      (node (ref "U1") (pin "AY36") (pinfunction "VSS_AY36") (pintype "passive"))
      (node (ref "U1") (pin "AY38") (pinfunction "VSS_AY38") (pintype "passive"))
      (node (ref "U1") (pin "AY40") (pinfunction "VSS_AY40") (pintype "passive"))
      (node (ref "U1") (pin "AY42") (pinfunction "VSS_AY42") (pintype "passive"))
      (node (ref "U1") (pin "AY44") (pinfunction "VSS_AY44") (pintype "passive"))
      (node (ref "U1") (pin "AY5") (pinfunction "VSS_AY5") (pintype "passive"))
      (node (ref "U1") (pin "AY7") (pinfunction "VSS_AY7") (pintype "passive"))
      (node (ref "U1") (pin "AY9") (pinfunction "VSS_AY9") (pintype "passive"))
      (node (ref "U1") (pin "B2") (pinfunction "VSS_B2") (pintype "passive"))
      (node (ref "U1") (pin "B22") (pinfunction "VSS_B22") (pintype "passive"))
      (node (ref "U1") (pin "B23") (pinfunction "VSS_B23") (pintype "passive"))
      (node (ref "U1") (pin "B37") (pinfunction "VSS_B37") (pintype "passive"))
      (node (ref "U1") (pin "B39") (pinfunction "VSS_B39") (pintype "passive"))
      (node (ref "U1") (pin "B4") (pinfunction "VSS_B4") (pintype "passive"))
      (node (ref "U1") (pin "B41") (pinfunction "VSS_B41") (pintype "passive"))
      (node (ref "U1") (pin "B43") (pinfunction "VSS_B43") (pintype "passive"))
      (node (ref "U1") (pin "B6") (pinfunction "VSS_B6") (pintype "passive"))
      (node (ref "U1") (pin "B8") (pinfunction "VSS_B8") (pintype "passive"))
      (node (ref "U1") (pin "BA10") (pinfunction "VSS_BA10") (pintype "passive"))
      (node (ref "U1") (pin "BA12") (pinfunction "VSS_BA12") (pintype "passive"))
      (node (ref "U1") (pin "BA14") (pinfunction "VSS_BA14") (pintype "passive"))
      (node (ref "U1") (pin "BA16") (pinfunction "VSS_BA16") (pintype "passive"))
      (node (ref "U1") (pin "BA18") (pinfunction "VSS_BA18") (pintype "passive"))
      (node (ref "U1") (pin "BA2") (pinfunction "VSS_BA2") (pintype "passive"))
      (node (ref "U1") (pin "BA20") (pinfunction "VSS_BA20") (pintype "passive"))
      (node (ref "U1") (pin "BA22") (pinfunction "VSS_BA22") (pintype "passive"))
      (node (ref "U1") (pin "BA23") (pinfunction "VSS_BA23") (pintype "passive"))
      (node (ref "U1") (pin "BA25") (pinfunction "VSS_BA25") (pintype "passive"))
      (node (ref "U1") (pin "BA27") (pinfunction "VSS_BA27") (pintype "passive"))
      (node (ref "U1") (pin "BA29") (pinfunction "VSS_BA29") (pintype "passive"))
      (node (ref "U1") (pin "BA31") (pinfunction "VSS_BA31") (pintype "passive"))
      (node (ref "U1") (pin "BA33") (pinfunction "VSS_BA33") (pintype "passive"))
      (node (ref "U1") (pin "BA35") (pinfunction "VSS_BA35") (pintype "passive"))
      (node (ref "U1") (pin "BA37") (pinfunction "VSS_BA37") (pintype "passive"))
      (node (ref "U1") (pin "BA39") (pinfunction "VSS_BA39") (pintype "passive"))
      (node (ref "U1") (pin "BA4") (pinfunction "VSS_BA4") (pintype "passive"))
      (node (ref "U1") (pin "BA41") (pinfunction "VSS_BA41") (pintype "passive"))
      (node (ref "U1") (pin "BA43") (pinfunction "VSS_BA43") (pintype "passive"))
      (node (ref "U1") (pin "BA6") (pinfunction "VSS_BA6") (pintype "passive"))
      (node (ref "U1") (pin "BA8") (pinfunction "VSS_BA8") (pintype "passive"))
      (node (ref "U1") (pin "BB1") (pinfunction "VSS_BB1") (pintype "passive"))
      (node (ref "U1") (pin "BB24") (pinfunction "VSS_BB24") (pintype "passive"))
      (node (ref "U1") (pin "BB3") (pinfunction "VSS_BB3") (pintype "passive"))
      (node (ref "U1") (pin "BB38") (pinfunction "VSS_BB38") (pintype "passive"))
      (node (ref "U1") (pin "BB40") (pinfunction "VSS_BB40") (pintype "passive"))
      (node (ref "U1") (pin "BB42") (pinfunction "VSS_BB42") (pintype "passive"))
      (node (ref "U1") (pin "BB44") (pinfunction "VSS_BB44") (pintype "passive"))
      (node (ref "U1") (pin "BB5") (pinfunction "VSS_BB5") (pintype "passive"))
      (node (ref "U1") (pin "BB7") (pinfunction "VSS_BB7") (pintype "passive"))
      (node (ref "U1") (pin "BC2") (pinfunction "VSS_BC2") (pintype "passive"))
      (node (ref "U1") (pin "BC22") (pinfunction "VSS_BC22") (pintype "passive"))
      (node (ref "U1") (pin "BC23") (pinfunction "VSS_BC23") (pintype "passive"))
      (node (ref "U1") (pin "BC37") (pinfunction "VSS_BC37") (pintype "passive"))
      (node (ref "U1") (pin "BC39") (pinfunction "VSS_BC39") (pintype "passive"))
      (node (ref "U1") (pin "BC4") (pinfunction "VSS_BC4") (pintype "passive"))
      (node (ref "U1") (pin "BC41") (pinfunction "VSS_BC41") (pintype "passive"))
      (node (ref "U1") (pin "BC43") (pinfunction "VSS_BC43") (pintype "passive"))
      (node (ref "U1") (pin "BC6") (pinfunction "VSS_BC6") (pintype "passive"))
      (node (ref "U1") (pin "BC8") (pinfunction "VSS_BC8") (pintype "passive"))
      (node (ref "U1") (pin "BD1") (pinfunction "VSS_BD1") (pintype "passive"))
      (node (ref "U1") (pin "BD3") (pinfunction "VSS_BD3") (pintype "passive"))
      (node (ref "U1") (pin "BD38") (pinfunction "VSS_BD38") (pintype "passive"))
      (node (ref "U1") (pin "BD40") (pinfunction "VSS_BD40") (pintype "passive"))
      (node (ref "U1") (pin "BD42") (pinfunction "VSS_BD42") (pintype "passive"))
      (node (ref "U1") (pin "BD44") (pinfunction "VSS_BD44") (pintype "passive"))
      (node (ref "U1") (pin "BD5") (pinfunction "VSS_BD5") (pintype "passive"))
      (node (ref "U1") (pin "BD7") (pinfunction "VSS_BD7") (pintype "passive"))
      (node (ref "U1") (pin "C1") (pinfunction "VSS_C1") (pintype "passive"))
      (node (ref "U1") (pin "C21") (pinfunction "VSS_C21") (pintype "passive"))
      (node (ref "U1") (pin "C3") (pinfunction "VSS_C3") (pintype "passive"))
      (node (ref "U1") (pin "C36") (pinfunction "VSS_C36") (pintype "passive"))
      (node (ref "U1") (pin "C38") (pinfunction "VSS_C38") (pintype "passive"))
      (node (ref "U1") (pin "C40") (pinfunction "VSS_C40") (pintype "passive"))
      (node (ref "U1") (pin "C42") (pinfunction "VSS_C42") (pintype "passive"))
      (node (ref "U1") (pin "C44") (pinfunction "VSS_C44") (pintype "passive"))
      (node (ref "U1") (pin "C5") (pinfunction "VSS_C5") (pintype "passive"))
      (node (ref "U1") (pin "C7") (pinfunction "VSS_C7") (pintype "passive"))
      (node (ref "U1") (pin "D10") (pinfunction "VSS_D10") (pintype "passive"))
      (node (ref "U1") (pin "D12") (pinfunction "VSS_D12") (pintype "passive"))
      (node (ref "U1") (pin "D14") (pinfunction "VSS_D14") (pintype "passive"))
      (node (ref "U1") (pin "D16") (pinfunction "VSS_D16") (pintype "passive"))
      (node (ref "U1") (pin "D18") (pinfunction "VSS_D18") (pintype "passive"))
      (node (ref "U1") (pin "D2") (pinfunction "VSS_D2") (pintype "passive"))
      (node (ref "U1") (pin "D20") (pinfunction "VSS_D20") (pintype "passive"))
      (node (ref "U1") (pin "D22") (pinfunction "VSS_D22") (pintype "passive"))
      (node (ref "U1") (pin "D23") (pinfunction "VSS_D23") (pintype "passive"))
      (node (ref "U1") (pin "D25") (pinfunction "VSS_D25") (pintype "passive"))
      (node (ref "U1") (pin "D27") (pinfunction "VSS_D27") (pintype "passive"))
      (node (ref "U1") (pin "D29") (pinfunction "VSS_D29") (pintype "passive"))
      (node (ref "U1") (pin "D31") (pinfunction "VSS_D31") (pintype "passive"))
      (node (ref "U1") (pin "D33") (pinfunction "VSS_D33") (pintype "passive"))
      (node (ref "U1") (pin "D35") (pinfunction "VSS_D35") (pintype "passive"))
      (node (ref "U1") (pin "D37") (pinfunction "VSS_D37") (pintype "passive"))
      (node (ref "U1") (pin "D39") (pinfunction "VSS_D39") (pintype "passive"))
      (node (ref "U1") (pin "D4") (pinfunction "VSS_D4") (pintype "passive"))
      (node (ref "U1") (pin "D41") (pinfunction "VSS_D41") (pintype "passive"))
      (node (ref "U1") (pin "D43") (pinfunction "VSS_D43") (pintype "passive"))
      (node (ref "U1") (pin "D6") (pinfunction "VSS_D6") (pintype "passive"))
      (node (ref "U1") (pin "D8") (pinfunction "VSS_D8") (pintype "passive"))
      (node (ref "U1") (pin "E1") (pinfunction "VSS_E1") (pintype "passive"))
      (node (ref "U1") (pin "E11") (pinfunction "VSS_E11") (pintype "passive"))
      (node (ref "U1") (pin "E13") (pinfunction "VSS_E13") (pintype "passive"))
      (node (ref "U1") (pin "E15") (pinfunction "VSS_E15") (pintype "passive"))
      (node (ref "U1") (pin "E17") (pinfunction "VSS_E17") (pintype "passive"))
      (node (ref "U1") (pin "E19") (pinfunction "VSS_E19") (pintype "passive"))
      (node (ref "U1") (pin "E21") (pinfunction "VSS_E21") (pintype "passive"))
      (node (ref "U1") (pin "E24") (pinfunction "VSS_E24") (pintype "passive"))
      (node (ref "U1") (pin "E26") (pinfunction "VSS_E26") (pintype "passive"))
      (node (ref "U1") (pin "E28") (pinfunction "VSS_E28") (pintype "passive"))
      (node (ref "U1") (pin "E3") (pinfunction "VSS_E3") (pintype "passive"))
      (node (ref "U1") (pin "E30") (pinfunction "VSS_E30") (pintype "passive"))
      (node (ref "U1") (pin "E32") (pinfunction "VSS_E32") (pintype "passive"))
      (node (ref "U1") (pin "E34") (pinfunction "VSS_E34") (pintype "passive"))
      (node (ref "U1") (pin "E36") (pinfunction "VSS_E36") (pintype "passive"))
      (node (ref "U1") (pin "E38") (pinfunction "VSS_E38") (pintype "passive"))
      (node (ref "U1") (pin "E40") (pinfunction "VSS_E40") (pintype "passive"))
      (node (ref "U1") (pin "E42") (pinfunction "VSS_E42") (pintype "passive"))
      (node (ref "U1") (pin "E44") (pinfunction "VSS_E44") (pintype "passive"))
      (node (ref "U1") (pin "E5") (pinfunction "VSS_E5") (pintype "passive"))
      (node (ref "U1") (pin "E7") (pinfunction "VSS_E7") (pintype "passive"))
      (node (ref "U1") (pin "E9") (pinfunction "VSS_E9") (pintype "passive"))
      (node (ref "U1") (pin "F10") (pinfunction "VSS_F10") (pintype "passive"))
      (node (ref "U1") (pin "F12") (pinfunction "VSS_F12") (pintype "passive"))
      (node (ref "U1") (pin "F14") (pinfunction "VSS_F14") (pintype "passive"))
      (node (ref "U1") (pin "F16") (pinfunction "VSS_F16") (pintype "passive"))
      (node (ref "U1") (pin "F18") (pinfunction "VSS_F18") (pintype "passive"))
      (node (ref "U1") (pin "F2") (pinfunction "VSS_F2") (pintype "passive"))
      (node (ref "U1") (pin "F20") (pinfunction "VSS_F20") (pintype "passive"))
      (node (ref "U1") (pin "F22") (pinfunction "VSS_F22") (pintype "passive"))
      (node (ref "U1") (pin "F23") (pinfunction "VSS_F23") (pintype "passive"))
      (node (ref "U1") (pin "F25") (pinfunction "VSS_F25") (pintype "passive"))
      (node (ref "U1") (pin "F27") (pinfunction "VSS_F27") (pintype "passive"))
      (node (ref "U1") (pin "F29") (pinfunction "VSS_F29") (pintype "passive"))
      (node (ref "U1") (pin "F31") (pinfunction "VSS_F31") (pintype "passive"))
      (node (ref "U1") (pin "F33") (pinfunction "VSS_F33") (pintype "passive"))
      (node (ref "U1") (pin "F35") (pinfunction "VSS_F35") (pintype "passive"))
      (node (ref "U1") (pin "F37") (pinfunction "VSS_F37") (pintype "passive"))
      (node (ref "U1") (pin "F39") (pinfunction "VSS_F39") (pintype "passive"))
      (node (ref "U1") (pin "F4") (pinfunction "VSS_F4") (pintype "passive"))
      (node (ref "U1") (pin "F41") (pinfunction "VSS_F41") (pintype "passive"))
      (node (ref "U1") (pin "F43") (pinfunction "VSS_F43") (pintype "passive"))
      (node (ref "U1") (pin "F6") (pinfunction "VSS_F6") (pintype "passive"))
      (node (ref "U1") (pin "F8") (pinfunction "VSS_F8") (pintype "passive"))
      (node (ref "U1") (pin "G1") (pinfunction "VSS_G1") (pintype "passive"))
      (node (ref "U1") (pin "G11") (pinfunction "VSS_G11") (pintype "passive"))
      (node (ref "U1") (pin "G13") (pinfunction "VSS_G13") (pintype "passive"))
      (node (ref "U1") (pin "G15") (pinfunction "VSS_G15") (pintype "passive"))
      (node (ref "U1") (pin "G17") (pinfunction "VSS_G17") (pintype "passive"))
      (node (ref "U1") (pin "G19") (pinfunction "VSS_G19") (pintype "passive"))
      (node (ref "U1") (pin "G21") (pinfunction "VSS_G21") (pintype "passive"))
      (node (ref "U1") (pin "G24") (pinfunction "VSS_G24") (pintype "passive"))
      (node (ref "U1") (pin "G26") (pinfunction "VSS_G26") (pintype "passive"))
      (node (ref "U1") (pin "G28") (pinfunction "VSS_G28") (pintype "passive"))
      (node (ref "U1") (pin "G3") (pinfunction "VSS_G3") (pintype "passive"))
      (node (ref "U1") (pin "G30") (pinfunction "VSS_G30") (pintype "passive"))
      (node (ref "U1") (pin "G32") (pinfunction "VSS_G32") (pintype "passive"))
      (node (ref "U1") (pin "G34") (pinfunction "VSS_G34") (pintype "passive"))
      (node (ref "U1") (pin "G36") (pinfunction "VSS_G36") (pintype "passive"))
      (node (ref "U1") (pin "G38") (pinfunction "VSS_G38") (pintype "passive"))
      (node (ref "U1") (pin "G40") (pinfunction "VSS_G40") (pintype "passive"))
      (node (ref "U1") (pin "G42") (pinfunction "VSS_G42") (pintype "passive"))
      (node (ref "U1") (pin "G44") (pinfunction "VSS_G44") (pintype "passive"))
      (node (ref "U1") (pin "G5") (pinfunction "VSS_G5") (pintype "passive"))
      (node (ref "U1") (pin "G7") (pinfunction "VSS_G7") (pintype "passive"))
      (node (ref "U1") (pin "G9") (pinfunction "VSS_G9") (pintype "passive"))
      (node (ref "U1") (pin "H10") (pinfunction "VSS_H10") (pintype "passive"))
      (node (ref "U1") (pin "H12") (pinfunction "VSS_H12") (pintype "passive"))
      (node (ref "U1") (pin "H14") (pinfunction "VSS_H14") (pintype "passive"))
      (node (ref "U1") (pin "H16") (pinfunction "VSS_H16") (pintype "passive"))
      (node (ref "U1") (pin "H18") (pinfunction "VSS_H18") (pintype "passive"))
      (node (ref "U1") (pin "H2") (pinfunction "VSS_H2") (pintype "passive"))
      (node (ref "U1") (pin "H20") (pinfunction "VSS_H20") (pintype "passive"))
      (node (ref "U1") (pin "H22") (pinfunction "VSS_H22") (pintype "passive"))
      (node (ref "U1") (pin "H23") (pinfunction "VSS_H23") (pintype "passive"))
      (node (ref "U1") (pin "H25") (pinfunction "VSS_H25") (pintype "passive"))
      (node (ref "U1") (pin "H27") (pinfunction "VSS_H27") (pintype "passive"))
      (node (ref "U1") (pin "H29") (pinfunction "VSS_H29") (pintype "passive"))
      (node (ref "U1") (pin "H31") (pinfunction "VSS_H31") (pintype "passive"))
      (node (ref "U1") (pin "H33") (pinfunction "VSS_H33") (pintype "passive"))
      (node (ref "U1") (pin "H35") (pinfunction "VSS_H35") (pintype "passive"))
      (node (ref "U1") (pin "H37") (pinfunction "VSS_H37") (pintype "passive"))
      (node (ref "U1") (pin "H39") (pinfunction "VSS_H39") (pintype "passive"))
      (node (ref "U1") (pin "H4") (pinfunction "VSS_H4") (pintype "passive"))
      (node (ref "U1") (pin "H41") (pinfunction "VSS_H41") (pintype "passive"))
      (node (ref "U1") (pin "H43") (pinfunction "VSS_H43") (pintype "passive"))
      (node (ref "U1") (pin "H6") (pinfunction "VSS_H6") (pintype "passive"))
      (node (ref "U1") (pin "H8") (pinfunction "VSS_H8") (pintype "passive"))
      (node (ref "U1") (pin "J1") (pinfunction "VSS_J1") (pintype "passive"))
      (node (ref "U1") (pin "J11") (pinfunction "VSS_J11") (pintype "passive"))
      (node (ref "U1") (pin "J13") (pinfunction "VSS_J13") (pintype "passive"))
      (node (ref "U1") (pin "J15") (pinfunction "VSS_J15") (pintype "passive"))
      (node (ref "U1") (pin "J17") (pinfunction "VSS_J17") (pintype "passive"))
      (node (ref "U1") (pin "J19") (pinfunction "VSS_J19") (pintype "passive"))
      (node (ref "U1") (pin "J21") (pinfunction "VSS_J21") (pintype "passive"))
      (node (ref "U1") (pin "J24") (pinfunction "VSS_J24") (pintype "passive"))
      (node (ref "U1") (pin "J26") (pinfunction "VSS_J26") (pintype "passive"))
      (node (ref "U1") (pin "J28") (pinfunction "VSS_J28") (pintype "passive"))
      (node (ref "U1") (pin "J3") (pinfunction "VSS_J3") (pintype "passive"))
      (node (ref "U1") (pin "J30") (pinfunction "VSS_J30") (pintype "passive"))
      (node (ref "U1") (pin "J32") (pinfunction "VSS_J32") (pintype "passive"))
      (node (ref "U1") (pin "J34") (pinfunction "VSS_J34") (pintype "passive"))
      (node (ref "U1") (pin "J36") (pinfunction "VSS_J36") (pintype "passive"))
      (node (ref "U1") (pin "J38") (pinfunction "VSS_J38") (pintype "passive"))
      (node (ref "U1") (pin "J40") (pinfunction "VSS_J40") (pintype "passive"))
      (node (ref "U1") (pin "J42") (pinfunction "VSS_J42") (pintype "passive"))
      (node (ref "U1") (pin "J44") (pinfunction "VSS_J44") (pintype "passive"))
      (node (ref "U1") (pin "J5") (pinfunction "VSS_J5") (pintype "passive"))
      (node (ref "U1") (pin "J7") (pinfunction "VSS_J7") (pintype "passive"))
      (node (ref "U1") (pin "J9") (pinfunction "VSS_J9") (pintype "passive"))
      (node (ref "U1") (pin "K10") (pinfunction "VSS_K10") (pintype "passive"))
      (node (ref "U1") (pin "K12") (pinfunction "VSS_K12") (pintype "passive"))
      (node (ref "U1") (pin "K14") (pinfunction "VSS_K14") (pintype "passive"))
      (node (ref "U1") (pin "K16") (pinfunction "VSS_K16") (pintype "passive"))
      (node (ref "U1") (pin "K18") (pinfunction "VSS_K18") (pintype "passive"))
      (node (ref "U1") (pin "K2") (pinfunction "VSS_K2") (pintype "passive"))
      (node (ref "U1") (pin "K20") (pinfunction "VSS_K20") (pintype "passive"))
      (node (ref "U1") (pin "K22") (pinfunction "VSS_K22") (pintype "passive"))
      (node (ref "U1") (pin "K23") (pinfunction "VSS_K23") (pintype "passive"))
      (node (ref "U1") (pin "K25") (pinfunction "VSS_K25") (pintype "passive"))
      (node (ref "U1") (pin "K27") (pinfunction "VSS_K27") (pintype "passive"))
      (node (ref "U1") (pin "K29") (pinfunction "VSS_K29") (pintype "passive"))
      (node (ref "U1") (pin "K31") (pinfunction "VSS_K31") (pintype "passive"))
      (node (ref "U1") (pin "K33") (pinfunction "VSS_K33") (pintype "passive"))
      (node (ref "U1") (pin "K35") (pinfunction "VSS_K35") (pintype "passive"))
      (node (ref "U1") (pin "K37") (pinfunction "VSS_K37") (pintype "passive"))
      (node (ref "U1") (pin "K39") (pinfunction "VSS_K39") (pintype "passive"))
      (node (ref "U1") (pin "K4") (pinfunction "VSS_K4") (pintype "passive"))
      (node (ref "U1") (pin "K41") (pinfunction "VSS_K41") (pintype "passive"))
      (node (ref "U1") (pin "K43") (pinfunction "VSS_K43") (pintype "passive"))
      (node (ref "U1") (pin "K6") (pinfunction "VSS_K6") (pintype "passive"))
      (node (ref "U1") (pin "K8") (pinfunction "VSS_K8") (pintype "passive"))
      (node (ref "U1") (pin "L1") (pinfunction "VSS_L1") (pintype "passive"))
      (node (ref "U1") (pin "L11") (pinfunction "VSS_L11") (pintype "passive"))
      (node (ref "U1") (pin "L13") (pinfunction "VSS_L13") (pintype "passive"))
      (node (ref "U1") (pin "L15") (pinfunction "VSS_L15") (pintype "passive"))
      (node (ref "U1") (pin "L17") (pinfunction "VSS_L17") (pintype "passive"))
      (node (ref "U1") (pin "L19") (pinfunction "VSS_L19") (pintype "passive"))
      (node (ref "U1") (pin "L21") (pinfunction "VSS_L21") (pintype "passive"))
      (node (ref "U1") (pin "L24") (pinfunction "VSS_L24") (pintype "passive"))
      (node (ref "U1") (pin "L26") (pinfunction "VSS_L26") (pintype "passive"))
      (node (ref "U1") (pin "L28") (pinfunction "VSS_L28") (pintype "passive"))
      (node (ref "U1") (pin "L3") (pinfunction "VSS_L3") (pintype "passive"))
      (node (ref "U1") (pin "L30") (pinfunction "VSS_L30") (pintype "passive"))
      (node (ref "U1") (pin "L32") (pinfunction "VSS_L32") (pintype "passive"))
      (node (ref "U1") (pin "L34") (pinfunction "VSS_L34") (pintype "passive"))
      (node (ref "U1") (pin "L36") (pinfunction "VSS_L36") (pintype "passive"))
      (node (ref "U1") (pin "L38") (pinfunction "VSS_L38") (pintype "passive"))
      (node (ref "U1") (pin "L40") (pinfunction "VSS_L40") (pintype "passive"))
      (node (ref "U1") (pin "L42") (pinfunction "VSS_L42") (pintype "passive"))
      (node (ref "U1") (pin "L44") (pinfunction "VSS_L44") (pintype "passive"))
      (node (ref "U1") (pin "L5") (pinfunction "VSS_L5") (pintype "passive"))
      (node (ref "U1") (pin "L7") (pinfunction "VSS_L7") (pintype "passive"))
      (node (ref "U1") (pin "L9") (pinfunction "VSS_L9") (pintype "passive"))
      (node (ref "U1") (pin "M10") (pinfunction "VSS_M10") (pintype "passive"))
      (node (ref "U1") (pin "M12") (pinfunction "VSS_M12") (pintype "passive"))
      (node (ref "U1") (pin "M14") (pinfunction "VSS_M14") (pintype "passive"))
      (node (ref "U1") (pin "M16") (pinfunction "VSS_M16") (pintype "passive"))
      (node (ref "U1") (pin "M18") (pinfunction "VSS_M18") (pintype "passive"))
      (node (ref "U1") (pin "M2") (pinfunction "VSS_M2") (pintype "passive"))
      (node (ref "U1") (pin "M20") (pinfunction "VSS_M20") (pintype "passive"))
      (node (ref "U1") (pin "M22") (pinfunction "VSS_M22") (pintype "passive"))
      (node (ref "U1") (pin "M23") (pinfunction "VSS_M23") (pintype "passive"))
      (node (ref "U1") (pin "M25") (pinfunction "VSS_M25") (pintype "passive"))
      (node (ref "U1") (pin "M27") (pinfunction "VSS_M27") (pintype "passive"))
      (node (ref "U1") (pin "M29") (pinfunction "VSS_M29") (pintype "passive"))
      (node (ref "U1") (pin "M31") (pinfunction "VSS_M31") (pintype "passive"))
      (node (ref "U1") (pin "M33") (pinfunction "VSS_M33") (pintype "passive"))
      (node (ref "U1") (pin "M35") (pinfunction "VSS_M35") (pintype "passive"))
      (node (ref "U1") (pin "M37") (pinfunction "VSS_M37") (pintype "passive"))
      (node (ref "U1") (pin "M39") (pinfunction "VSS_M39") (pintype "passive"))
      (node (ref "U1") (pin "M4") (pinfunction "VSS_M4") (pintype "passive"))
      (node (ref "U1") (pin "M41") (pinfunction "VSS_M41") (pintype "passive"))
      (node (ref "U1") (pin "M43") (pinfunction "VSS_M43") (pintype "passive"))
      (node (ref "U1") (pin "M6") (pinfunction "VSS_M6") (pintype "passive"))
      (node (ref "U1") (pin "M8") (pinfunction "VSS_M8") (pintype "passive"))
      (node (ref "U1") (pin "N1") (pinfunction "VSS_N1") (pintype "passive"))
      (node (ref "U1") (pin "N11") (pinfunction "VSS_N11") (pintype "passive"))
      (node (ref "U1") (pin "N13") (pinfunction "VSS_N13") (pintype "passive"))
      (node (ref "U1") (pin "N15") (pinfunction "VSS_N15") (pintype "passive"))
      (node (ref "U1") (pin "N17") (pinfunction "VSS_N17") (pintype "passive"))
      (node (ref "U1") (pin "N19") (pinfunction "VSS_N19") (pintype "passive"))
      (node (ref "U1") (pin "N21") (pinfunction "VSS_N21") (pintype "passive"))
      (node (ref "U1") (pin "N24") (pinfunction "VSS_N24") (pintype "passive"))
      (node (ref "U1") (pin "N26") (pinfunction "VSS_N26") (pintype "passive"))
      (node (ref "U1") (pin "N28") (pinfunction "VSS_N28") (pintype "passive"))
      (node (ref "U1") (pin "N3") (pinfunction "VSS_N3") (pintype "passive"))
      (node (ref "U1") (pin "N30") (pinfunction "VSS_N30") (pintype "passive"))
      (node (ref "U1") (pin "N32") (pinfunction "VSS_N32") (pintype "passive"))
      (node (ref "U1") (pin "N34") (pinfunction "VSS_N34") (pintype "passive"))
      (node (ref "U1") (pin "N36") (pinfunction "VSS_N36") (pintype "passive"))
      (node (ref "U1") (pin "N38") (pinfunction "VSS_N38") (pintype "passive"))
      (node (ref "U1") (pin "N40") (pinfunction "VSS_N40") (pintype "passive"))
      (node (ref "U1") (pin "N42") (pinfunction "VSS_N42") (pintype "passive"))
      (node (ref "U1") (pin "N44") (pinfunction "VSS_N44") (pintype "passive"))
      (node (ref "U1") (pin "N5") (pinfunction "VSS_N5") (pintype "passive"))
      (node (ref "U1") (pin "N7") (pinfunction "VSS_N7") (pintype "passive"))
      (node (ref "U1") (pin "N9") (pinfunction "VSS_N9") (pintype "passive"))
      (node (ref "U1") (pin "P10") (pinfunction "VSS_P10") (pintype "passive"))
      (node (ref "U1") (pin "P12") (pinfunction "VSS_P12") (pintype "passive"))
      (node (ref "U1") (pin "P14") (pinfunction "VSS_P14") (pintype "passive"))
      (node (ref "U1") (pin "P16") (pinfunction "VSS_P16") (pintype "passive"))
      (node (ref "U1") (pin "P18") (pinfunction "VSS_P18") (pintype "passive"))
      (node (ref "U1") (pin "P2") (pinfunction "VSS_P2") (pintype "passive"))
      (node (ref "U1") (pin "P20") (pinfunction "VSS_P20") (pintype "passive"))
      (node (ref "U1") (pin "P22") (pinfunction "VSS_P22") (pintype "passive"))
      (node (ref "U1") (pin "P23") (pinfunction "VSS_P23") (pintype "passive"))
      (node (ref "U1") (pin "P25") (pinfunction "VSS_P25") (pintype "passive"))
      (node (ref "U1") (pin "P27") (pinfunction "VSS_P27") (pintype "passive"))
      (node (ref "U1") (pin "P29") (pinfunction "VSS_P29") (pintype "passive"))
      (node (ref "U1") (pin "P31") (pinfunction "VSS_P31") (pintype "passive"))
      (node (ref "U1") (pin "P33") (pinfunction "VSS_P33") (pintype "passive"))
      (node (ref "U1") (pin "P35") (pinfunction "VSS_P35") (pintype "passive"))
      (node (ref "U1") (pin "P37") (pinfunction "VSS_P37") (pintype "passive"))
      (node (ref "U1") (pin "P39") (pinfunction "VSS_P39") (pintype "passive"))
      (node (ref "U1") (pin "P4") (pinfunction "VSS_P4") (pintype "passive"))
      (node (ref "U1") (pin "P41") (pinfunction "VSS_P41") (pintype "passive"))
      (node (ref "U1") (pin "P43") (pinfunction "VSS_P43") (pintype "passive"))
      (node (ref "U1") (pin "P6") (pinfunction "VSS_P6") (pintype "passive"))
      (node (ref "U1") (pin "P8") (pinfunction "VSS_P8") (pintype "passive"))
      (node (ref "U1") (pin "R1") (pinfunction "VSS_R1") (pintype "passive"))
      (node (ref "U1") (pin "R11") (pinfunction "VSS_R11") (pintype "passive"))
      (node (ref "U1") (pin "R13") (pinfunction "VSS_R13") (pintype "passive"))
      (node (ref "U1") (pin "R15") (pinfunction "VSS_R15") (pintype "passive"))
      (node (ref "U1") (pin "R17") (pinfunction "VSS_R17") (pintype "passive"))
      (node (ref "U1") (pin "R19") (pinfunction "VSS_R19") (pintype "passive"))
      (node (ref "U1") (pin "R21") (pinfunction "VSS_R21") (pintype "passive"))
      (node (ref "U1") (pin "R24") (pinfunction "VSS_R24") (pintype "passive"))
      (node (ref "U1") (pin "R26") (pinfunction "VSS_R26") (pintype "passive"))
      (node (ref "U1") (pin "R28") (pinfunction "VSS_R28") (pintype "passive"))
      (node (ref "U1") (pin "R3") (pinfunction "VSS_R3") (pintype "passive"))
      (node (ref "U1") (pin "R30") (pinfunction "VSS_R30") (pintype "passive"))
      (node (ref "U1") (pin "R32") (pinfunction "VSS_R32") (pintype "passive"))
      (node (ref "U1") (pin "R34") (pinfunction "VSS_R34") (pintype "passive"))
      (node (ref "U1") (pin "R36") (pinfunction "VSS_R36") (pintype "passive"))
      (node (ref "U1") (pin "R38") (pinfunction "VSS_R38") (pintype "passive"))
      (node (ref "U1") (pin "R40") (pinfunction "VSS_R40") (pintype "passive"))
      (node (ref "U1") (pin "R42") (pinfunction "VSS_R42") (pintype "passive"))
      (node (ref "U1") (pin "R44") (pinfunction "VSS_R44") (pintype "passive"))
      (node (ref "U1") (pin "R5") (pinfunction "VSS_R5") (pintype "passive"))
      (node (ref "U1") (pin "R7") (pinfunction "VSS_R7") (pintype "passive"))
      (node (ref "U1") (pin "R9") (pinfunction "VSS_R9") (pintype "passive"))
      (node (ref "U1") (pin "T10") (pinfunction "VSS_T10") (pintype "passive"))
      (node (ref "U1") (pin "T12") (pinfunction "VSS_T12") (pintype "passive"))
      (node (ref "U1") (pin "T14") (pinfunction "VSS_T14") (pintype "passive"))
      (node (ref "U1") (pin "T16") (pinfunction "VSS_T16") (pintype "passive"))
      (node (ref "U1") (pin "T18") (pinfunction "VSS_T18") (pintype "passive"))
      (node (ref "U1") (pin "T2") (pinfunction "VSS_T2") (pintype "passive"))
      (node (ref "U1") (pin "T20") (pinfunction "VSS_T20") (pintype "passive"))
      (node (ref "U1") (pin "T22") (pinfunction "VSS_T22") (pintype "passive"))
      (node (ref "U1") (pin "T23") (pinfunction "VSS_T23") (pintype "passive"))
      (node (ref "U1") (pin "T25") (pinfunction "VSS_T25") (pintype "passive"))
      (node (ref "U1") (pin "T27") (pinfunction "VSS_T27") (pintype "passive"))
      (node (ref "U1") (pin "T29") (pinfunction "VSS_T29") (pintype "passive"))
      (node (ref "U1") (pin "T31") (pinfunction "VSS_T31") (pintype "passive"))
      (node (ref "U1") (pin "T33") (pinfunction "VSS_T33") (pintype "passive"))
      (node (ref "U1") (pin "T35") (pinfunction "VSS_T35") (pintype "passive"))
      (node (ref "U1") (pin "T37") (pinfunction "VSS_T37") (pintype "passive"))
      (node (ref "U1") (pin "T39") (pinfunction "VSS_T39") (pintype "passive"))
      (node (ref "U1") (pin "T4") (pinfunction "VSS_T4") (pintype "passive"))
      (node (ref "U1") (pin "T41") (pinfunction "VSS_T41") (pintype "passive"))
      (node (ref "U1") (pin "T43") (pinfunction "VSS_T43") (pintype "passive"))
      (node (ref "U1") (pin "T6") (pinfunction "VSS_T6") (pintype "passive"))
      (node (ref "U1") (pin "T8") (pinfunction "VSS_T8") (pintype "passive"))
      (node (ref "U1") (pin "U1") (pinfunction "VSS_U1") (pintype "passive"))
      (node (ref "U1") (pin "U11") (pinfunction "VSS_U11") (pintype "passive"))
      (node (ref "U1") (pin "U13") (pinfunction "VSS_U13") (pintype "passive"))
      (node (ref "U1") (pin "U15") (pinfunction "VSS_U15") (pintype "passive"))
      (node (ref "U1") (pin "U17") (pinfunction "VSS_U17") (pintype "passive"))
      (node (ref "U1") (pin "U19") (pinfunction "VSS_U19") (pintype "passive"))
      (node (ref "U1") (pin "U21") (pinfunction "VSS_U21") (pintype "passive"))
      (node (ref "U1") (pin "U24") (pinfunction "VSS_U24") (pintype "passive"))
      (node (ref "U1") (pin "U26") (pinfunction "VSS_U26") (pintype "passive"))
      (node (ref "U1") (pin "U28") (pinfunction "VSS_U28") (pintype "passive"))
      (node (ref "U1") (pin "U3") (pinfunction "VSS_U3") (pintype "passive"))
      (node (ref "U1") (pin "U30") (pinfunction "VSS_U30") (pintype "passive"))
      (node (ref "U1") (pin "U32") (pinfunction "VSS_U32") (pintype "passive"))
      (node (ref "U1") (pin "U34") (pinfunction "VSS_U34") (pintype "passive"))
      (node (ref "U1") (pin "U36") (pinfunction "VSS_U36") (pintype "passive"))
      (node (ref "U1") (pin "U38") (pinfunction "VSS_U38") (pintype "passive"))
      (node (ref "U1") (pin "U40") (pinfunction "VSS_U40") (pintype "passive"))
      (node (ref "U1") (pin "U42") (pinfunction "VSS_U42") (pintype "passive"))
      (node (ref "U1") (pin "U44") (pinfunction "VSS_U44") (pintype "passive"))
      (node (ref "U1") (pin "U5") (pinfunction "VSS_U5") (pintype "passive"))
      (node (ref "U1") (pin "U7") (pinfunction "VSS_U7") (pintype "passive"))
      (node (ref "U1") (pin "U9") (pinfunction "VSS_U9") (pintype "passive"))
      (node (ref "U1") (pin "V10") (pinfunction "VSS_V10") (pintype "passive"))
      (node (ref "U1") (pin "V12") (pinfunction "VSS_V12") (pintype "passive"))
      (node (ref "U1") (pin "V14") (pinfunction "VSS_V14") (pintype "passive"))
      (node (ref "U1") (pin "V16") (pinfunction "VSS_V16") (pintype "passive"))
      (node (ref "U1") (pin "V18") (pinfunction "VSS_V18") (pintype "passive"))
      (node (ref "U1") (pin "V2") (pinfunction "VSS_V2") (pintype "passive"))
      (node (ref "U1") (pin "V20") (pinfunction "VSS_V20") (pintype "passive"))
      (node (ref "U1") (pin "V22") (pinfunction "VSS_V22") (pintype "passive"))
      (node (ref "U1") (pin "V23") (pinfunction "VSS_V23") (pintype "passive"))
      (node (ref "U1") (pin "V25") (pinfunction "VSS_V25") (pintype "passive"))
      (node (ref "U1") (pin "V27") (pinfunction "VSS_V27") (pintype "passive"))
      (node (ref "U1") (pin "V29") (pinfunction "VSS_V29") (pintype "passive"))
      (node (ref "U1") (pin "V31") (pinfunction "VSS_V31") (pintype "passive"))
      (node (ref "U1") (pin "V33") (pinfunction "VSS_V33") (pintype "passive"))
      (node (ref "U1") (pin "V35") (pinfunction "VSS_V35") (pintype "passive"))
      (node (ref "U1") (pin "V37") (pinfunction "VSS_V37") (pintype "passive"))
      (node (ref "U1") (pin "V39") (pinfunction "VSS_V39") (pintype "passive"))
      (node (ref "U1") (pin "V4") (pinfunction "VSS_V4") (pintype "passive"))
      (node (ref "U1") (pin "V41") (pinfunction "VSS_V41") (pintype "passive"))
      (node (ref "U1") (pin "V43") (pinfunction "VSS_V43") (pintype "passive"))
      (node (ref "U1") (pin "V6") (pinfunction "VSS_V6") (pintype "passive"))
      (node (ref "U1") (pin "V8") (pinfunction "VSS_V8") (pintype "passive"))
      (node (ref "U1") (pin "W1") (pinfunction "VSS_W1") (pintype "passive"))
      (node (ref "U1") (pin "W11") (pinfunction "VSS_W11") (pintype "passive"))
      (node (ref "U1") (pin "W13") (pinfunction "VSS_W13") (pintype "passive"))
      (node (ref "U1") (pin "W15") (pinfunction "VSS_W15") (pintype "passive"))
      (node (ref "U1") (pin "W17") (pinfunction "VSS_W17") (pintype "passive"))
      (node (ref "U1") (pin "W19") (pinfunction "VSS_W19") (pintype "passive"))
      (node (ref "U1") (pin "W21") (pinfunction "VSS_W21") (pintype "passive"))
      (node (ref "U1") (pin "W24") (pinfunction "VSS_W24") (pintype "passive"))
      (node (ref "U1") (pin "W26") (pinfunction "VSS_W26") (pintype "passive"))
      (node (ref "U1") (pin "W28") (pinfunction "VSS_W28") (pintype "passive"))
      (node (ref "U1") (pin "W3") (pinfunction "VSS_W3") (pintype "passive"))
      (node (ref "U1") (pin "W30") (pinfunction "VSS_W30") (pintype "passive"))
      (node (ref "U1") (pin "W32") (pinfunction "VSS_W32") (pintype "passive"))
      (node (ref "U1") (pin "W34") (pinfunction "VSS_W34") (pintype "passive"))
      (node (ref "U1") (pin "W36") (pinfunction "VSS_W36") (pintype "passive"))
      (node (ref "U1") (pin "W38") (pinfunction "VSS_W38") (pintype "passive"))
      (node (ref "U1") (pin "W40") (pinfunction "VSS_W40") (pintype "passive"))
      (node (ref "U1") (pin "W42") (pinfunction "VSS_W42") (pintype "passive"))
      (node (ref "U1") (pin "W44") (pinfunction "VSS_W44") (pintype "passive"))
      (node (ref "U1") (pin "W5") (pinfunction "VSS_W5") (pintype "passive"))
      (node (ref "U1") (pin "W7") (pinfunction "VSS_W7") (pintype "passive"))
      (node (ref "U1") (pin "W9") (pinfunction "VSS_W9") (pintype "passive"))
      (node (ref "U1") (pin "Y10") (pinfunction "VSS_Y10") (pintype "passive"))
      (node (ref "U1") (pin "Y12") (pinfunction "VSS_Y12") (pintype "passive"))
      (node (ref "U1") (pin "Y14") (pinfunction "VSS_Y14") (pintype "passive"))
      (node (ref "U1") (pin "Y16") (pinfunction "VSS_Y16") (pintype "passive"))
      (node (ref "U1") (pin "Y18") (pinfunction "VSS_Y18") (pintype "passive"))
      (node (ref "U1") (pin "Y2") (pinfunction "VSS_Y2") (pintype "passive"))
      (node (ref "U1") (pin "Y20") (pinfunction "VSS_Y20") (pintype "passive"))
      (node (ref "U1") (pin "Y22") (pinfunction "VSS_Y22") (pintype "passive"))
      (node (ref "U1") (pin "Y23") (pinfunction "VSS_Y23") (pintype "passive"))
      (node (ref "U1") (pin "Y25") (pinfunction "VSS_Y25") (pintype "passive"))
      (node (ref "U1") (pin "Y27") (pinfunction "VSS_Y27") (pintype "passive"))
      (node (ref "U1") (pin "Y29") (pinfunction "VSS_Y29") (pintype "passive"))
      (node (ref "U1") (pin "Y31") (pinfunction "VSS_Y31") (pintype "passive"))
      (node (ref "U1") (pin "Y33") (pinfunction "VSS_Y33") (pintype "passive"))
      (node (ref "U1") (pin "Y35") (pinfunction "VSS_Y35") (pintype "passive"))
      (node (ref "U1") (pin "Y37") (pinfunction "VSS_Y37") (pintype "passive"))
      (node (ref "U1") (pin "Y39") (pinfunction "VSS_Y39") (pintype "passive"))
      (node (ref "U1") (pin "Y4") (pinfunction "VSS_Y4") (pintype "passive"))
      (node (ref "U1") (pin "Y41") (pinfunction "VSS_Y41") (pintype "passive"))
      (node (ref "U1") (pin "Y43") (pinfunction "VSS_Y43") (pintype "passive"))
      (node (ref "U1") (pin "Y6") (pinfunction "VSS_Y6") (pintype "passive"))
      (node (ref "U1") (pin "Y8") (pinfunction "VSS_Y8") (pintype "passive"))
    )
    (net (code "3") (name "Net-(U1A-VDD_D2-PadE27)") (class "Default")
      (node (ref "U1") (pin "AY27") (pinfunction "VDD_D3_AY27") (pintype "passive"))
      (node (ref "U1") (pin "E27") (pinfunction "VDD_D2_E27") (pintype "passive"))
    )
    (net (code "4") (name "Net-(U1A-VSS-PadAF24)") (class "Default")
      (node (ref "U1") (pin "AF24") (pinfunction "VSS_AF24") (pintype "passive"))
      (node (ref "U1") (pin "AY17") (pinfunction "VSS_AY17") (pintype "passive"))
    )
    (net (code "5") (name "Net-(U1A-VSS-PadAG37)") (class "Default")
      (node (ref "U1") (pin "AG37") (pinfunction "VSS_AG37") (pintype "passive"))
      (node (ref "U1") (pin "AV7") (pinfunction "VSS_AV7") (pintype "passive"))
    )
    (net (code "6") (name "Net-(U1A-VSS-PadAG39)") (class "Default")
      (node (ref "U1") (pin "AG39") (pinfunction "VSS_AG39") (pintype "passive"))
      (node (ref "U1") (pin "AV9") (pinfunction "VSS_AV9") (pintype "passive"))
    )
    (net (code "7") (name "Net-(U1A-VSS-PadAH44)") (class "Default")
      (node (ref "U1") (pin "AH44") (pinfunction "VSS_AH44") (pintype "passive"))
      (node (ref "U1") (pin "AU14") (pinfunction "VSS_AU14") (pintype "passive"))
    )
  )
)
